# lisa_l.net
KiCad netlist of a schematic drawn in EAGLE
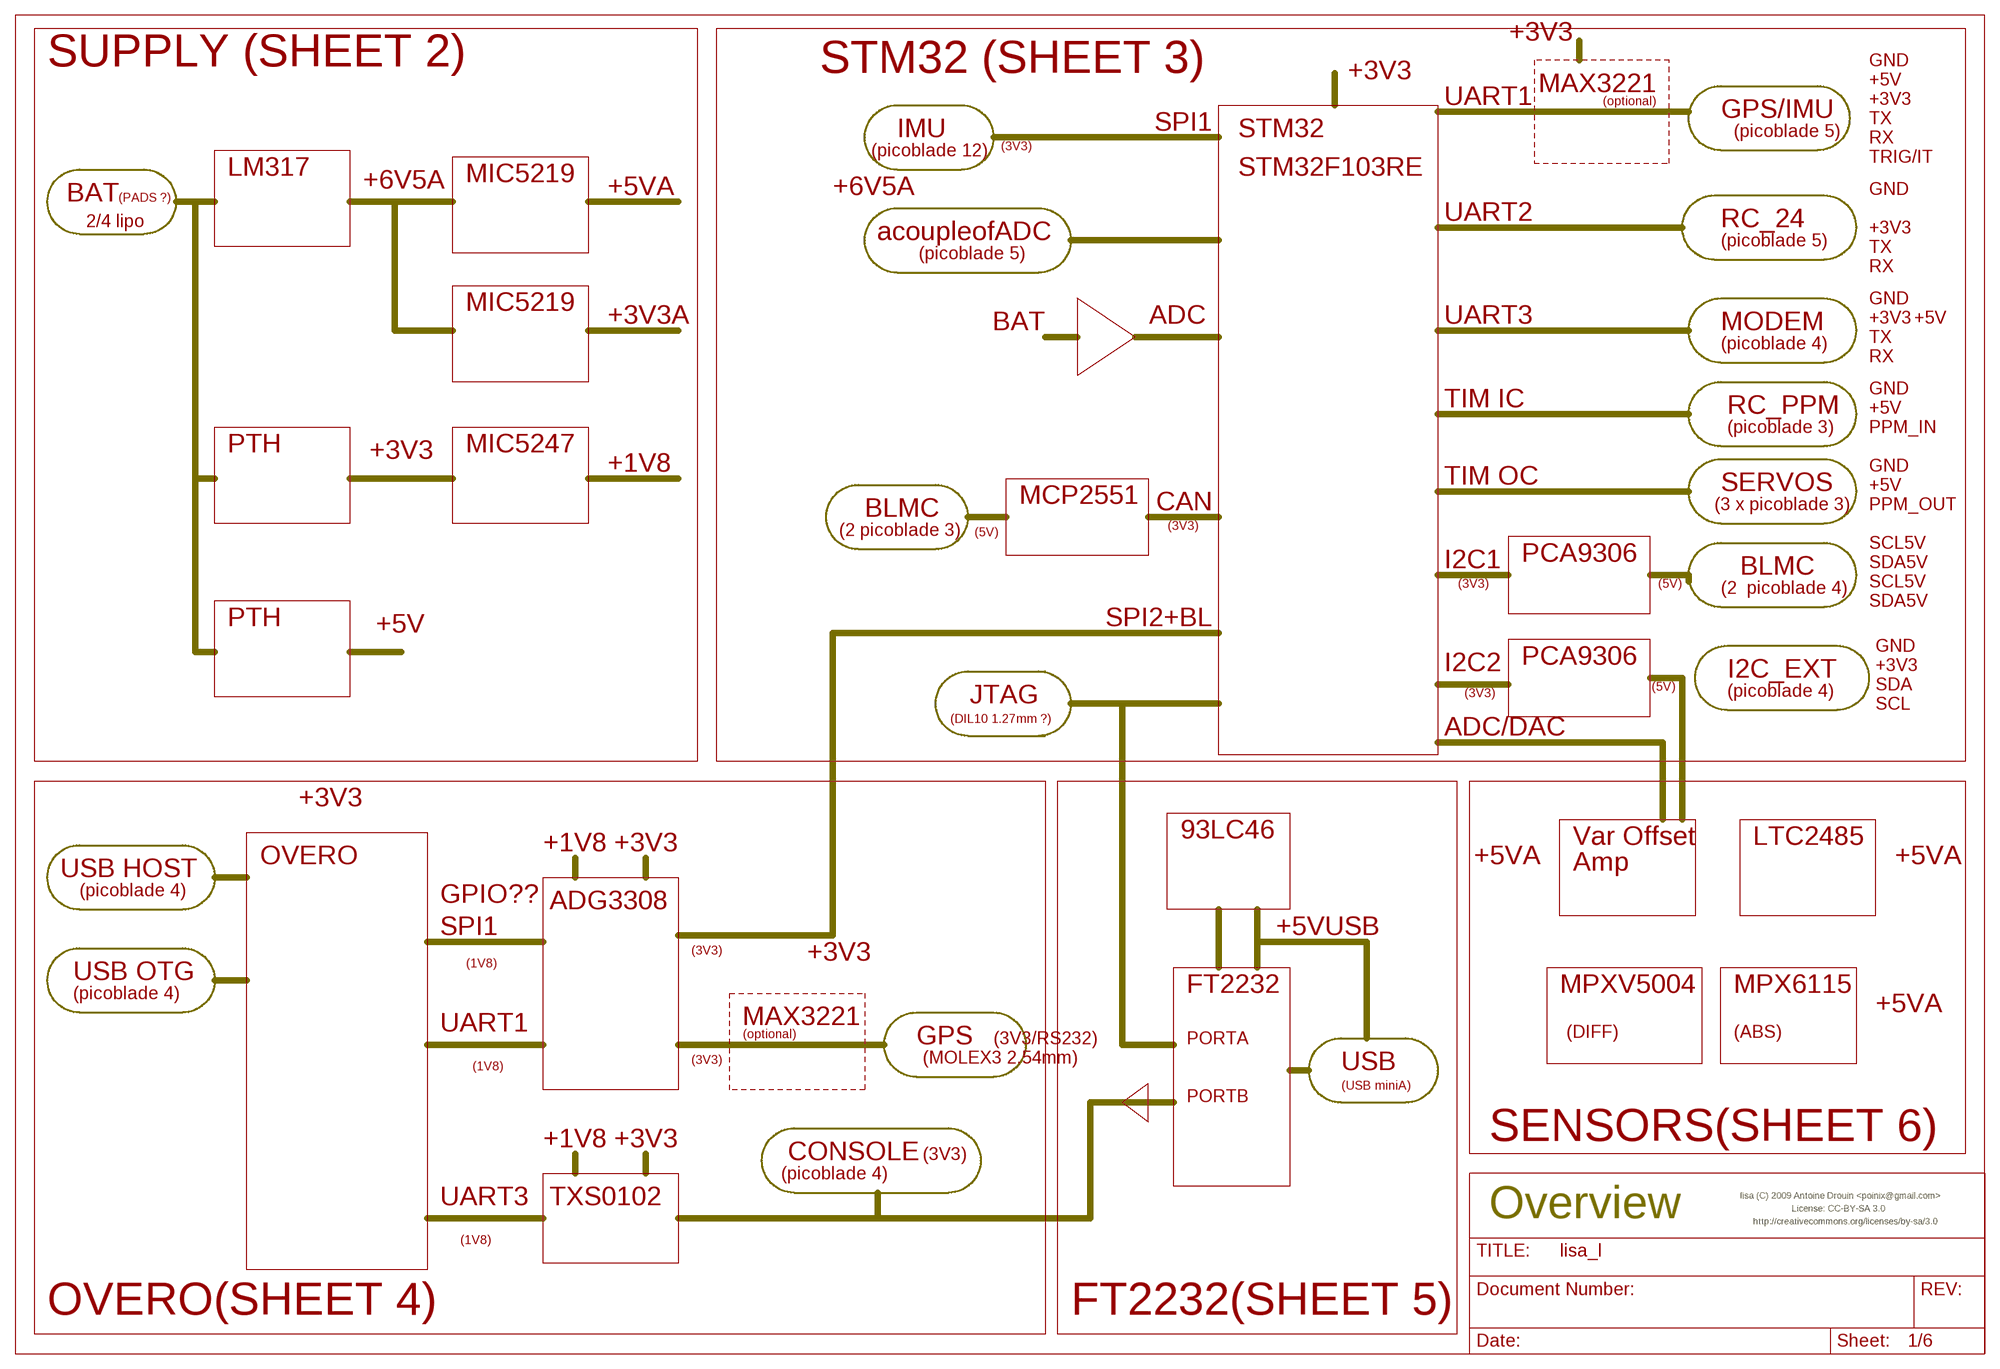
[diagram p0: schematic, sheet 1]
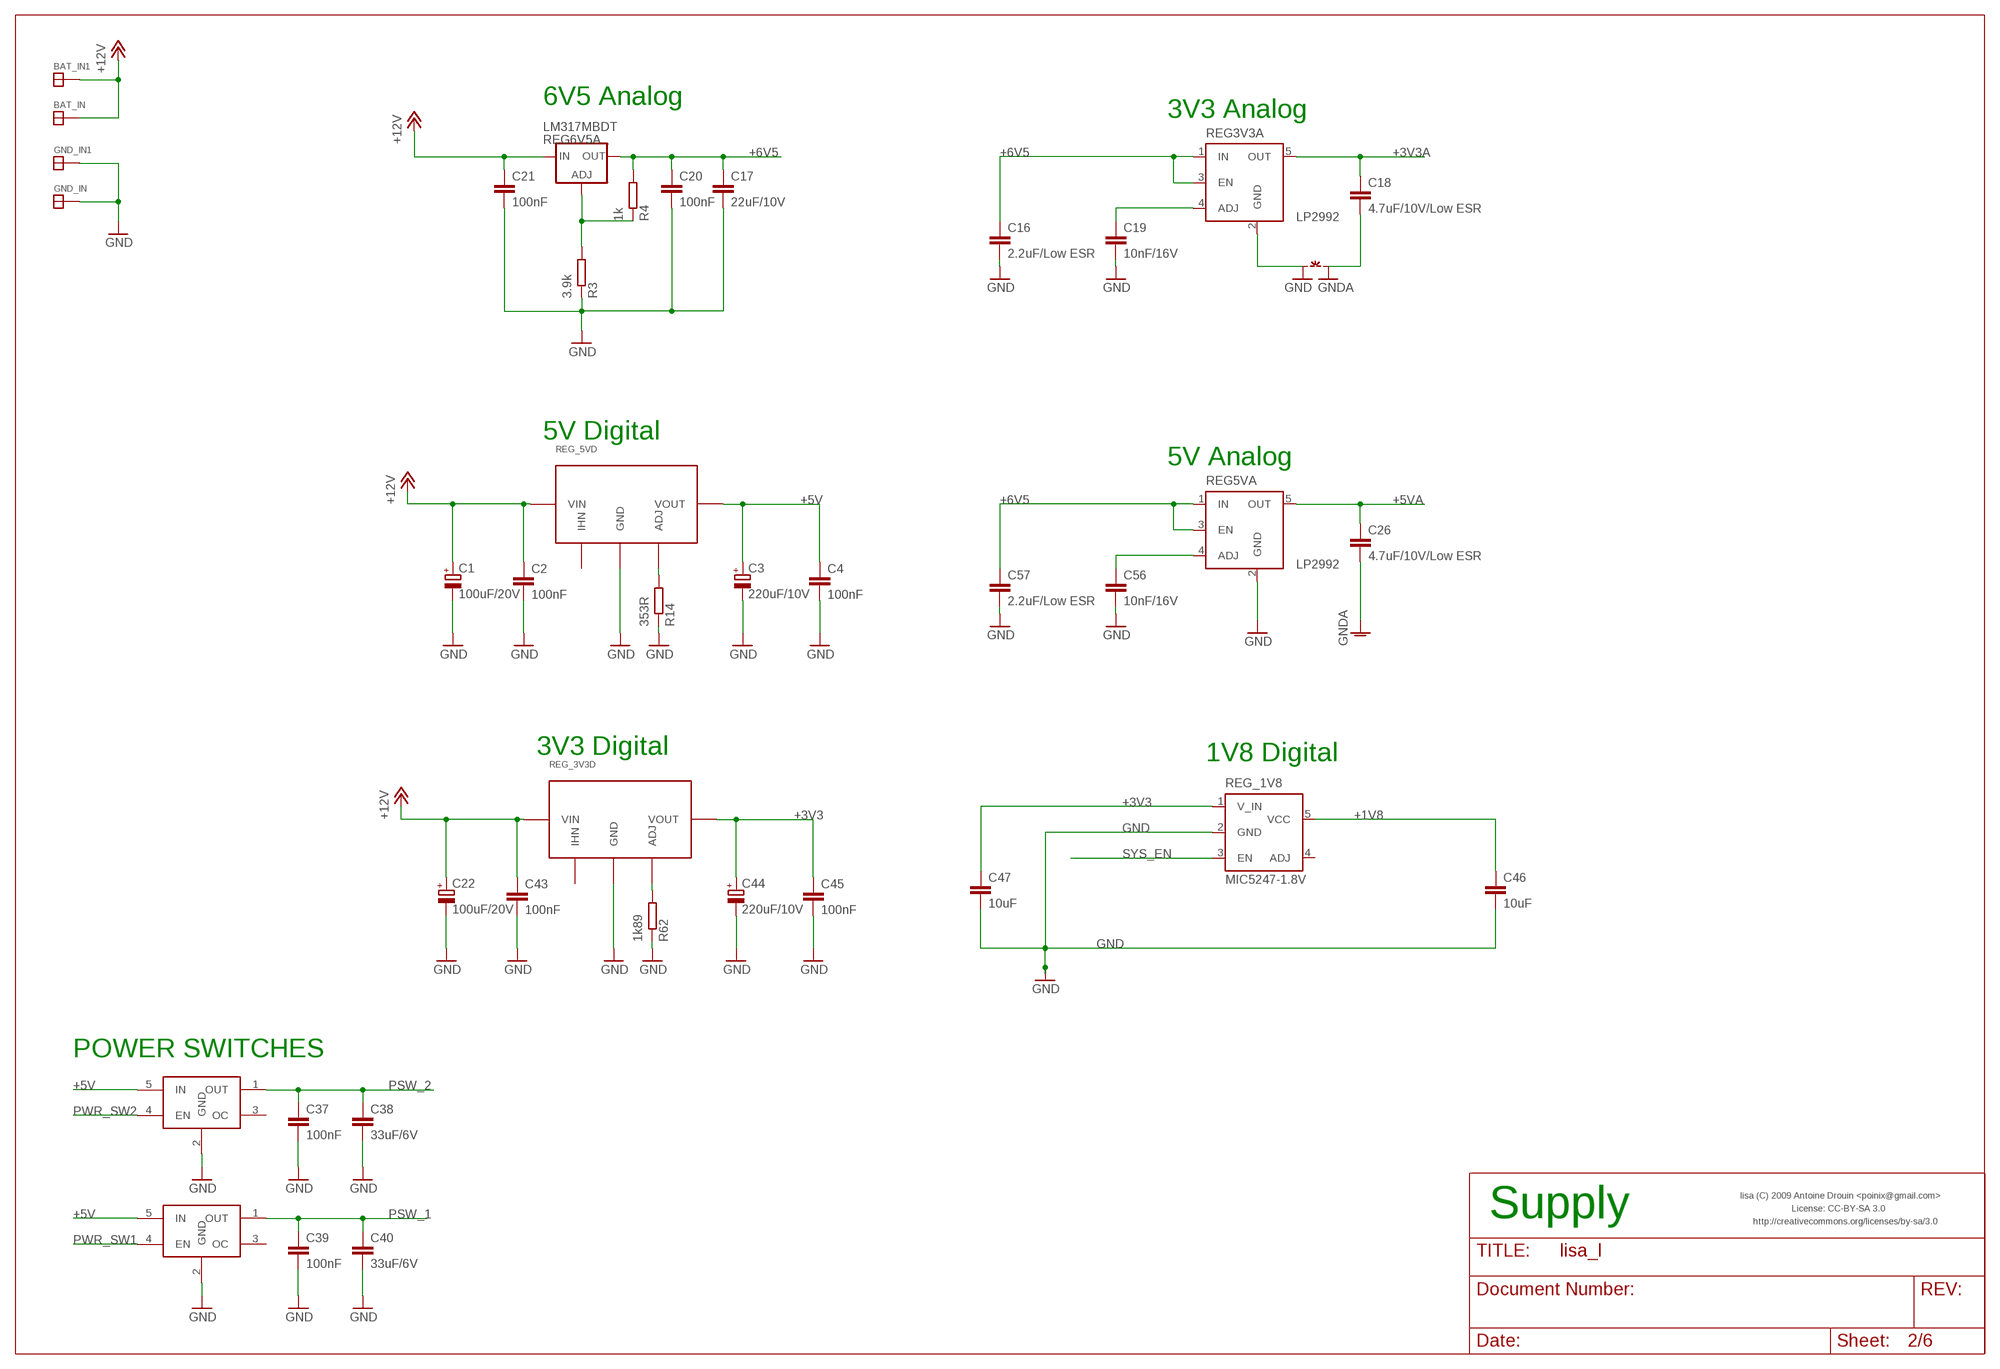
[diagram p1: schematic, sheet 2]
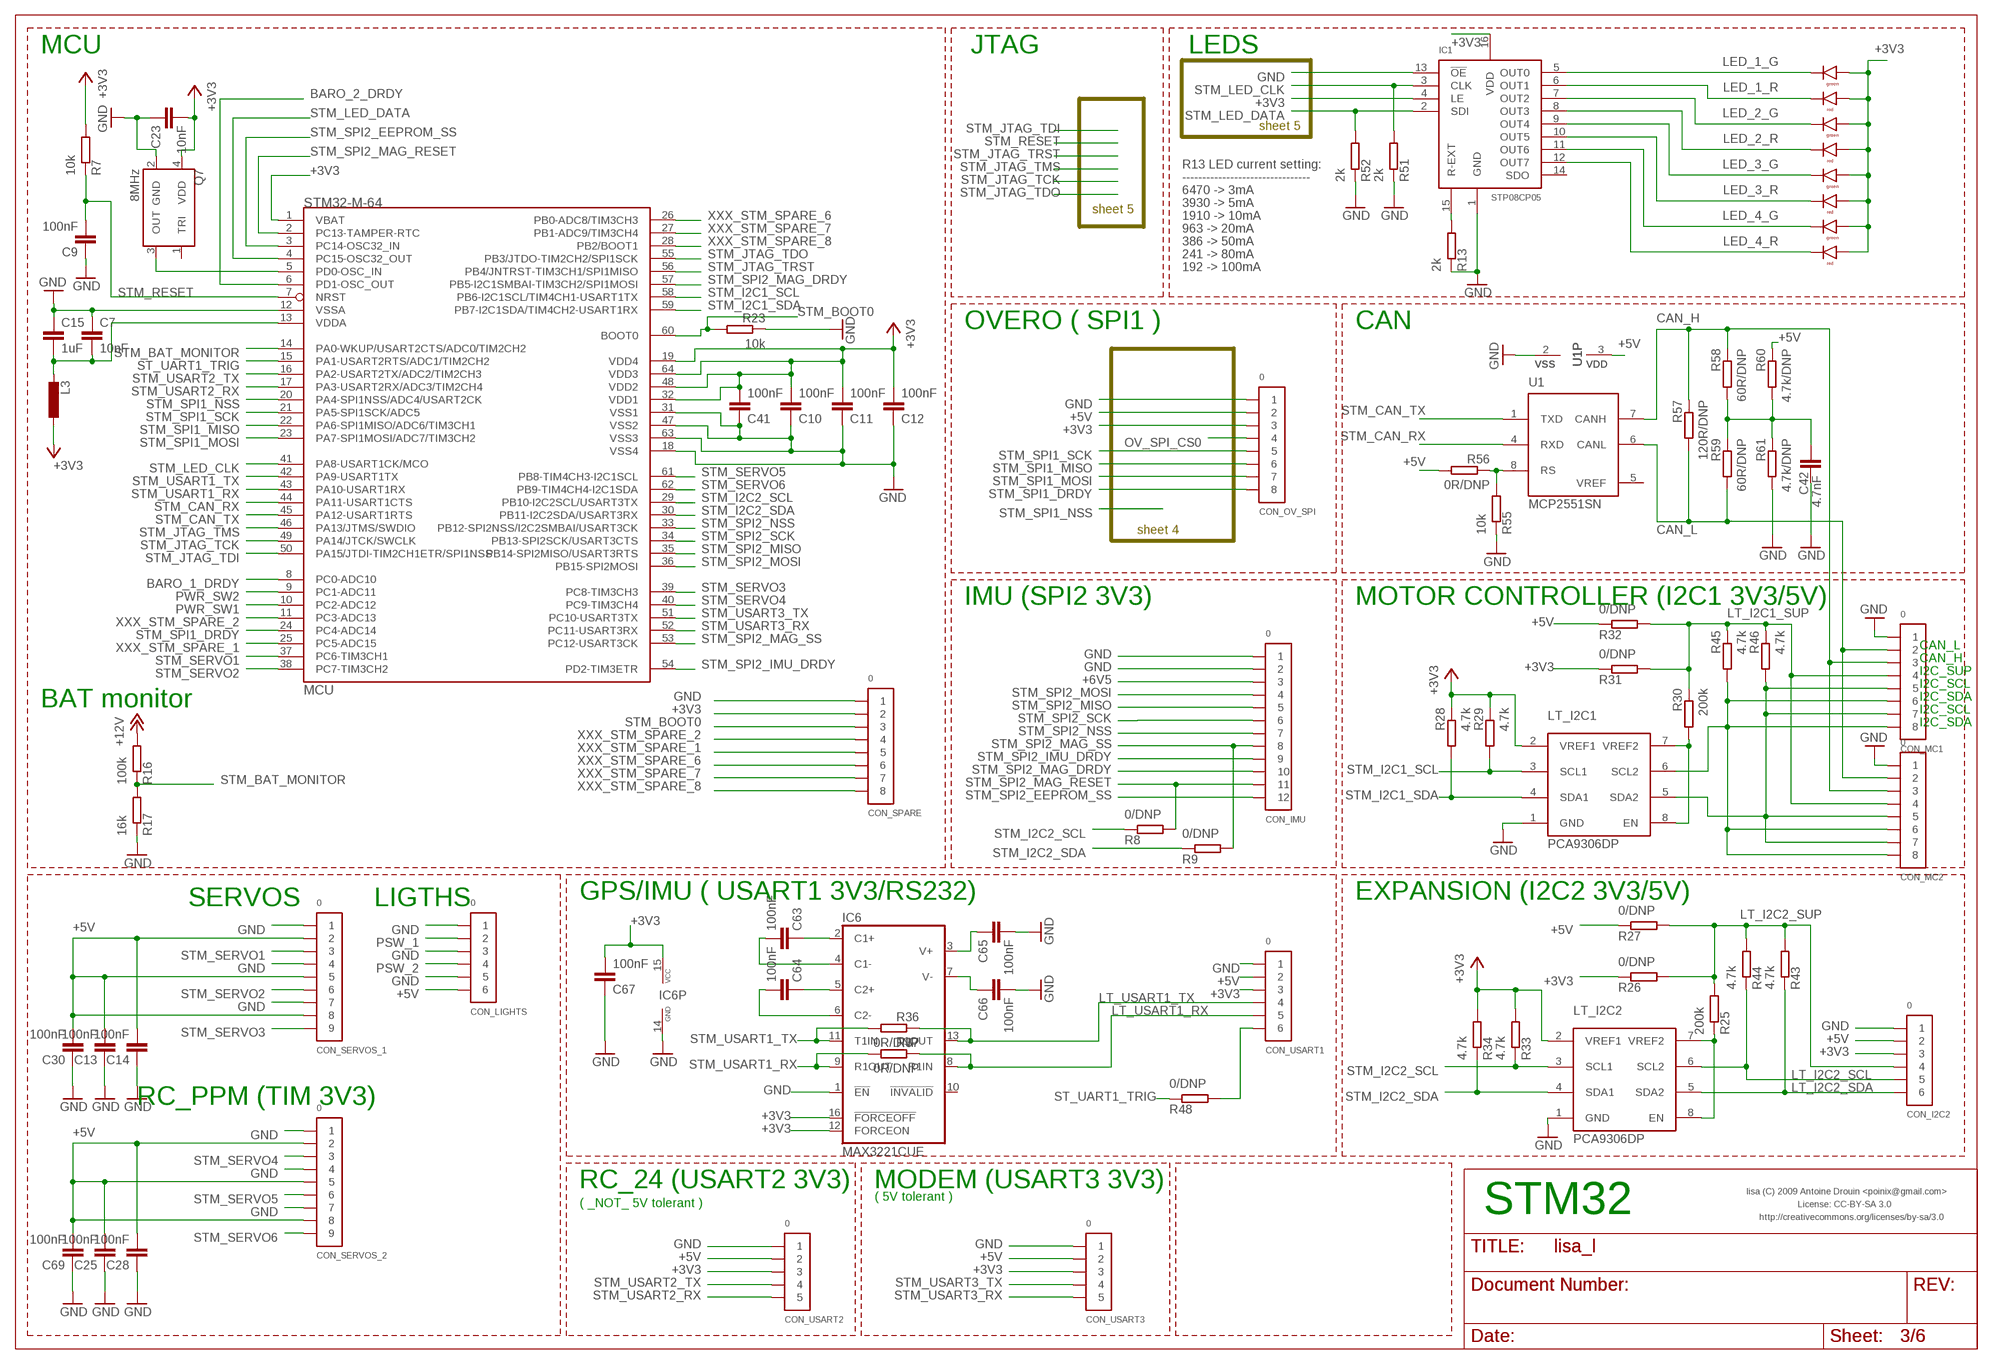
[diagram p2: schematic, sheet 3]
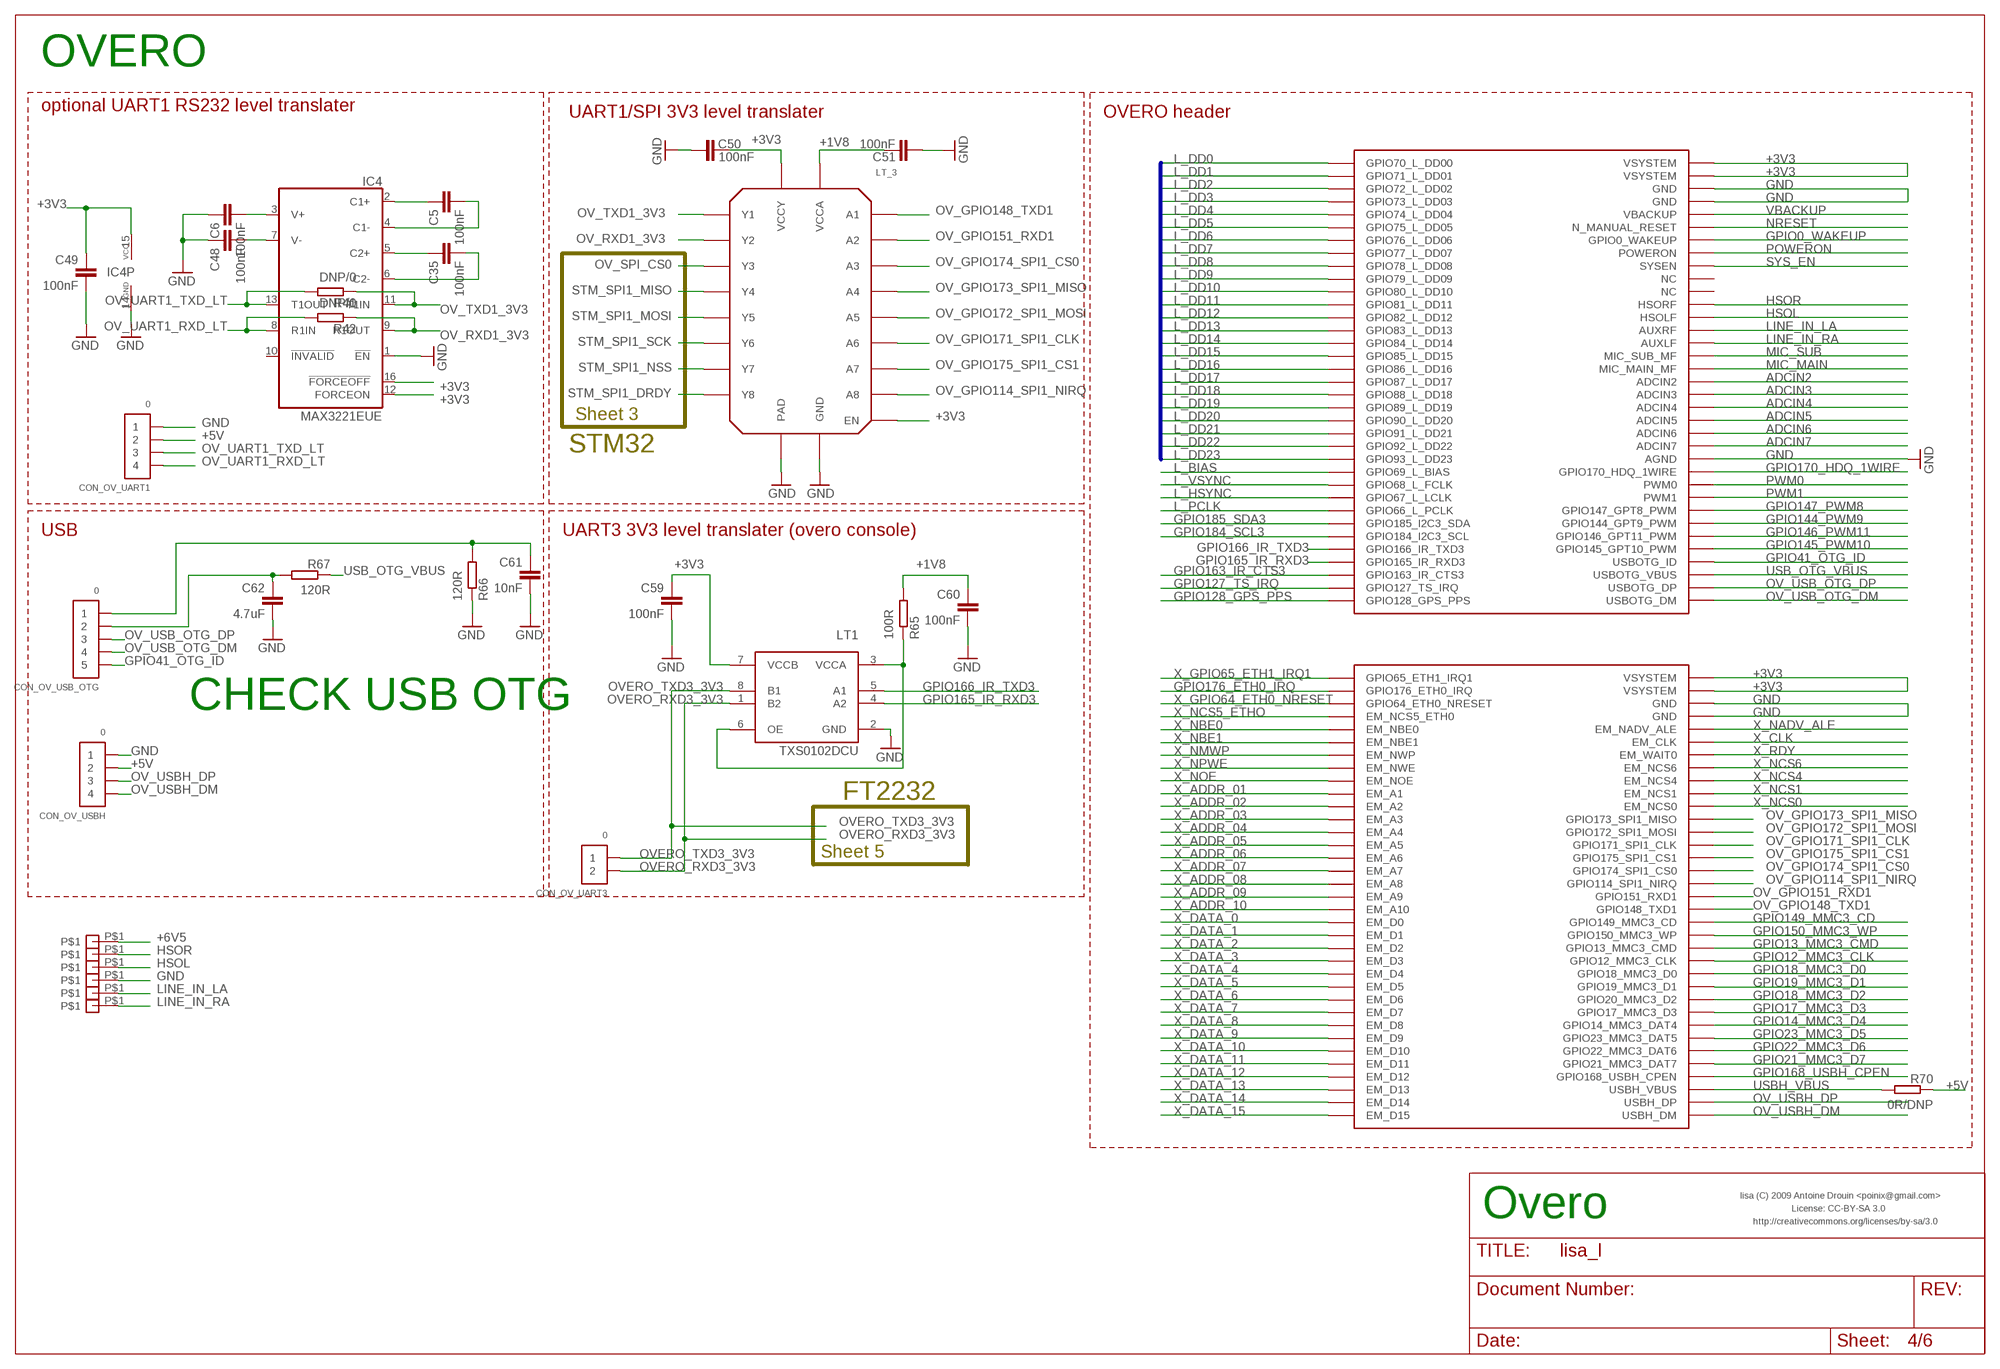
[diagram p3: schematic, sheet 4]
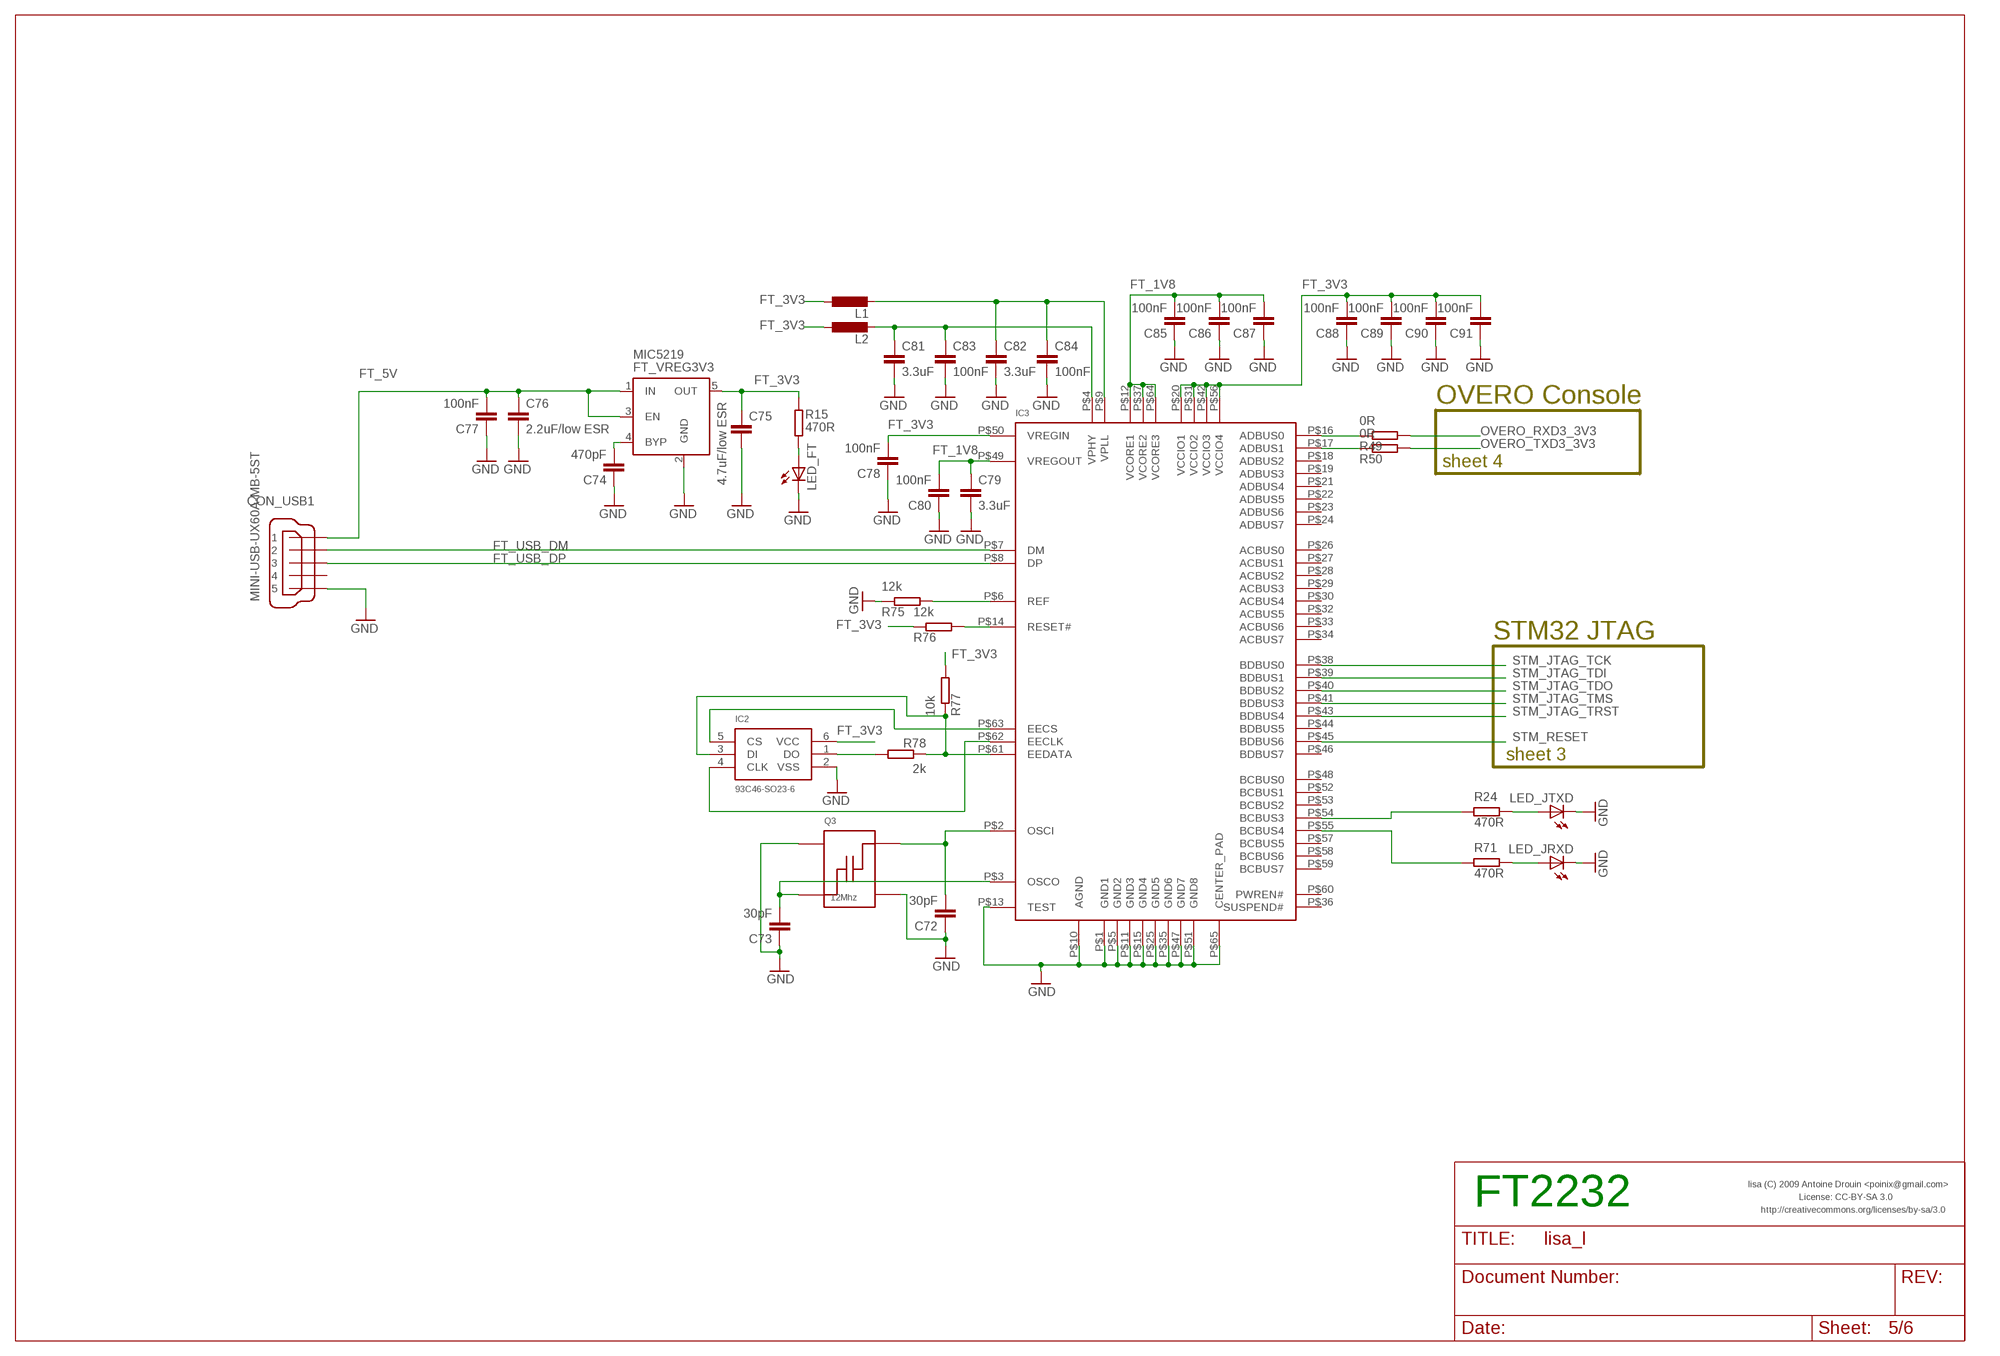
[diagram p4: schematic, sheet 5]
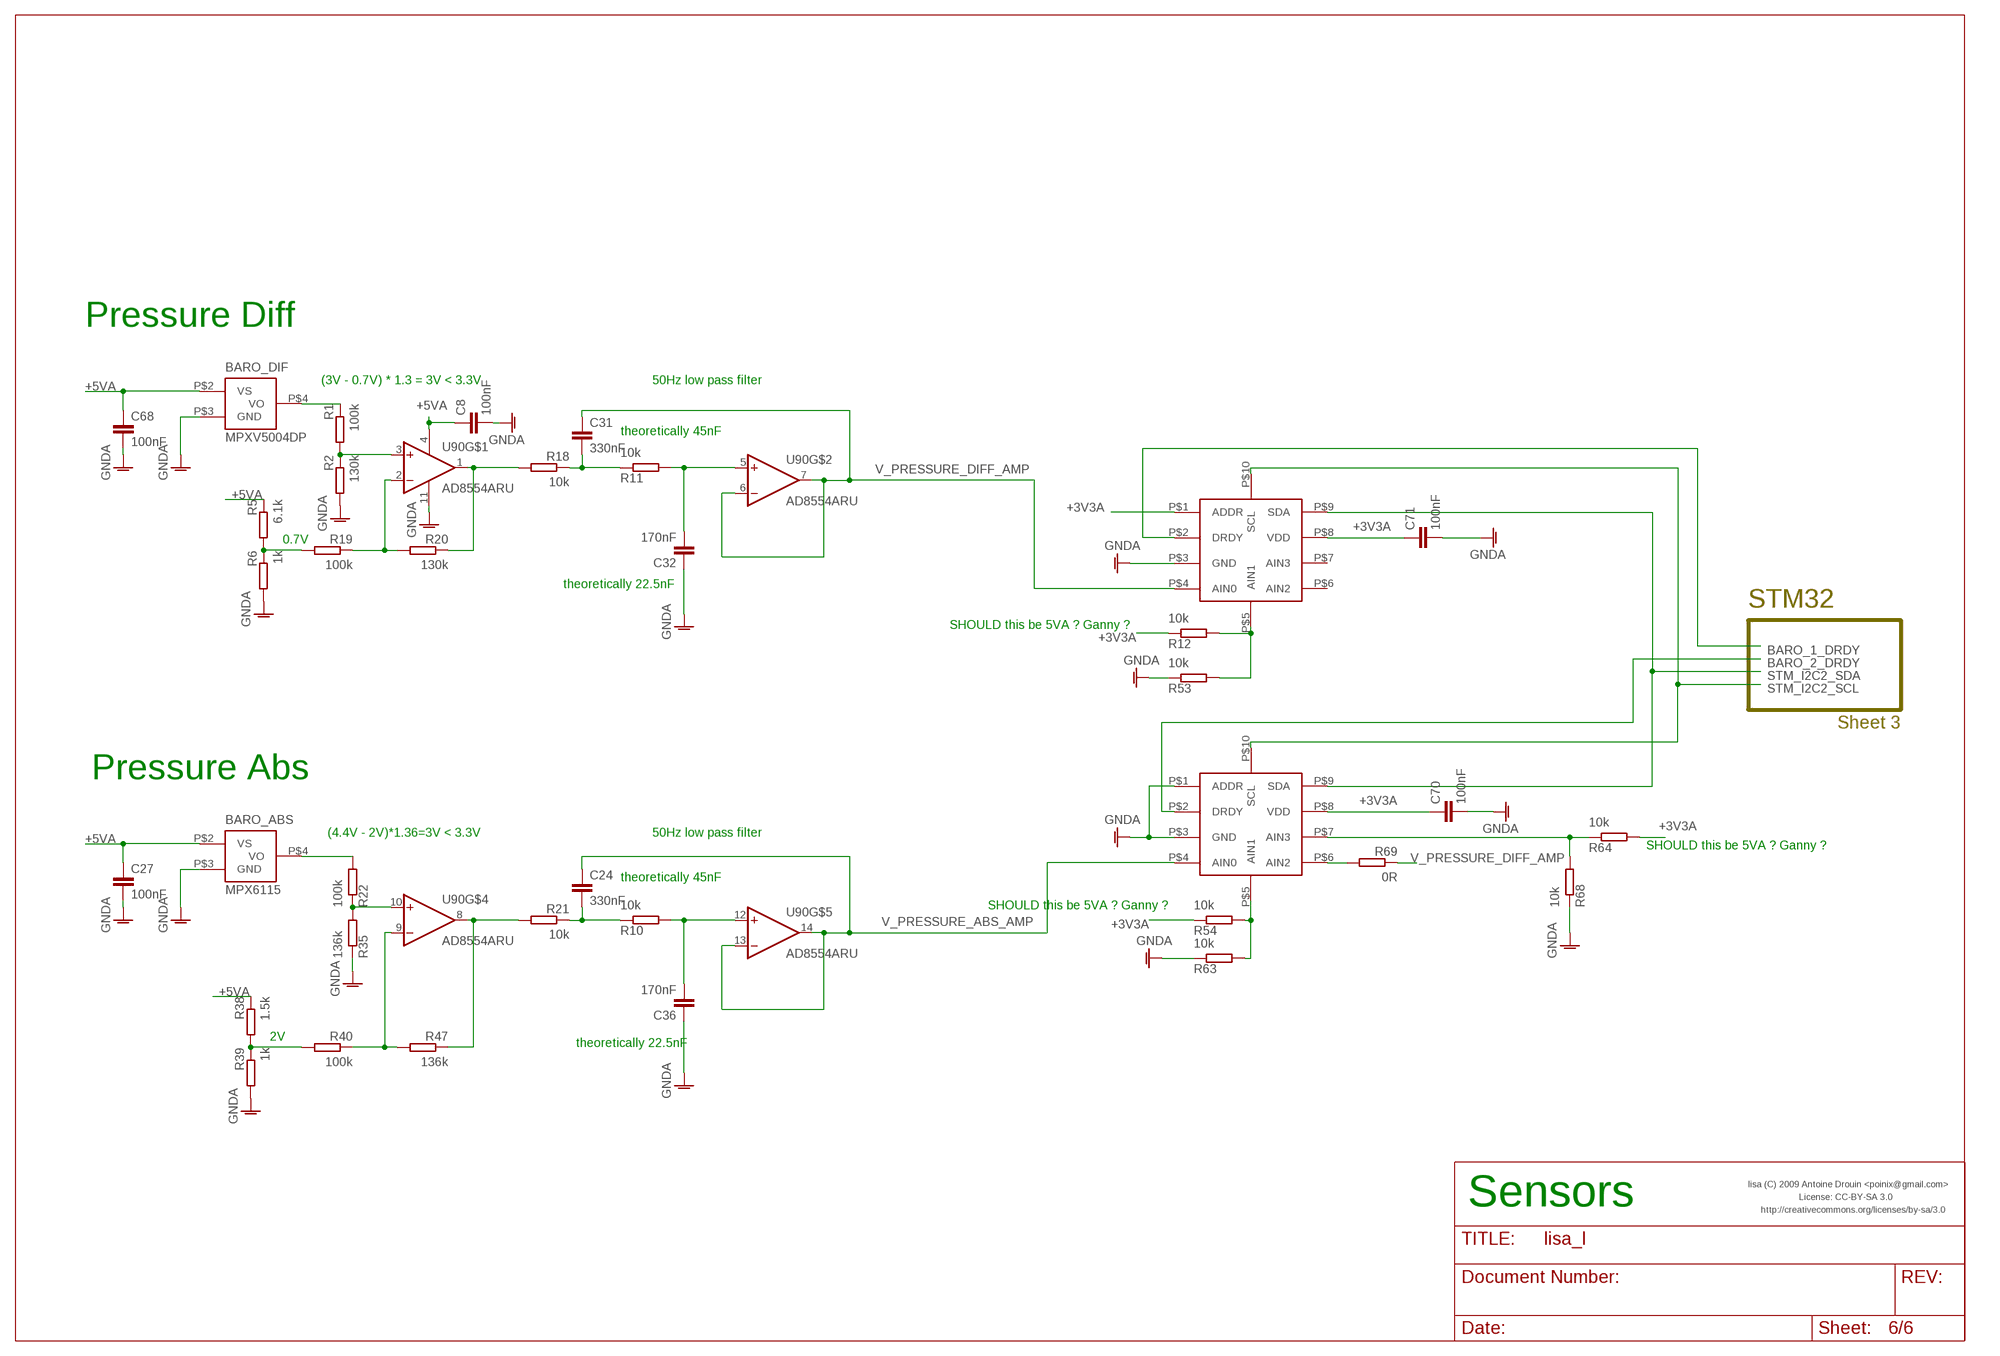
[diagram p5: schematic, sheet 6]

(export (version "E")
  (design (tool "Eeschema 10.0.6"))
  (components
    (comp (ref "C72")
      (value "30pF")
      (footprint "eagle-import:0603-CAP")
      (libsource (lib "eagle-import") (part "res_cap_CAPACITOR-0603"))
    )
    (comp (ref "C73")
      (value "30pF")
      (footprint "eagle-import:0603-CAP")
      (libsource (lib "eagle-import") (part "res_cap_CAPACITOR-0603"))
    )
    (comp (ref "C74")
      (value "470pF")
      (footprint "eagle-import:0603-CAP")
      (libsource (lib "eagle-import") (part "res_cap_CAPACITOR-0603"))
    )
    (comp (ref "C75")
      (value "4.7uF/low ESR")
      (footprint "eagle-import:0603-CAP")
      (libsource (lib "eagle-import") (part "res_cap_CAPACITOR-0603"))
    )
    (comp (ref "C76")
      (value "2.2uF/low ESR")
      (footprint "eagle-import:0603-CAP")
      (libsource (lib "eagle-import") (part "res_cap_CAPACITOR-0603"))
    )
    (comp (ref "C77")
      (value "100nF")
      (footprint "eagle-import:0603-CAP")
      (libsource (lib "eagle-import") (part "res_cap_CAPACITOR-0603"))
    )
    (comp (ref "C78")
      (value "100nF")
      (footprint "eagle-import:0603-CAP")
      (libsource (lib "eagle-import") (part "res_cap_CAPACITOR-0603"))
    )
    (comp (ref "C79")
      (value "3.3uF")
      (footprint "eagle-import:0603-CAP")
      (libsource (lib "eagle-import") (part "res_cap_CAPACITOR-0603"))
    )
    (comp (ref "C80")
      (value "100nF")
      (footprint "eagle-import:0603-CAP")
      (libsource (lib "eagle-import") (part "res_cap_CAPACITOR-0603"))
    )
    (comp (ref "C81")
      (value "3.3uF")
      (footprint "eagle-import:0603-CAP")
      (libsource (lib "eagle-import") (part "res_cap_CAPACITOR-0603"))
    )
    (comp (ref "C82")
      (value "3.3uF")
      (footprint "eagle-import:0603-CAP")
      (libsource (lib "eagle-import") (part "res_cap_CAPACITOR-0603"))
    )
    (comp (ref "C83")
      (value "100nF")
      (footprint "eagle-import:0603-CAP")
      (libsource (lib "eagle-import") (part "res_cap_CAPACITOR-0603"))
    )
    (comp (ref "C84")
      (value "100nF")
      (footprint "eagle-import:0603-CAP")
      (libsource (lib "eagle-import") (part "res_cap_CAPACITOR-0603"))
    )
    (comp (ref "C85")
      (value "100nF")
      (footprint "eagle-import:0603-CAP")
      (libsource (lib "eagle-import") (part "res_cap_CAPACITOR-0603"))
    )
    (comp (ref "C86")
      (value "100nF")
      (footprint "eagle-import:0603-CAP")
      (libsource (lib "eagle-import") (part "res_cap_CAPACITOR-0603"))
    )
    (comp (ref "C87")
      (value "100nF")
      (footprint "eagle-import:0603-CAP")
      (libsource (lib "eagle-import") (part "res_cap_CAPACITOR-0603"))
    )
    (comp (ref "C88")
      (value "100nF")
      (footprint "eagle-import:0603-CAP")
      (libsource (lib "eagle-import") (part "res_cap_CAPACITOR-0603"))
    )
    (comp (ref "C89")
      (value "100nF")
      (footprint "eagle-import:0603-CAP")
      (libsource (lib "eagle-import") (part "res_cap_CAPACITOR-0603"))
    )
    (comp (ref "C90")
      (value "100nF")
      (footprint "eagle-import:0603-CAP")
      (libsource (lib "eagle-import") (part "res_cap_CAPACITOR-0603"))
    )
    (comp (ref "C91")
      (value "100nF")
      (footprint "eagle-import:0603-CAP")
      (libsource (lib "eagle-import") (part "res_cap_CAPACITOR-0603"))
    )
    (comp (ref "CON_USB1")
      (value "MINI-USB-UX60A-MB-5ST")
      (footprint "eagle-import:UX60A-MB-5ST")
      (libsource (lib "eagle-import") (part "MINI-USB-UX60A-MB-5ST"))
    )
    (comp (ref "FT_VREG3V3")
      (value "MIC5219")
      (footprint "eagle-import:SOT23-5")
      (libsource (lib "eagle-import") (part "MIC5219XX"))
    )
    (comp (ref "IC2")
      (value "93C46-SO23-6")
      (footprint "eagle-import:SO23-6")
      (libsource (lib "eagle-import") (part "93C46-SO23-6"))
    )
    (comp (ref "IC3")
      (value "FT2232HQ")
      (footprint "eagle-import:QFN64")
      (libsource (lib "eagle-import") (part "FT2232HQ"))
    )
    (comp (ref "L1")
      (value "INDUCTOR-0603")
      (footprint "eagle-import:0603-IND")
      (libsource (lib "eagle-import") (part "INDUCTOR-0603"))
    )
    (comp (ref "L2")
      (value "INDUCTOR-0603")
      (footprint "eagle-import:0603-IND")
      (libsource (lib "eagle-import") (part "INDUCTOR-0603"))
    )
    (comp (ref "LED_FT")
      (value "LED-0603")
      (footprint "eagle-import:0603-LED")
      (libsource (lib "eagle-import") (part "LED-0603"))
    )
    (comp (ref "LED_JRXD")
      (value "LED-0603")
      (footprint "eagle-import:0603-LED")
      (libsource (lib "eagle-import") (part "LED-0603"))
    )
    (comp (ref "LED_JTXD")
      (value "LED-0603")
      (footprint "eagle-import:0603-LED")
      (libsource (lib "eagle-import") (part "LED-0603"))
    )
    (comp (ref "Q3")
      (value "12Mhz")
      (footprint "eagle-import:ABM8")
      (libsource (lib "eagle-import") (part "ABM8"))
    )
    (comp (ref "R15")
      (value "470R")
      (footprint "eagle-import:0603-RES")
      (libsource (lib "eagle-import") (part "res_cap_RESISTOR-0603"))
    )
    (comp (ref "R24")
      (value "470R")
      (footprint "eagle-import:0603-RES")
      (libsource (lib "eagle-import") (part "res_cap_RESISTOR-0603"))
    )
    (comp (ref "R49")
      (value "0R")
      (footprint "eagle-import:0603-RES")
      (libsource (lib "eagle-import") (part "RESISTOR-0603"))
    )
    (comp (ref "R50")
      (value "0R")
      (footprint "eagle-import:0603-RES")
      (libsource (lib "eagle-import") (part "RESISTOR-0603"))
    )
    (comp (ref "R71")
      (value "470R")
      (footprint "eagle-import:0603-RES")
      (libsource (lib "eagle-import") (part "res_cap_RESISTOR-0603"))
    )
    (comp (ref "R75")
      (value "12k")
      (footprint "eagle-import:0603-RES")
      (libsource (lib "eagle-import") (part "res_cap_RESISTOR-0603"))
    )
    (comp (ref "R76")
      (value "12k")
      (footprint "eagle-import:0603-RES")
      (libsource (lib "eagle-import") (part "res_cap_RESISTOR-0603"))
    )
    (comp (ref "R77")
      (value "10k")
      (footprint "eagle-import:0603-RES")
      (libsource (lib "eagle-import") (part "res_cap_RESISTOR-0603"))
    )
    (comp (ref "R78")
      (value "2k")
      (footprint "eagle-import:0603-RES")
      (libsource (lib "eagle-import") (part "res_cap_RESISTOR-0603"))
    )
    (comp (ref "C5")
      (value "100nF")
      (footprint "eagle-import:0603-CAP")
      (libsource (lib "eagle-import") (part "CAPACITOR-0603"))
    )
    (comp (ref "C6")
      (value "100nF")
      (footprint "eagle-import:0603-CAP")
      (libsource (lib "eagle-import") (part "CAPACITOR-0603"))
    )
    (comp (ref "C35")
      (value "100nF")
      (footprint "eagle-import:0603-CAP")
      (libsource (lib "eagle-import") (part "CAPACITOR-0603"))
    )
    (comp (ref "C48")
      (value "100nF")
      (footprint "eagle-import:0603-CAP")
      (libsource (lib "eagle-import") (part "CAPACITOR-0603"))
    )
    (comp (ref "C49")
      (value "100nF")
      (footprint "eagle-import:0603-CAP")
      (libsource (lib "eagle-import") (part "CAPACITOR-0603"))
    )
    (comp (ref "C50")
      (value "100nF")
      (footprint "eagle-import:0603-CAP")
      (libsource (lib "eagle-import") (part "CAPACITOR-0603"))
    )
    (comp (ref "C51")
      (value "100nF")
      (footprint "eagle-import:0603-CAP")
      (libsource (lib "eagle-import") (part "CAPACITOR-0603"))
    )
    (comp (ref "C59")
      (value "100nF")
      (footprint "eagle-import:0603-CAP")
      (libsource (lib "eagle-import") (part "CAPACITOR-0603"))
    )
    (comp (ref "C60")
      (value "100nF")
      (footprint "eagle-import:0603-CAP")
      (libsource (lib "eagle-import") (part "CAPACITOR-0603"))
    )
    (comp (ref "C61")
      (value "10nF")
      (footprint "eagle-import:0603-CAP")
      (libsource (lib "eagle-import") (part "CAPACITOR-0603"))
    )
    (comp (ref "C62")
      (value "4.7uF")
      (footprint "eagle-import:0603-CAP")
      (libsource (lib "eagle-import") (part "res_cap_CAPACITOR-0603"))
    )
    (comp (ref "CON_OV_UART1")
      (value "0")
      (footprint "eagle-import:PB-53261-04")
      (libsource (lib "eagle-import") (part "CONN_4-1-53261"))
    )
    (comp (ref "CON_OV_UART3")
      (value "0")
      (footprint "eagle-import:PB-53261-02")
      (libsource (lib "eagle-import") (part "CONN_2-1-53261"))
    )
    (comp (ref "CON_OV_USBH")
      (value "0")
      (footprint "eagle-import:PB-53261-04")
      (libsource (lib "eagle-import") (part "CONN_4-1-53261"))
    )
    (comp (ref "CON_OV_USB_OTG")
      (value "0")
      (footprint "eagle-import:PB-53261-05")
      (libsource (lib "eagle-import") (part "CONN_5-1-53261"))
    )
    (comp (ref "IC4")
      (value "MAX3221EUE")
      (footprint "eagle-import:TSSOP16")
      (libsource (lib "eagle-import") (part "MAX3221UEE"))
    )
    (comp (ref "J3&4")
      (value "OVERO")
      (footprint "eagle-import:OVERO")
      (libsource (lib "eagle-import") (part "OVERO"))
    )
    (comp (ref "LT1")
      (value "TXS0102DCU")
      (footprint "eagle-import:US8")
      (libsource (lib "eagle-import") (part "TXS0102DCU"))
    )
    (comp (ref "LT_3")
      (value "AD3308BCPZ")
      (footprint "eagle-import:LFCSP-20")
      (libsource (lib "eagle-import") (part "AD3308BCPZ"))
    )
    (comp (ref "R41")
      (value "DNP/0")
      (footprint "eagle-import:0603-RES")
      (libsource (lib "eagle-import") (part "RESISTOR-0603"))
    )
    (comp (ref "R42")
      (value "DNP/0")
      (footprint "eagle-import:0603-RES")
      (libsource (lib "eagle-import") (part "RESISTOR-0603"))
    )
    (comp (ref "R65")
      (value "100R")
      (footprint "eagle-import:0603-RES")
      (libsource (lib "eagle-import") (part "RESISTOR-0603"))
    )
    (comp (ref "R66")
      (value "120R")
      (footprint "eagle-import:0603-RES")
      (libsource (lib "eagle-import") (part "RESISTOR-0603"))
    )
    (comp (ref "R67")
      (value "120R")
      (footprint "eagle-import:0603-RES")
      (libsource (lib "eagle-import") (part "RESISTOR-0603"))
    )
    (comp (ref "R70")
      (value "0R/DNP")
      (footprint "eagle-import:0603-RES")
      (libsource (lib "eagle-import") (part "RESISTOR-0603"))
    )
    (comp (ref "U$1")
      (value "SOLDER_PAD")
      (footprint "eagle-import:SOLDER_PAD_SMALL")
      (libsource (lib "eagle-import") (part "poinix_SOLDER_PAD"))
    )
    (comp (ref "U$2")
      (value "SOLDER_PAD")
      (footprint "eagle-import:SOLDER_PAD_SMALL")
      (libsource (lib "eagle-import") (part "poinix_SOLDER_PAD"))
    )
    (comp (ref "U$3")
      (value "SOLDER_PAD")
      (footprint "eagle-import:SOLDER_PAD_SMALL")
      (libsource (lib "eagle-import") (part "poinix_SOLDER_PAD"))
    )
    (comp (ref "U$4")
      (value "SOLDER_PAD")
      (footprint "eagle-import:SOLDER_PAD_SMALL")
      (libsource (lib "eagle-import") (part "poinix_SOLDER_PAD"))
    )
    (comp (ref "U$5")
      (value "SOLDER_PAD")
      (footprint "eagle-import:SOLDER_PAD_SMALL")
      (libsource (lib "eagle-import") (part "poinix_SOLDER_PAD"))
    )
    (comp (ref "U$6")
      (value "SOLDER_PAD")
      (footprint "eagle-import:SOLDER_PAD_SMALL")
      (libsource (lib "eagle-import") (part "poinix_SOLDER_PAD"))
    )
    (comp (ref "ADC1")
      (value "ADS1114")
      (footprint "eagle-import:R-PQFP-N10")
      (libsource (lib "eagle-import") (part "ADS1114"))
    )
    (comp (ref "ADC2")
      (value "ADS1114")
      (footprint "eagle-import:R-PQFP-N10")
      (libsource (lib "eagle-import") (part "ADS1114"))
    )
    (comp (ref "BARO_ABS")
      (value "MPX6115")
      (footprint "eagle-import:CASE_1317")
      (libsource (lib "eagle-import") (part "MPX6115"))
    )
    (comp (ref "BARO_DIF")
      (value "MPXV5004DP")
      (footprint "eagle-import:CASE1351")
      (libsource (lib "eagle-import") (part "MPXV5004DP"))
    )
    (comp (ref "C8")
      (value "100nF")
      (footprint "eagle-import:0603-CAP")
      (libsource (lib "eagle-import") (part "CAPACITOR-0603"))
    )
    (comp (ref "C24")
      (value "330nF")
      (footprint "eagle-import:0603-CAP")
      (libsource (lib "eagle-import") (part "CAPACITOR-0603"))
    )
    (comp (ref "C27")
      (value "100nF")
      (footprint "eagle-import:0603-CAP")
      (libsource (lib "eagle-import") (part "CAPACITOR-0603"))
    )
    (comp (ref "C31")
      (value "330nF")
      (footprint "eagle-import:0603-CAP")
      (libsource (lib "eagle-import") (part "CAPACITOR-0603"))
    )
    (comp (ref "C32")
      (value "170nF")
      (footprint "eagle-import:0603-CAP")
      (libsource (lib "eagle-import") (part "CAPACITOR-0603"))
    )
    (comp (ref "C36")
      (value "170nF")
      (footprint "eagle-import:0603-CAP")
      (libsource (lib "eagle-import") (part "CAPACITOR-0603"))
    )
    (comp (ref "C68")
      (value "100nF")
      (footprint "eagle-import:0603-CAP")
      (libsource (lib "eagle-import") (part "CAPACITOR-0603"))
    )
    (comp (ref "C70")
      (value "100nF")
      (footprint "eagle-import:0603-CAP")
      (libsource (lib "eagle-import") (part "CAPACITOR-0603"))
    )
    (comp (ref "C71")
      (value "100nF")
      (footprint "eagle-import:0603-CAP")
      (libsource (lib "eagle-import") (part "CAPACITOR-0603"))
    )
    (comp (ref "R1")
      (value "100k")
      (footprint "eagle-import:0603-RES")
      (libsource (lib "eagle-import") (part "RESISTOR-0603"))
    )
    (comp (ref "R2")
      (value "130k")
      (footprint "eagle-import:0603-RES")
      (libsource (lib "eagle-import") (part "RESISTOR-0603"))
    )
    (comp (ref "R5")
      (value "6.1k")
      (footprint "eagle-import:0603-RES")
      (libsource (lib "eagle-import") (part "RESISTOR-0603"))
    )
    (comp (ref "R6")
      (value "1k")
      (footprint "eagle-import:0603-RES")
      (libsource (lib "eagle-import") (part "RESISTOR-0603"))
    )
    (comp (ref "R10")
      (value "10k")
      (footprint "eagle-import:0603-RES")
      (libsource (lib "eagle-import") (part "RESISTOR-0603"))
    )
    (comp (ref "R11")
      (value "10k")
      (footprint "eagle-import:0603-RES")
      (libsource (lib "eagle-import") (part "RESISTOR-0603"))
    )
    (comp (ref "R12")
      (value "10k")
      (footprint "eagle-import:0603-RES")
      (libsource (lib "eagle-import") (part "RESISTOR-0603"))
    )
    (comp (ref "R18")
      (value "10k")
      (footprint "eagle-import:0603-RES")
      (libsource (lib "eagle-import") (part "RESISTOR-0603"))
    )
    (comp (ref "R19")
      (value "100k")
      (footprint "eagle-import:0603-RES")
      (libsource (lib "eagle-import") (part "RESISTOR-0603"))
    )
    (comp (ref "R20")
      (value "130k")
      (footprint "eagle-import:0603-RES")
      (libsource (lib "eagle-import") (part "RESISTOR-0603"))
    )
    (comp (ref "R21")
      (value "10k")
      (footprint "eagle-import:0603-RES")
      (libsource (lib "eagle-import") (part "RESISTOR-0603"))
    )
    (comp (ref "R22")
      (value "100k")
      (footprint "eagle-import:0603-RES")
      (libsource (lib "eagle-import") (part "res_cap_RESISTOR-0603"))
    )
    (comp (ref "R35")
      (value "136k")
      (footprint "eagle-import:0603-RES")
      (libsource (lib "eagle-import") (part "res_cap_RESISTOR-0603"))
    )
    (comp (ref "R38")
      (value "1.5k")
      (footprint "eagle-import:0603-RES")
      (libsource (lib "eagle-import") (part "RESISTOR-0603"))
    )
    (comp (ref "R39")
      (value "1k")
      (footprint "eagle-import:0603-RES")
      (libsource (lib "eagle-import") (part "RESISTOR-0603"))
    )
    (comp (ref "R40")
      (value "100k")
      (footprint "eagle-import:0603-RES")
      (libsource (lib "eagle-import") (part "RESISTOR-0603"))
    )
    (comp (ref "R47")
      (value "136k")
      (footprint "eagle-import:0603-RES")
      (libsource (lib "eagle-import") (part "RESISTOR-0603"))
    )
    (comp (ref "R53")
      (value "10k")
      (footprint "eagle-import:0603-RES")
      (libsource (lib "eagle-import") (part "RESISTOR-0603"))
    )
    (comp (ref "R54")
      (value "10k")
      (footprint "eagle-import:0603-RES")
      (libsource (lib "eagle-import") (part "RESISTOR-0603"))
    )
    (comp (ref "R63")
      (value "10k")
      (footprint "eagle-import:0603-RES")
      (libsource (lib "eagle-import") (part "RESISTOR-0603"))
    )
    (comp (ref "R64")
      (value "10k")
      (footprint "eagle-import:0603-RES")
      (libsource (lib "eagle-import") (part "RESISTOR-0603"))
    )
    (comp (ref "R68")
      (value "10k")
      (footprint "eagle-import:0603-RES")
      (libsource (lib "eagle-import") (part "RESISTOR-0603"))
    )
    (comp (ref "R69")
      (value "0R")
      (footprint "eagle-import:0603-RES")
      (libsource (lib "eagle-import") (part "RESISTOR-0603"))
    )
    (comp (ref "U90")
      (value "AD8554ARU")
      (footprint "eagle-import:TSSOP14")
      (libsource (lib "eagle-import") (part "AD8554ARU"))
    )
    (comp (ref "BAT_IN")
      (value "SOLDER_PAD150_75")
      (footprint "eagle-import:SOLD_PAD_150_75")
      (libsource (lib "eagle-import") (part "SOLDER_PAD150_75"))
    )
    (comp (ref "BAT_IN1")
      (value "SOLDER_PAD150_75")
      (footprint "eagle-import:SOLD_PAD_150_75")
      (libsource (lib "eagle-import") (part "SOLDER_PAD150_75"))
    )
    (comp (ref "C1")
      (value "100uF/20V")
      (footprint "eagle-import:7343_D")
      (libsource (lib "eagle-import") (part "CAPACITOR-POLD"))
    )
    (comp (ref "C2")
      (value "100nF")
      (footprint "eagle-import:0603-CAP")
      (libsource (lib "eagle-import") (part "CAPACITOR-0603"))
    )
    (comp (ref "C3")
      (value "220uF/10V")
      (footprint "eagle-import:7343_D")
      (libsource (lib "eagle-import") (part "CAPACITOR-POLD"))
    )
    (comp (ref "C4")
      (value "100nF")
      (footprint "eagle-import:0603-CAP")
      (libsource (lib "eagle-import") (part "CAPACITOR-0603"))
    )
    (comp (ref "C16")
      (value "2.2uF/Low ESR")
      (footprint "eagle-import:0603-CAP")
      (libsource (lib "eagle-import") (part "res_cap_CAPACITOR-0603"))
    )
    (comp (ref "C17")
      (value "22uF/10V")
      (footprint "eagle-import:1206-CAP")
      (libsource (lib "eagle-import") (part "res_cap_CAPACITOR-1206"))
    )
    (comp (ref "C18")
      (value "4.7uF/10V/Low ESR")
      (footprint "eagle-import:0603-CAP")
      (libsource (lib "eagle-import") (part "res_cap_CAPACITOR-0603"))
    )
    (comp (ref "C19")
      (value "10nF/16V")
      (footprint "eagle-import:0603-CAP")
      (libsource (lib "eagle-import") (part "CAPACITOR-0603"))
    )
    (comp (ref "C20")
      (value "100nF")
      (footprint "eagle-import:0603-CAP")
      (libsource (lib "eagle-import") (part "CAPACITOR-0603"))
    )
    (comp (ref "C21")
      (value "100nF")
      (footprint "eagle-import:0603-CAP")
      (libsource (lib "eagle-import") (part "CAPACITOR-0603"))
    )
    (comp (ref "C22")
      (value "100uF/20V")
      (footprint "eagle-import:7343_D")
      (libsource (lib "eagle-import") (part "CAPACITOR-POLD"))
    )
    (comp (ref "C26")
      (value "4.7uF/10V/Low ESR")
      (footprint "eagle-import:0603-CAP")
      (libsource (lib "eagle-import") (part "res_cap_CAPACITOR-0603"))
    )
    (comp (ref "C37")
      (value "100nF")
      (footprint "eagle-import:0603-CAP")
      (libsource (lib "eagle-import") (part "res_cap_CAPACITOR-0603"))
    )
    (comp (ref "C38")
      (value "33uF/6V")
      (footprint "eagle-import:1206-CAP")
      (libsource (lib "eagle-import") (part "res_cap_CAPACITOR-1206"))
    )
    (comp (ref "C39")
      (value "100nF")
      (footprint "eagle-import:0603-CAP")
      (libsource (lib "eagle-import") (part "res_cap_CAPACITOR-0603"))
    )
    (comp (ref "C40")
      (value "33uF/6V")
      (footprint "eagle-import:1206-CAP")
      (libsource (lib "eagle-import") (part "res_cap_CAPACITOR-1206"))
    )
    (comp (ref "C43")
      (value "100nF")
      (footprint "eagle-import:0603-CAP")
      (libsource (lib "eagle-import") (part "CAPACITOR-0603"))
    )
    (comp (ref "C44")
      (value "220uF/10V")
      (footprint "eagle-import:7343_D")
      (libsource (lib "eagle-import") (part "CAPACITOR-POLD"))
    )
    (comp (ref "C45")
      (value "100nF")
      (footprint "eagle-import:0603-CAP")
      (libsource (lib "eagle-import") (part "CAPACITOR-0603"))
    )
    (comp (ref "C46")
      (value "10uF")
      (footprint "eagle-import:0603-CAP")
      (libsource (lib "eagle-import") (part "res_cap_CAPACITOR-0603"))
    )
    (comp (ref "C47")
      (value "10uF")
      (footprint "eagle-import:0603-CAP")
      (libsource (lib "eagle-import") (part "res_cap_CAPACITOR-0603"))
    )
    (comp (ref "C56")
      (value "10nF/16V")
      (footprint "eagle-import:0603-CAP")
      (libsource (lib "eagle-import") (part "CAPACITOR-0603"))
    )
    (comp (ref "C57")
      (value "2.2uF/Low ESR")
      (footprint "eagle-import:0603-CAP")
      (libsource (lib "eagle-import") (part "res_cap_CAPACITOR-0603"))
    )
    (comp (ref "GND_IN")
      (value "SOLDER_PAD150_75")
      (footprint "eagle-import:SOLD_PAD_150_75")
      (libsource (lib "eagle-import") (part "SOLDER_PAD150_75"))
    )
    (comp (ref "GND_IN1")
      (value "SOLDER_PAD150_75")
      (footprint "eagle-import:SOLD_PAD_150_75")
      (libsource (lib "eagle-import") (part "SOLDER_PAD150_75"))
    )
    (comp (ref "PWS1")
      (value "TPS2051B")
      (footprint "eagle-import:SOT23-5L")
      (libsource (lib "eagle-import") (part "TPS2051B"))
    )
    (comp (ref "PWS2")
      (value "TPS2051B")
      (footprint "eagle-import:SOT23-5L")
      (libsource (lib "eagle-import") (part "TPS2051B"))
    )
    (comp (ref "R3")
      (value "3.9k")
      (footprint "eagle-import:0603-RES")
      (libsource (lib "eagle-import") (part "res_cap_RESISTOR-0603"))
    )
    (comp (ref "R4")
      (value "1k")
      (footprint "eagle-import:0603-RES")
      (libsource (lib "eagle-import") (part "res_cap_RESISTOR-0603"))
    )
    (comp (ref "R14")
      (value "353R")
      (footprint "eagle-import:0603-RES")
      (libsource (lib "eagle-import") (part "res_cap_RESISTOR-0603"))
    )
    (comp (ref "R62")
      (value "1k89")
      (footprint "eagle-import:0603-RES")
      (libsource (lib "eagle-import") (part "RESISTOR-0603"))
    )
    (comp (ref "REG3V3A")
      (value "LP2992")
      (footprint "eagle-import:SOT23-5")
      (libsource (lib "eagle-import") (part "v-reg-micrel_MIC5219BM5"))
    )
    (comp (ref "REG5VA")
      (value "LP2992")
      (footprint "eagle-import:SOT23-5")
      (libsource (lib "eagle-import") (part "v-reg-micrel_MIC5219BM5"))
    )
    (comp (ref "REG6V5A")
      (value "LM317MBDT")
      (footprint "eagle-import:DPACK")
      (libsource (lib "eagle-import") (part "LM317?MBDT"))
    )
    (comp (ref "REG_1V8")
      (value "MIC5247-1.8V")
      (footprint "eagle-import:SOT-23-5")
      (libsource (lib "eagle-import") (part "MIC5219YM5"))
    )
    (comp (ref "REG_3V3D")
      (value "PTHTH")
      (footprint "eagle-import:PTH_TH")
      (libsource (lib "eagle-import") (part "PTHTH"))
    )
    (comp (ref "REG_5VD")
      (value "PTHTH")
      (footprint "eagle-import:PTH_TH")
      (libsource (lib "eagle-import") (part "PTHTH"))
    )
    (comp (ref "~NUDEV~1")
      (value "GND-GNDA")
      (footprint "eagle-import:GND-GNDA")
      (libsource (lib "eagle-import") (part "GND-GNDA"))
    )
    (comp (ref "C7")
      (value "10nF")
      (footprint "eagle-import:0603-CAP")
      (libsource (lib "eagle-import") (part "CAPACITOR-0603"))
    )
    (comp (ref "C9")
      (value "100nF")
      (footprint "eagle-import:0603-CAP")
      (libsource (lib "eagle-import") (part "res_cap_CAPACITOR-0603"))
    )
    (comp (ref "C10")
      (value "100nF")
      (footprint "eagle-import:0603-CAP")
      (libsource (lib "eagle-import") (part "CAPACITOR-0603"))
    )
    (comp (ref "C11")
      (value "100nF")
      (footprint "eagle-import:0603-CAP")
      (libsource (lib "eagle-import") (part "CAPACITOR-0603"))
    )
    (comp (ref "C12")
      (value "100nF")
      (footprint "eagle-import:0603-CAP")
      (libsource (lib "eagle-import") (part "CAPACITOR-0603"))
    )
    (comp (ref "C13")
      (value "100nF")
      (footprint "eagle-import:0603-CAP")
      (libsource (lib "eagle-import") (part "CAPACITOR-0603"))
    )
    (comp (ref "C14")
      (value "100nF")
      (footprint "eagle-import:0603-CAP")
      (libsource (lib "eagle-import") (part "CAPACITOR-0603"))
    )
    (comp (ref "C15")
      (value "1uF")
      (footprint "eagle-import:0603-CAP")
      (libsource (lib "eagle-import") (part "CAPACITOR-0603"))
    )
    (comp (ref "C23")
      (value "10nF")
      (footprint "eagle-import:0603-CAP")
      (libsource (lib "eagle-import") (part "CAPACITOR-0603"))
    )
    (comp (ref "C25")
      (value "100nF")
      (footprint "eagle-import:0603-CAP")
      (libsource (lib "eagle-import") (part "CAPACITOR-0603"))
    )
    (comp (ref "C28")
      (value "100nF")
      (footprint "eagle-import:0603-CAP")
      (libsource (lib "eagle-import") (part "CAPACITOR-0603"))
    )
    (comp (ref "C30")
      (value "100nF")
      (footprint "eagle-import:0603-CAP")
      (libsource (lib "eagle-import") (part "CAPACITOR-0603"))
    )
    (comp (ref "C41")
      (value "100nF")
      (footprint "eagle-import:0603-CAP")
      (libsource (lib "eagle-import") (part "CAPACITOR-0603"))
    )
    (comp (ref "C42")
      (value "4.7nF")
      (footprint "eagle-import:0603-CAP")
      (libsource (lib "eagle-import") (part "CAPACITOR-0603"))
    )
    (comp (ref "C63")
      (value "100nF")
      (footprint "eagle-import:0603-CAP")
      (libsource (lib "eagle-import") (part "CAPACITOR-0603"))
    )
    (comp (ref "C64")
      (value "100nF")
      (footprint "eagle-import:0603-CAP")
      (libsource (lib "eagle-import") (part "CAPACITOR-0603"))
    )
    (comp (ref "C65")
      (value "100nF")
      (footprint "eagle-import:0603-CAP")
      (libsource (lib "eagle-import") (part "CAPACITOR-0603"))
    )
    (comp (ref "C66")
      (value "100nF")
      (footprint "eagle-import:0603-CAP")
      (libsource (lib "eagle-import") (part "CAPACITOR-0603"))
    )
    (comp (ref "C67")
      (value "100nF")
      (footprint "eagle-import:0603-CAP")
      (libsource (lib "eagle-import") (part "CAPACITOR-0603"))
    )
    (comp (ref "C69")
      (value "100nF")
      (footprint "eagle-import:0603-CAP")
      (libsource (lib "eagle-import") (part "CAPACITOR-0603"))
    )
    (comp (ref "CON_I2C2")
      (value "0")
      (footprint "eagle-import:PB-53261-06")
      (libsource (lib "eagle-import") (part "CONN_6-1-53261"))
    )
    (comp (ref "CON_IMU")
      (value "0")
      (footprint "eagle-import:PB-53398-12")
      (libsource (lib "eagle-import") (part "CONN_12-1-53398"))
    )
    (comp (ref "CON_LIGHTS")
      (value "0")
      (footprint "eagle-import:PB-53261-06")
      (libsource (lib "eagle-import") (part "CONN_6-1-53261"))
    )
    (comp (ref "CON_MC1")
      (value "0")
      (footprint "eagle-import:PB-53261-08")
      (libsource (lib "eagle-import") (part "CONN_8-1-53261"))
    )
    (comp (ref "CON_MC2")
      (value "0")
      (footprint "eagle-import:PB-53261-08")
      (libsource (lib "eagle-import") (part "CONN_8-1-53261"))
    )
    (comp (ref "CON_OV_SPI")
      (value "0")
      (footprint "eagle-import:PB-53398-08")
      (libsource (lib "eagle-import") (part "CONN_8-1-53398"))
    )
    (comp (ref "CON_SERVOS_1")
      (value "0")
      (footprint "eagle-import:PB-53261-09")
      (libsource (lib "eagle-import") (part "CONN_9-1-53261"))
    )
    (comp (ref "CON_SERVOS_2")
      (value "0")
      (footprint "eagle-import:PB-53261-09")
      (libsource (lib "eagle-import") (part "CONN_9-1-53261"))
    )
    (comp (ref "CON_SPARE")
      (value "0")
      (footprint "eagle-import:PB-53261-08")
      (libsource (lib "eagle-import") (part "CONN_8-1-53261"))
    )
    (comp (ref "CON_USART1")
      (value "0")
      (footprint "eagle-import:PB-53398-06")
      (libsource (lib "eagle-import") (part "CONN_6-1-53398"))
    )
    (comp (ref "CON_USART2")
      (value "0")
      (footprint "eagle-import:PB-53261-05")
      (libsource (lib "eagle-import") (part "CONN_5-1-53261"))
    )
    (comp (ref "CON_USART3")
      (value "0")
      (footprint "eagle-import:PB-53261-05")
      (libsource (lib "eagle-import") (part "CONN_5-1-53261"))
    )
    (comp (ref "IC1")
      (value "STP08CP05")
      (footprint "eagle-import:TSSOP16")
      (libsource (lib "eagle-import") (part "STP08CP05"))
    )
    (comp (ref "IC6")
      (value "MAX3221CUE")
      (footprint "eagle-import:TSSOP16")
      (libsource (lib "eagle-import") (part "MAX3221UEC"))
    )
    (comp (ref "L3")
      (value "INDUCTOR-0603")
      (footprint "eagle-import:0603-IND")
      (libsource (lib "eagle-import") (part "INDUCTOR-0603"))
    )
    (comp (ref "LED_1")
      (value "LED_DUO")
      (footprint "eagle-import:DUO_LED")
      (libsource (lib "eagle-import") (part "LED_DUO"))
    )
    (comp (ref "LED_2")
      (value "LED_DUO")
      (footprint "eagle-import:DUO_LED")
      (libsource (lib "eagle-import") (part "LED_DUO"))
    )
    (comp (ref "LED_3")
      (value "LED_DUO")
      (footprint "eagle-import:DUO_LED")
      (libsource (lib "eagle-import") (part "LED_DUO"))
    )
    (comp (ref "LED_4")
      (value "LED_DUO")
      (footprint "eagle-import:DUO_LED")
      (libsource (lib "eagle-import") (part "LED_DUO"))
    )
    (comp (ref "LT_I2C1")
      (value "PCA9306DP")
      (footprint "eagle-import:TSSOP_B3")
      (libsource (lib "eagle-import") (part "PCA9306DP"))
    )
    (comp (ref "LT_I2C2")
      (value "PCA9306DP")
      (footprint "eagle-import:TSSOP_B3")
      (libsource (lib "eagle-import") (part "PCA9306DP"))
    )
    (comp (ref "MCU")
      (value "STM32-M-64")
      (footprint "eagle-import:LQFP64")
      (libsource (lib "eagle-import") (part "STM32-M-64"))
    )
    (comp (ref "Q7")
      (value "8MHz")
      (footprint "eagle-import:ASE_OSCILLATOR")
      (libsource (lib "eagle-import") (part "ASE_ASCILLATOR"))
    )
    (comp (ref "R7")
      (value "10k")
      (footprint "eagle-import:0603-RES")
      (libsource (lib "eagle-import") (part "RESISTOR-0603"))
    )
    (comp (ref "R8")
      (value "0/DNP")
      (footprint "eagle-import:0603-RES")
      (libsource (lib "eagle-import") (part "RESISTOR-0603"))
    )
    (comp (ref "R9")
      (value "0/DNP")
      (footprint "eagle-import:0603-RES")
      (libsource (lib "eagle-import") (part "RESISTOR-0603"))
    )
    (comp (ref "R13")
      (value "2k")
      (footprint "eagle-import:0603-RES")
      (libsource (lib "eagle-import") (part "RESISTOR-0603"))
    )
    (comp (ref "R16")
      (value "100k")
      (footprint "eagle-import:0603-RES")
      (libsource (lib "eagle-import") (part "RESISTOR-0603"))
    )
    (comp (ref "R17")
      (value "16k")
      (footprint "eagle-import:0603-RES")
      (libsource (lib "eagle-import") (part "RESISTOR-0603"))
    )
    (comp (ref "R23")
      (value "10k")
      (footprint "eagle-import:0603-RES")
      (libsource (lib "eagle-import") (part "RESISTOR-0603"))
    )
    (comp (ref "R25")
      (value "200k")
      (footprint "eagle-import:0603-RES")
      (libsource (lib "eagle-import") (part "RESISTOR-0603"))
    )
    (comp (ref "R26")
      (value "0/DNP")
      (footprint "eagle-import:0603-RES")
      (libsource (lib "eagle-import") (part "RESISTOR-0603"))
    )
    (comp (ref "R27")
      (value "0/DNP")
      (footprint "eagle-import:0603-RES")
      (libsource (lib "eagle-import") (part "RESISTOR-0603"))
    )
    (comp (ref "R28")
      (value "4.7k")
      (footprint "eagle-import:0603-RES")
      (libsource (lib "eagle-import") (part "RESISTOR-0603"))
    )
    (comp (ref "R29")
      (value "4.7k")
      (footprint "eagle-import:0603-RES")
      (libsource (lib "eagle-import") (part "RESISTOR-0603"))
    )
    (comp (ref "R30")
      (value "200k")
      (footprint "eagle-import:0603-RES")
      (libsource (lib "eagle-import") (part "RESISTOR-0603"))
    )
    (comp (ref "R31")
      (value "0/DNP")
      (footprint "eagle-import:0603-RES")
      (libsource (lib "eagle-import") (part "RESISTOR-0603"))
    )
    (comp (ref "R32")
      (value "0/DNP")
      (footprint "eagle-import:0603-RES")
      (libsource (lib "eagle-import") (part "RESISTOR-0603"))
    )
    (comp (ref "R33")
      (value "4.7k")
      (footprint "eagle-import:0603-RES")
      (libsource (lib "eagle-import") (part "RESISTOR-0603"))
    )
    (comp (ref "R34")
      (value "4.7k")
      (footprint "eagle-import:0603-RES")
      (libsource (lib "eagle-import") (part "RESISTOR-0603"))
    )
    (comp (ref "R36")
      (value "0R/DNP")
      (footprint "eagle-import:0603-RES")
      (libsource (lib "eagle-import") (part "RESISTOR-0603"))
    )
    (comp (ref "R37")
      (value "0R/DNP")
      (footprint "eagle-import:0603-RES")
      (libsource (lib "eagle-import") (part "RESISTOR-0603"))
    )
    (comp (ref "R43")
      (value "4.7k")
      (footprint "eagle-import:0603-RES")
      (libsource (lib "eagle-import") (part "RESISTOR-0603"))
    )
    (comp (ref "R44")
      (value "4.7k")
      (footprint "eagle-import:0603-RES")
      (libsource (lib "eagle-import") (part "RESISTOR-0603"))
    )
    (comp (ref "R45")
      (value "4.7k")
      (footprint "eagle-import:0603-RES")
      (libsource (lib "eagle-import") (part "RESISTOR-0603"))
    )
    (comp (ref "R46")
      (value "4.7k")
      (footprint "eagle-import:0603-RES")
      (libsource (lib "eagle-import") (part "RESISTOR-0603"))
    )
    (comp (ref "R48")
      (value "0/DNP")
      (footprint "eagle-import:0603-RES")
      (libsource (lib "eagle-import") (part "RESISTOR-0603"))
    )
    (comp (ref "R51")
      (value "2k")
      (footprint "eagle-import:0603-RES")
      (libsource (lib "eagle-import") (part "RESISTOR-0603"))
    )
    (comp (ref "R52")
      (value "2k")
      (footprint "eagle-import:0603-RES")
      (libsource (lib "eagle-import") (part "RESISTOR-0603"))
    )
    (comp (ref "R55")
      (value "10k")
      (footprint "eagle-import:0603-RES")
      (libsource (lib "eagle-import") (part "RESISTOR-0603"))
    )
    (comp (ref "R56")
      (value "0R/DNP")
      (footprint "eagle-import:0603-RES")
      (libsource (lib "eagle-import") (part "RESISTOR-0603"))
    )
    (comp (ref "R57")
      (value "120R/DNP")
      (footprint "eagle-import:0603-RES")
      (libsource (lib "eagle-import") (part "RESISTOR-0603"))
    )
    (comp (ref "R58")
      (value "60R/DNP")
      (footprint "eagle-import:0603-RES")
      (libsource (lib "eagle-import") (part "RESISTOR-0603"))
    )
    (comp (ref "R59")
      (value "60R/DNP")
      (footprint "eagle-import:0603-RES")
      (libsource (lib "eagle-import") (part "RESISTOR-0603"))
    )
    (comp (ref "R60")
      (value "4.7k/DNP")
      (footprint "eagle-import:0603-RES")
      (libsource (lib "eagle-import") (part "RESISTOR-0603"))
    )
    (comp (ref "R61")
      (value "4.7k/DNP")
      (footprint "eagle-import:0603-RES")
      (libsource (lib "eagle-import") (part "RESISTOR-0603"))
    )
    (comp (ref "U1")
      (value "MCP2551SN")
      (footprint "eagle-import:SO-08")
      (libsource (lib "eagle-import") (part "MCP2551SN"))
    )
  )
  (nets
    (net (code "1") (name "+1V8") (class "Default")
      (node (ref "C46") (pin "P$1") (pinfunction "1_P$1") (pintype "passive"))
      (node (ref "C51") (pin "P$1") (pinfunction "1_P$1") (pintype "passive"))
      (node (ref "C60") (pin "P$1") (pinfunction "1_P$1") (pintype "passive"))
      (node (ref "LT_3") (pin "P$19") (pinfunction "VCCA_P$19") (pintype "bidirectional"))
      (node (ref "R65") (pin "P$2") (pinfunction "2_P$2") (pintype "passive"))
      (node (ref "REG_1V8") (pin "5") (pinfunction "VCC_5") (pintype "power_in"))
    )
    (net (code "2") (name "+3V3") (class "Default")
      (node (ref "C10") (pin "P$2") (pinfunction "2_P$2") (pintype "passive"))
      (node (ref "C11") (pin "P$2") (pinfunction "2_P$2") (pintype "passive"))
      (node (ref "C12") (pin "P$2") (pinfunction "2_P$2") (pintype "passive"))
      (node (ref "C23") (pin "P$2") (pinfunction "2_P$2") (pintype "passive"))
      (node (ref "C41") (pin "P$2") (pinfunction "2_P$2") (pintype "passive"))
      (node (ref "C44") (pin "+") (pinfunction "+_+") (pintype "passive"))
      (node (ref "C45") (pin "P$1") (pinfunction "1_P$1") (pintype "passive"))
      (node (ref "C47") (pin "P$1") (pinfunction "1_P$1") (pintype "passive"))
      (node (ref "C49") (pin "P$1") (pinfunction "1_P$1") (pintype "passive"))
      (node (ref "C50") (pin "P$1") (pinfunction "1_P$1") (pintype "passive"))
      (node (ref "C59") (pin "P$1") (pinfunction "1_P$1") (pintype "passive"))
      (node (ref "C67") (pin "P$2") (pinfunction "2_P$2") (pintype "passive"))
      (node (ref "CON_I2C2") (pin "3") (pinfunction "3_3") (pintype "bidirectional"))
      (node (ref "CON_OV_SPI") (pin "3") (pinfunction "3_3") (pintype "bidirectional"))
      (node (ref "CON_SPARE") (pin "2") (pinfunction "2_2") (pintype "bidirectional"))
      (node (ref "CON_USART1") (pin "3") (pinfunction "3_3") (pintype "bidirectional"))
      (node (ref "CON_USART2") (pin "3") (pinfunction "3_3") (pintype "bidirectional"))
      (node (ref "CON_USART3") (pin "3") (pinfunction "3_3") (pintype "bidirectional"))
      (node (ref "IC1") (pin "16") (pinfunction "VDD_16") (pintype "bidirectional"))
      (node (ref "IC1") (pin "4") (pinfunction "LE_4") (pintype "bidirectional"))
      (node (ref "IC4") (pin "12") (pinfunction "FORCEON_12") (pintype "input"))
      (node (ref "IC4") (pin "15") (pinfunction "VCC_15") (pintype "power_in"))
      (node (ref "IC4") (pin "16") (pinfunction "~{FORCEOFF}_16") (pintype "input"))
      (node (ref "IC6") (pin "12") (pinfunction "FORCEON_12") (pintype "input"))
      (node (ref "IC6") (pin "15") (pinfunction "VCC_15") (pintype "power_in"))
      (node (ref "IC6") (pin "16") (pinfunction "~{FORCEOFF}_16") (pintype "input"))
      (node (ref "J3&4") (pin "VSYSTEM@1") (pinfunction "VSYSTEM_VSYSTEM@1") (pintype "bidirectional"))
      (node (ref "J3&4") (pin "VSYSTEM@2") (pinfunction "VSYSTEM_VSYSTEM@2") (pintype "bidirectional"))
      (node (ref "J3&4") (pin "VSYSTEM@66") (pinfunction "VSYSTEM_VSYSTEM@66") (pintype "bidirectional"))
      (node (ref "J3&4") (pin "VSYSTEM@67") (pinfunction "VSYSTEM_VSYSTEM@67") (pintype "bidirectional"))
      (node (ref "L3") (pin "P$1") (pinfunction "1_P$1") (pintype "passive"))
      (node (ref "LED_1") (pin "1") (pinfunction "P$1_1") (pintype "bidirectional"))
      (node (ref "LED_1") (pin "4") (pinfunction "P$4_4") (pintype "bidirectional"))
      (node (ref "LED_2") (pin "1") (pinfunction "P$1_1") (pintype "bidirectional"))
      (node (ref "LED_2") (pin "4") (pinfunction "P$4_4") (pintype "bidirectional"))
      (node (ref "LED_3") (pin "1") (pinfunction "P$1_1") (pintype "bidirectional"))
      (node (ref "LED_3") (pin "4") (pinfunction "P$4_4") (pintype "bidirectional"))
      (node (ref "LED_4") (pin "1") (pinfunction "P$1_1") (pintype "bidirectional"))
      (node (ref "LED_4") (pin "4") (pinfunction "P$4_4") (pintype "bidirectional"))
      (node (ref "LT1") (pin "7") (pinfunction "VCCB_7") (pintype "bidirectional"))
      (node (ref "LT_3") (pin "P$18") (pinfunction "VCCY_P$18") (pintype "bidirectional"))
      (node (ref "LT_3") (pin "P$8") (pinfunction "EN_P$8") (pintype "bidirectional"))
      (node (ref "LT_I2C1") (pin "2") (pinfunction "VREF1_2") (pintype "bidirectional"))
      (node (ref "LT_I2C2") (pin "2") (pinfunction "VREF1_2") (pintype "bidirectional"))
      (node (ref "MCU") (pin "1") (pinfunction "VBAT_1") (pintype "power_in"))
      (node (ref "MCU") (pin "19") (pinfunction "VDD4_19") (pintype "bidirectional"))
      (node (ref "MCU") (pin "32") (pinfunction "VDD1_32") (pintype "power_in"))
      (node (ref "MCU") (pin "48") (pinfunction "VDD2_48") (pintype "power_in"))
      (node (ref "MCU") (pin "64") (pinfunction "VDD3_64") (pintype "power_in"))
      (node (ref "Q7") (pin "4") (pinfunction "VDD_4") (pintype "power_in"))
      (node (ref "R26") (pin "P$1") (pinfunction "1_P$1") (pintype "passive"))
      (node (ref "R28") (pin "P$1") (pinfunction "1_P$1") (pintype "passive"))
      (node (ref "R29") (pin "P$1") (pinfunction "1_P$1") (pintype "passive"))
      (node (ref "R31") (pin "P$1") (pinfunction "1_P$1") (pintype "passive"))
      (node (ref "R33") (pin "P$2") (pinfunction "2_P$2") (pintype "passive"))
      (node (ref "R34") (pin "P$2") (pinfunction "2_P$2") (pintype "passive"))
      (node (ref "R7") (pin "P$2") (pinfunction "2_P$2") (pintype "passive"))
      (node (ref "REG_1V8") (pin "1") (pinfunction "V_IN_1") (pintype "input"))
      (node (ref "REG_3V3D") (pin "P$3") (pinfunction "VOUT_P$3") (pintype "bidirectional"))
    )
    (net (code "3") (name "+3V3A") (class "Default")
      (node (ref "ADC1") (pin "P$1") (pinfunction "ADDR_P$1") (pintype "bidirectional"))
      (node (ref "ADC1") (pin "P$8") (pinfunction "VDD_P$8") (pintype "bidirectional"))
      (node (ref "ADC2") (pin "P$8") (pinfunction "VDD_P$8") (pintype "bidirectional"))
      (node (ref "C18") (pin "P$1") (pinfunction "1_P$1") (pintype "passive"))
      (node (ref "C70") (pin "P$1") (pinfunction "1_P$1") (pintype "passive"))
      (node (ref "C71") (pin "P$1") (pinfunction "1_P$1") (pintype "passive"))
      (node (ref "R12") (pin "P$1") (pinfunction "1_P$1") (pintype "passive"))
      (node (ref "R54") (pin "P$1") (pinfunction "1_P$1") (pintype "passive"))
      (node (ref "R64") (pin "P$2") (pinfunction "2_P$2") (pintype "passive"))
      (node (ref "REG3V3A") (pin "5") (pinfunction "OUT_5") (pintype "output"))
    )
    (net (code "4") (name "+5V") (class "Default")
      (node (ref "C13") (pin "P$2") (pinfunction "2_P$2") (pintype "passive"))
      (node (ref "C14") (pin "P$2") (pinfunction "2_P$2") (pintype "passive"))
      (node (ref "C25") (pin "P$2") (pinfunction "2_P$2") (pintype "passive"))
      (node (ref "C28") (pin "P$2") (pinfunction "2_P$2") (pintype "passive"))
      (node (ref "C3") (pin "+") (pinfunction "+_+") (pintype "passive"))
      (node (ref "C30") (pin "P$2") (pinfunction "2_P$2") (pintype "passive"))
      (node (ref "C4") (pin "P$1") (pinfunction "1_P$1") (pintype "passive"))
      (node (ref "C69") (pin "P$2") (pinfunction "2_P$2") (pintype "passive"))
      (node (ref "CON_I2C2") (pin "2") (pinfunction "2_2") (pintype "bidirectional"))
      (node (ref "CON_LIGHTS") (pin "6") (pinfunction "6_6") (pintype "bidirectional"))
      (node (ref "CON_OV_SPI") (pin "2") (pinfunction "2_2") (pintype "bidirectional"))
      (node (ref "CON_OV_UART1") (pin "2") (pinfunction "2_2") (pintype "bidirectional"))
      (node (ref "CON_OV_USBH") (pin "2") (pinfunction "2_2") (pintype "bidirectional"))
      (node (ref "CON_SERVOS_1") (pin "2") (pinfunction "2_2") (pintype "bidirectional"))
      (node (ref "CON_SERVOS_1") (pin "5") (pinfunction "5_5") (pintype "bidirectional"))
      (node (ref "CON_SERVOS_1") (pin "8") (pinfunction "8_8") (pintype "bidirectional"))
      (node (ref "CON_SERVOS_2") (pin "2") (pinfunction "2_2") (pintype "bidirectional"))
      (node (ref "CON_SERVOS_2") (pin "5") (pinfunction "5_5") (pintype "bidirectional"))
      (node (ref "CON_SERVOS_2") (pin "8") (pinfunction "8_8") (pintype "bidirectional"))
      (node (ref "CON_USART1") (pin "2") (pinfunction "2_2") (pintype "bidirectional"))
      (node (ref "CON_USART2") (pin "2") (pinfunction "2_2") (pintype "bidirectional"))
      (node (ref "CON_USART3") (pin "2") (pinfunction "2_2") (pintype "bidirectional"))
      (node (ref "PWS1") (pin "5") (pinfunction "IN_5") (pintype "bidirectional"))
      (node (ref "PWS2") (pin "5") (pinfunction "IN_5") (pintype "bidirectional"))
      (node (ref "R27") (pin "P$1") (pinfunction "1_P$1") (pintype "passive"))
      (node (ref "R32") (pin "P$1") (pinfunction "1_P$1") (pintype "passive"))
      (node (ref "R56") (pin "P$2") (pinfunction "2_P$2") (pintype "passive"))
      (node (ref "R60") (pin "P$1") (pinfunction "1_P$1") (pintype "passive"))
      (node (ref "R70") (pin "P$1") (pinfunction "1_P$1") (pintype "passive"))
      (node (ref "REG_5VD") (pin "P$3") (pinfunction "VOUT_P$3") (pintype "bidirectional"))
      (node (ref "U1") (pin "3") (pinfunction "VDD_3") (pintype "power_in"))
    )
    (net (code "5") (name "+5VA") (class "Default")
      (node (ref "BARO_ABS") (pin "P$2") (pinfunction "VS_P$2") (pintype "bidirectional"))
      (node (ref "BARO_DIF") (pin "P$2") (pinfunction "VS_P$2") (pintype "bidirectional"))
      (node (ref "C26") (pin "P$1") (pinfunction "1_P$1") (pintype "passive"))
      (node (ref "C27") (pin "P$1") (pinfunction "1_P$1") (pintype "passive"))
      (node (ref "C68") (pin "P$1") (pinfunction "1_P$1") (pintype "passive"))
      (node (ref "C8") (pin "P$1") (pinfunction "1_P$1") (pintype "passive"))
      (node (ref "R38") (pin "P$1") (pinfunction "1_P$1") (pintype "passive"))
      (node (ref "R5") (pin "P$1") (pinfunction "1_P$1") (pintype "passive"))
      (node (ref "REG5VA") (pin "5") (pinfunction "OUT_5") (pintype "output"))
      (node (ref "U90") (pin "4") (pinfunction "V+_4") (pintype "power_in"))
    )
    (net (code "6") (name "+6V5") (class "Default")
      (node (ref "C16") (pin "P$1") (pinfunction "1_P$1") (pintype "passive"))
      (node (ref "C17") (pin "P$1") (pinfunction "1_P$1") (pintype "passive"))
      (node (ref "C20") (pin "P$1") (pinfunction "1_P$1") (pintype "passive"))
      (node (ref "C57") (pin "P$1") (pinfunction "1_P$1") (pintype "passive"))
      (node (ref "CON_IMU") (pin "3") (pinfunction "3_3") (pintype "bidirectional"))
      (node (ref "R4") (pin "P$2") (pinfunction "2_P$2") (pintype "passive"))
      (node (ref "REG3V3A") (pin "1") (pinfunction "IN_1") (pintype "input"))
      (node (ref "REG3V3A") (pin "3") (pinfunction "EN_3") (pintype "input"))
      (node (ref "REG5VA") (pin "1") (pinfunction "IN_1") (pintype "input"))
      (node (ref "REG5VA") (pin "3") (pinfunction "EN_3") (pintype "input"))
      (node (ref "REG6V5A") (pin "4") (pinfunction "OUT_4") (pintype "passive"))
      (node (ref "U$1") (pin "P$1") (pinfunction "P$1_P$1") (pintype "bidirectional"))
    )
    (net (code "7") (name "+12V") (class "Default")
      (node (ref "BAT_IN") (pin "P$1") (pinfunction "P$1_P$1") (pintype "bidirectional"))
      (node (ref "BAT_IN1") (pin "P$1") (pinfunction "P$1_P$1") (pintype "bidirectional"))
      (node (ref "C1") (pin "+") (pinfunction "+_+") (pintype "passive"))
      (node (ref "C2") (pin "P$1") (pinfunction "1_P$1") (pintype "passive"))
      (node (ref "C21") (pin "P$1") (pinfunction "1_P$1") (pintype "passive"))
      (node (ref "C22") (pin "+") (pinfunction "+_+") (pintype "passive"))
      (node (ref "C43") (pin "P$1") (pinfunction "1_P$1") (pintype "passive"))
      (node (ref "R16") (pin "P$2") (pinfunction "2_P$2") (pintype "passive"))
      (node (ref "REG6V5A") (pin "3") (pinfunction "IN_3") (pintype "input"))
      (node (ref "REG_3V3D") (pin "P$1") (pinfunction "VIN_P$1") (pintype "bidirectional"))
      (node (ref "REG_5VD") (pin "P$1") (pinfunction "VIN_P$1") (pintype "bidirectional"))
    )
    (net (code "8") (name "ADCIN2") (class "Default")
      (node (ref "J3&4") (pin "ADCIN2") (pinfunction "ADCIN2_ADCIN2") (pintype "bidirectional"))
    )
    (net (code "9") (name "ADCIN3") (class "Default")
      (node (ref "J3&4") (pin "ADCIN3") (pinfunction "ADCIN3_ADCIN3") (pintype "bidirectional"))
    )
    (net (code "10") (name "ADCIN4") (class "Default")
      (node (ref "J3&4") (pin "ADCIN4") (pinfunction "ADCIN4_ADCIN4") (pintype "bidirectional"))
    )
    (net (code "11") (name "ADCIN5") (class "Default")
      (node (ref "J3&4") (pin "ADCIN5") (pinfunction "ADCIN5_ADCIN5") (pintype "bidirectional"))
    )
    (net (code "12") (name "ADCIN6") (class "Default")
      (node (ref "J3&4") (pin "ADCIN6") (pinfunction "ADCIN6_ADCIN6") (pintype "bidirectional"))
    )
    (net (code "13") (name "ADCIN7") (class "Default")
      (node (ref "J3&4") (pin "ADCIN7") (pinfunction "ADCIN7_ADCIN7") (pintype "bidirectional"))
    )
    (net (code "14") (name "BARO_1_DRDY") (class "Default")
      (node (ref "ADC1") (pin "P$2") (pinfunction "DRDY_P$2") (pintype "bidirectional"))
      (node (ref "MCU") (pin "8") (pinfunction "PC0-ADC10_8") (pintype "bidirectional"))
    )
    (net (code "15") (name "BARO_2_DRDY") (class "Default")
      (node (ref "ADC2") (pin "P$2") (pinfunction "DRDY_P$2") (pintype "bidirectional"))
      (node (ref "MCU") (pin "6") (pinfunction "PD1-OSC_OUT_6") (pintype "output"))
    )
    (net (code "16") (name "CAN_H") (class "Default")
      (node (ref "CON_MC1") (pin "3") (pinfunction "3_3") (pintype "bidirectional"))
      (node (ref "CON_MC2") (pin "3") (pinfunction "3_3") (pintype "bidirectional"))
      (node (ref "R57") (pin "P$1") (pinfunction "1_P$1") (pintype "passive"))
      (node (ref "R58") (pin "P$1") (pinfunction "1_P$1") (pintype "passive"))
      (node (ref "U1") (pin "7") (pinfunction "CANH_7") (pintype "bidirectional"))
    )
    (net (code "17") (name "CAN_L") (class "Default")
      (node (ref "CON_MC1") (pin "2") (pinfunction "2_2") (pintype "bidirectional"))
      (node (ref "CON_MC2") (pin "2") (pinfunction "2_2") (pintype "bidirectional"))
      (node (ref "R57") (pin "P$2") (pinfunction "2_P$2") (pintype "passive"))
      (node (ref "R59") (pin "P$2") (pinfunction "2_P$2") (pintype "passive"))
      (node (ref "U1") (pin "6") (pinfunction "CANL_6") (pintype "bidirectional"))
    )
    (net (code "18") (name "FT_1V8") (class "Default")
      (node (ref "C79") (pin "P$1") (pinfunction "1_P$1") (pintype "passive"))
      (node (ref "C80") (pin "P$2") (pinfunction "2_P$2") (pintype "passive"))
      (node (ref "C85") (pin "P$2") (pinfunction "2_P$2") (pintype "passive"))
      (node (ref "C86") (pin "P$2") (pinfunction "2_P$2") (pintype "passive"))
      (node (ref "C87") (pin "P$2") (pinfunction "2_P$2") (pintype "passive"))
      (node (ref "IC3") (pin "P$12") (pinfunction "VCORE1_P$12") (pintype "bidirectional"))
      (node (ref "IC3") (pin "P$37") (pinfunction "VCORE2_P$37") (pintype "bidirectional"))
      (node (ref "IC3") (pin "P$49") (pinfunction "VREGOUT_P$49") (pintype "bidirectional"))
      (node (ref "IC3") (pin "P$64") (pinfunction "VCORE3_P$64") (pintype "bidirectional"))
    )
    (net (code "19") (name "FT_3V3") (class "Default")
      (node (ref "C75") (pin "P$1") (pinfunction "1_P$1") (pintype "passive"))
      (node (ref "C78") (pin "P$2") (pinfunction "2_P$2") (pintype "passive"))
      (node (ref "C88") (pin "P$2") (pinfunction "2_P$2") (pintype "passive"))
      (node (ref "C89") (pin "P$2") (pinfunction "2_P$2") (pintype "passive"))
      (node (ref "C90") (pin "P$2") (pinfunction "2_P$2") (pintype "passive"))
      (node (ref "C91") (pin "P$2") (pinfunction "2_P$2") (pintype "passive"))
      (node (ref "FT_VREG3V3") (pin "5") (pinfunction "OUT_5") (pintype "output"))
      (node (ref "IC2") (pin "6") (pinfunction "VCC_6") (pintype "bidirectional"))
      (node (ref "IC3") (pin "P$20") (pinfunction "VCCIO1_P$20") (pintype "bidirectional"))
      (node (ref "IC3") (pin "P$31") (pinfunction "VCCIO2_P$31") (pintype "bidirectional"))
      (node (ref "IC3") (pin "P$42") (pinfunction "VCCIO3_P$42") (pintype "bidirectional"))
      (node (ref "IC3") (pin "P$50") (pinfunction "VREGIN_P$50") (pintype "bidirectional"))
      (node (ref "IC3") (pin "P$56") (pinfunction "VCCIO4_P$56") (pintype "bidirectional"))
      (node (ref "L1") (pin "P$1") (pinfunction "1_P$1") (pintype "passive"))
      (node (ref "L2") (pin "P$1") (pinfunction "1_P$1") (pintype "passive"))
      (node (ref "R15") (pin "P$2") (pinfunction "2_P$2") (pintype "passive"))
      (node (ref "R76") (pin "P$1") (pinfunction "1_P$1") (pintype "passive"))
      (node (ref "R77") (pin "P$2") (pinfunction "2_P$2") (pintype "passive"))
    )
    (net (code "20") (name "FT_5V") (class "Default")
      (node (ref "C76") (pin "P$1") (pinfunction "1_P$1") (pintype "passive"))
      (node (ref "C77") (pin "P$2") (pinfunction "2_P$2") (pintype "passive"))
      (node (ref "CON_USB1") (pin "1") (pinfunction "1_1") (pintype "input"))
      (node (ref "FT_VREG3V3") (pin "1") (pinfunction "IN_1") (pintype "input"))
      (node (ref "FT_VREG3V3") (pin "3") (pinfunction "EN_3") (pintype "input"))
    )
    (net (code "21") (name "FT_USB_DM") (class "Default")
      (node (ref "CON_USB1") (pin "2") (pinfunction "2_2") (pintype "input"))
      (node (ref "IC3") (pin "P$7") (pinfunction "DM_P$7") (pintype "bidirectional"))
    )
    (net (code "22") (name "FT_USB_DP") (class "Default")
      (node (ref "CON_USB1") (pin "3") (pinfunction "3_3") (pintype "input"))
      (node (ref "IC3") (pin "P$8") (pinfunction "DP_P$8") (pintype "bidirectional"))
    )
    (net (code "23") (name "GND") (class "Default")
      (node (ref "C1") (pin "-") (pinfunction "-_-") (pintype "passive"))
      (node (ref "C10") (pin "P$1") (pinfunction "1_P$1") (pintype "passive"))
      (node (ref "C11") (pin "P$1") (pinfunction "1_P$1") (pintype "passive"))
      (node (ref "C12") (pin "P$1") (pinfunction "1_P$1") (pintype "passive"))
      (node (ref "C13") (pin "P$1") (pinfunction "1_P$1") (pintype "passive"))
      (node (ref "C14") (pin "P$1") (pinfunction "1_P$1") (pintype "passive"))
      (node (ref "C15") (pin "P$1") (pinfunction "1_P$1") (pintype "passive"))
      (node (ref "C16") (pin "P$2") (pinfunction "2_P$2") (pintype "passive"))
      (node (ref "C17") (pin "P$2") (pinfunction "2_P$2") (pintype "passive"))
      (node (ref "C19") (pin "P$2") (pinfunction "2_P$2") (pintype "passive"))
      (node (ref "C2") (pin "P$2") (pinfunction "2_P$2") (pintype "passive"))
      (node (ref "C20") (pin "P$2") (pinfunction "2_P$2") (pintype "passive"))
      (node (ref "C21") (pin "P$2") (pinfunction "2_P$2") (pintype "passive"))
      (node (ref "C22") (pin "-") (pinfunction "-_-") (pintype "passive"))
      (node (ref "C23") (pin "P$1") (pinfunction "1_P$1") (pintype "passive"))
      (node (ref "C25") (pin "P$1") (pinfunction "1_P$1") (pintype "passive"))
      (node (ref "C28") (pin "P$1") (pinfunction "1_P$1") (pintype "passive"))
      (node (ref "C3") (pin "-") (pinfunction "-_-") (pintype "passive"))
      (node (ref "C30") (pin "P$1") (pinfunction "1_P$1") (pintype "passive"))
      (node (ref "C37") (pin "P$2") (pinfunction "2_P$2") (pintype "passive"))
      (node (ref "C38") (pin "P$2") (pinfunction "2_P$2") (pintype "passive"))
      (node (ref "C39") (pin "P$2") (pinfunction "2_P$2") (pintype "passive"))
      (node (ref "C4") (pin "P$2") (pinfunction "2_P$2") (pintype "passive"))
      (node (ref "C40") (pin "P$2") (pinfunction "2_P$2") (pintype "passive"))
      (node (ref "C41") (pin "P$1") (pinfunction "1_P$1") (pintype "passive"))
      (node (ref "C42") (pin "P$1") (pinfunction "1_P$1") (pintype "passive"))
      (node (ref "C43") (pin "P$2") (pinfunction "2_P$2") (pintype "passive"))
      (node (ref "C44") (pin "-") (pinfunction "-_-") (pintype "passive"))
      (node (ref "C45") (pin "P$2") (pinfunction "2_P$2") (pintype "passive"))
      (node (ref "C46") (pin "P$2") (pinfunction "2_P$2") (pintype "passive"))
      (node (ref "C47") (pin "P$2") (pinfunction "2_P$2") (pintype "passive"))
      (node (ref "C48") (pin "P$1") (pinfunction "1_P$1") (pintype "passive"))
      (node (ref "C49") (pin "P$2") (pinfunction "2_P$2") (pintype "passive"))
      (node (ref "C50") (pin "P$2") (pinfunction "2_P$2") (pintype "passive"))
      (node (ref "C51") (pin "P$2") (pinfunction "2_P$2") (pintype "passive"))
      (node (ref "C56") (pin "P$2") (pinfunction "2_P$2") (pintype "passive"))
      (node (ref "C57") (pin "P$2") (pinfunction "2_P$2") (pintype "passive"))
      (node (ref "C59") (pin "P$2") (pinfunction "2_P$2") (pintype "passive"))
      (node (ref "C6") (pin "P$1") (pinfunction "1_P$1") (pintype "passive"))
      (node (ref "C60") (pin "P$2") (pinfunction "2_P$2") (pintype "passive"))
      (node (ref "C61") (pin "P$2") (pinfunction "2_P$2") (pintype "passive"))
      (node (ref "C62") (pin "P$2") (pinfunction "2_P$2") (pintype "passive"))
      (node (ref "C65") (pin "P$2") (pinfunction "2_P$2") (pintype "passive"))
      (node (ref "C66") (pin "P$2") (pinfunction "2_P$2") (pintype "passive"))
      (node (ref "C67") (pin "P$1") (pinfunction "1_P$1") (pintype "passive"))
      (node (ref "C69") (pin "P$1") (pinfunction "1_P$1") (pintype "passive"))
      (node (ref "C7") (pin "P$1") (pinfunction "1_P$1") (pintype "passive"))
      (node (ref "C72") (pin "P$1") (pinfunction "1_P$1") (pintype "passive"))
      (node (ref "C73") (pin "P$1") (pinfunction "1_P$1") (pintype "passive"))
      (node (ref "C74") (pin "P$1") (pinfunction "1_P$1") (pintype "passive"))
      (node (ref "C75") (pin "P$2") (pinfunction "2_P$2") (pintype "passive"))
      (node (ref "C76") (pin "P$2") (pinfunction "2_P$2") (pintype "passive"))
      (node (ref "C77") (pin "P$1") (pinfunction "1_P$1") (pintype "passive"))
      (node (ref "C78") (pin "P$1") (pinfunction "1_P$1") (pintype "passive"))
      (node (ref "C79") (pin "P$2") (pinfunction "2_P$2") (pintype "passive"))
      (node (ref "C80") (pin "P$1") (pinfunction "1_P$1") (pintype "passive"))
      (node (ref "C81") (pin "P$2") (pinfunction "2_P$2") (pintype "passive"))
      (node (ref "C82") (pin "P$2") (pinfunction "2_P$2") (pintype "passive"))
      (node (ref "C83") (pin "P$2") (pinfunction "2_P$2") (pintype "passive"))
      (node (ref "C84") (pin "P$2") (pinfunction "2_P$2") (pintype "passive"))
      (node (ref "C85") (pin "P$1") (pinfunction "1_P$1") (pintype "passive"))
      (node (ref "C86") (pin "P$1") (pinfunction "1_P$1") (pintype "passive"))
      (node (ref "C87") (pin "P$1") (pinfunction "1_P$1") (pintype "passive"))
      (node (ref "C88") (pin "P$1") (pinfunction "1_P$1") (pintype "passive"))
      (node (ref "C89") (pin "P$1") (pinfunction "1_P$1") (pintype "passive"))
      (node (ref "C9") (pin "P$1") (pinfunction "1_P$1") (pintype "passive"))
      (node (ref "C90") (pin "P$1") (pinfunction "1_P$1") (pintype "passive"))
      (node (ref "C91") (pin "P$1") (pinfunction "1_P$1") (pintype "passive"))
      (node (ref "CON_I2C2") (pin "1") (pinfunction "1_1") (pintype "bidirectional"))
      (node (ref "CON_IMU") (pin "1") (pinfunction "1_1") (pintype "bidirectional"))
      (node (ref "CON_IMU") (pin "2") (pinfunction "2_2") (pintype "bidirectional"))
      (node (ref "CON_LIGHTS") (pin "1") (pinfunction "1_1") (pintype "bidirectional"))
      (node (ref "CON_LIGHTS") (pin "3") (pinfunction "3_3") (pintype "bidirectional"))
      (node (ref "CON_LIGHTS") (pin "5") (pinfunction "5_5") (pintype "bidirectional"))
      (node (ref "CON_MC1") (pin "1") (pinfunction "1_1") (pintype "bidirectional"))
      (node (ref "CON_MC2") (pin "1") (pinfunction "1_1") (pintype "bidirectional"))
      (node (ref "CON_OV_SPI") (pin "1") (pinfunction "1_1") (pintype "bidirectional"))
      (node (ref "CON_OV_UART1") (pin "1") (pinfunction "1_1") (pintype "bidirectional"))
      (node (ref "CON_OV_USBH") (pin "1") (pinfunction "1_1") (pintype "bidirectional"))
      (node (ref "CON_SERVOS_1") (pin "1") (pinfunction "1_1") (pintype "bidirectional"))
      (node (ref "CON_SERVOS_1") (pin "4") (pinfunction "4_4") (pintype "bidirectional"))
      (node (ref "CON_SERVOS_1") (pin "7") (pinfunction "7_7") (pintype "bidirectional"))
      (node (ref "CON_SERVOS_2") (pin "1") (pinfunction "1_1") (pintype "bidirectional"))
      (node (ref "CON_SERVOS_2") (pin "4") (pinfunction "4_4") (pintype "bidirectional"))
      (node (ref "CON_SERVOS_2") (pin "7") (pinfunction "7_7") (pintype "bidirectional"))
      (node (ref "CON_SPARE") (pin "1") (pinfunction "1_1") (pintype "bidirectional"))
      (node (ref "CON_USART1") (pin "1") (pinfunction "1_1") (pintype "bidirectional"))
      (node (ref "CON_USART2") (pin "1") (pinfunction "1_1") (pintype "bidirectional"))
      (node (ref "CON_USART3") (pin "1") (pinfunction "1_1") (pintype "bidirectional"))
      (node (ref "CON_USB1") (pin "5") (pinfunction "5_5") (pintype "input"))
      (node (ref "FT_VREG3V3") (pin "2") (pinfunction "GND_2") (pintype "power_in"))
      (node (ref "GND_IN") (pin "P$1") (pinfunction "P$1_P$1") (pintype "bidirectional"))
      (node (ref "GND_IN1") (pin "P$1") (pinfunction "P$1_P$1") (pintype "bidirectional"))
      (node (ref "IC1") (pin "1") (pinfunction "GND_1") (pintype "bidirectional"))
      (node (ref "IC1") (pin "13") (pinfunction "~{OE}_13") (pintype "bidirectional"))
      (node (ref "IC2") (pin "2") (pinfunction "VSS_2") (pintype "bidirectional"))
      (node (ref "IC3") (pin "P$1") (pinfunction "GND1_P$1") (pintype "bidirectional"))
      (node (ref "IC3") (pin "P$10") (pinfunction "AGND_P$10") (pintype "bidirectional"))
      (node (ref "IC3") (pin "P$11") (pinfunction "GND3_P$11") (pintype "bidirectional"))
      (node (ref "IC3") (pin "P$13") (pinfunction "TEST_P$13") (pintype "bidirectional"))
      (node (ref "IC3") (pin "P$15") (pinfunction "GND4_P$15") (pintype "bidirectional"))
      (node (ref "IC3") (pin "P$25") (pinfunction "GND5_P$25") (pintype "bidirectional"))
      (node (ref "IC3") (pin "P$35") (pinfunction "GND6_P$35") (pintype "bidirectional"))
      (node (ref "IC3") (pin "P$47") (pinfunction "GND7_P$47") (pintype "bidirectional"))
      (node (ref "IC3") (pin "P$5") (pinfunction "GND2_P$5") (pintype "bidirectional"))
      (node (ref "IC3") (pin "P$51") (pinfunction "GND8_P$51") (pintype "bidirectional"))
      (node (ref "IC3") (pin "P$65") (pinfunction "CENTER_PAD_P$65") (pintype "bidirectional"))
      (node (ref "IC4") (pin "1") (pinfunction "~{EN}_1") (pintype "input"))
      (node (ref "IC4") (pin "14") (pinfunction "GND_14") (pintype "power_in"))
      (node (ref "IC6") (pin "1") (pinfunction "~{EN}_1") (pintype "input"))
      (node (ref "IC6") (pin "14") (pinfunction "GND_14") (pintype "power_in"))
      (node (ref "J3&4") (pin "AGND") (pinfunction "AGND_AGND") (pintype "bidirectional"))
      (node (ref "J3&4") (pin "GND") (pinfunction "GND_GND") (pintype "bidirectional"))
      (node (ref "J3&4") (pin "GND@33") (pinfunction "GND_GND@33") (pintype "bidirectional"))
      (node (ref "J3&4") (pin "GND@56") (pinfunction "GND_GND@56") (pintype "bidirectional"))
      (node (ref "J3&4") (pin "GND@70") (pinfunction "GND_GND@70") (pintype "bidirectional"))
      (node (ref "LED_FT") (pin "C") (pinfunction "C_C") (pintype "passive"))
      (node (ref "LED_JRXD") (pin "C") (pinfunction "C_C") (pintype "passive"))
      (node (ref "LED_JTXD") (pin "C") (pinfunction "C_C") (pintype "passive"))
      (node (ref "LT1") (pin "2") (pinfunction "GND_2") (pintype "bidirectional"))
      (node (ref "LT_3") (pin "P$21") (pinfunction "PAD_P$21") (pintype "bidirectional"))
      (node (ref "LT_3") (pin "P$9") (pinfunction "GND_P$9") (pintype "bidirectional"))
      (node (ref "LT_I2C1") (pin "1") (pinfunction "GND_1") (pintype "bidirectional"))
      (node (ref "LT_I2C2") (pin "1") (pinfunction "GND_1") (pintype "bidirectional"))
      (node (ref "MCU") (pin "12") (pinfunction "VSSA_12") (pintype "power_in"))
      (node (ref "MCU") (pin "18") (pinfunction "VSS4_18") (pintype "bidirectional"))
      (node (ref "MCU") (pin "31") (pinfunction "VSS1_31") (pintype "power_in"))
      (node (ref "MCU") (pin "47") (pinfunction "VSS2_47") (pintype "power_in"))
      (node (ref "MCU") (pin "63") (pinfunction "VSS3_63") (pintype "power_in"))
      (node (ref "PWS1") (pin "2") (pinfunction "GND_2") (pintype "bidirectional"))
      (node (ref "PWS2") (pin "2") (pinfunction "GND_2") (pintype "bidirectional"))
      (node (ref "Q3") (pin "P$2") (pinfunction "P$2_P$2") (pintype "bidirectional"))
      (node (ref "Q3") (pin "P$4") (pinfunction "P$4_P$4") (pintype "bidirectional"))
      (node (ref "Q7") (pin "2") (pinfunction "GND_2") (pintype "power_in"))
      (node (ref "R13") (pin "P$1") (pinfunction "1_P$1") (pintype "passive"))
      (node (ref "R14") (pin "P$1") (pinfunction "1_P$1") (pintype "passive"))
      (node (ref "R17") (pin "P$1") (pinfunction "1_P$1") (pintype "passive"))
      (node (ref "R23") (pin "P$1") (pinfunction "1_P$1") (pintype "passive"))
      (node (ref "R3") (pin "P$1") (pinfunction "1_P$1") (pintype "passive"))
      (node (ref "R51") (pin "P$1") (pinfunction "1_P$1") (pintype "passive"))
      (node (ref "R52") (pin "P$1") (pinfunction "1_P$1") (pintype "passive"))
      (node (ref "R55") (pin "P$1") (pinfunction "1_P$1") (pintype "passive"))
      (node (ref "R61") (pin "P$2") (pinfunction "2_P$2") (pintype "passive"))
      (node (ref "R62") (pin "P$1") (pinfunction "1_P$1") (pintype "passive"))
      (node (ref "R66") (pin "P$1") (pinfunction "1_P$1") (pintype "passive"))
      (node (ref "R75") (pin "P$1") (pinfunction "1_P$1") (pintype "passive"))
      (node (ref "REG3V3A") (pin "2") (pinfunction "GND_2") (pintype "power_in"))
      (node (ref "REG5VA") (pin "2") (pinfunction "GND_2") (pintype "power_in"))
      (node (ref "REG_1V8") (pin "2") (pinfunction "GND_2") (pintype "power_in"))
      (node (ref "REG_3V3D") (pin "P$2") (pinfunction "GND_P$2") (pintype "bidirectional"))
      (node (ref "REG_5VD") (pin "P$2") (pinfunction "GND_P$2") (pintype "bidirectional"))
      (node (ref "U$4") (pin "P$1") (pinfunction "P$1_P$1") (pintype "bidirectional"))
      (node (ref "U1") (pin "2") (pinfunction "VSS_2") (pintype "power_in"))
      (node (ref "~NUDEV~1") (pin "GND") (pinfunction "GND_GND") (pintype "power_in"))
    )
    (net (code "24") (name "GNDA") (class "Default")
      (node (ref "ADC1") (pin "P$3") (pinfunction "GND_P$3") (pintype "bidirectional"))
      (node (ref "ADC2") (pin "P$1") (pinfunction "ADDR_P$1") (pintype "bidirectional"))
      (node (ref "ADC2") (pin "P$3") (pinfunction "GND_P$3") (pintype "bidirectional"))
      (node (ref "BARO_ABS") (pin "P$3") (pinfunction "GND_P$3") (pintype "bidirectional"))
      (node (ref "BARO_DIF") (pin "P$3") (pinfunction "GND_P$3") (pintype "bidirectional"))
      (node (ref "C18") (pin "P$2") (pinfunction "2_P$2") (pintype "passive"))
      (node (ref "C26") (pin "P$2") (pinfunction "2_P$2") (pintype "passive"))
      (node (ref "C27") (pin "P$2") (pinfunction "2_P$2") (pintype "passive"))
      (node (ref "C32") (pin "P$1") (pinfunction "1_P$1") (pintype "passive"))
      (node (ref "C36") (pin "P$1") (pinfunction "1_P$1") (pintype "passive"))
      (node (ref "C68") (pin "P$2") (pinfunction "2_P$2") (pintype "passive"))
      (node (ref "C70") (pin "P$2") (pinfunction "2_P$2") (pintype "passive"))
      (node (ref "C71") (pin "P$2") (pinfunction "2_P$2") (pintype "passive"))
      (node (ref "C8") (pin "P$2") (pinfunction "2_P$2") (pintype "passive"))
      (node (ref "R2") (pin "P$2") (pinfunction "2_P$2") (pintype "passive"))
      (node (ref "R35") (pin "P$1") (pinfunction "1_P$1") (pintype "passive"))
      (node (ref "R39") (pin "P$2") (pinfunction "2_P$2") (pintype "passive"))
      (node (ref "R53") (pin "P$1") (pinfunction "1_P$1") (pintype "passive"))
      (node (ref "R6") (pin "P$2") (pinfunction "2_P$2") (pintype "passive"))
      (node (ref "R63") (pin "P$1") (pinfunction "1_P$1") (pintype "passive"))
      (node (ref "R68") (pin "P$1") (pinfunction "1_P$1") (pintype "passive"))
      (node (ref "U90") (pin "11") (pinfunction "V-_11") (pintype "power_in"))
      (node (ref "~NUDEV~1") (pin "GNDA") (pinfunction "GNDA_GNDA") (pintype "power_in"))
    )
    (net (code "25") (name "GPIO0_WAKEUP") (class "Default")
      (node (ref "J3&4") (pin "GPIO0_WAKEUP") (pinfunction "GPIO0_WAKEUP_GPIO0_WAKEUP") (pintype "bidirectional"))
    )
    (net (code "26") (name "GPIO12_MMC3_CLK") (class "Default")
      (node (ref "J3&4") (pin "GPIO12_MMC3_CLK") (pinfunction "GPIO12_MMC3_CLK_GPIO12_MMC3_CLK") (pintype "bidirectional"))
    )
    (net (code "27") (name "GPIO13_MMC3_CMD") (class "Default")
      (node (ref "J3&4") (pin "GPIO13_MMC3_CMD") (pinfunction "GPIO13_MMC3_CMD_GPIO13_MMC3_CMD") (pintype "bidirectional"))
    )
    (net (code "28") (name "GPIO14_MMC3_D4") (class "Default")
      (node (ref "J3&4") (pin "GPIO14_MMC3_DAT4") (pinfunction "GPIO14_MMC3_DAT4_GPIO14_MMC3_DAT4") (pintype "bidirectional"))
    )
    (net (code "29") (name "GPIO17_MMC3_D3") (class "Default")
      (node (ref "J3&4") (pin "GPIO17_MMC3_D3") (pinfunction "GPIO17_MMC3_D3_GPIO17_MMC3_D3") (pintype "bidirectional"))
    )
    (net (code "30") (name "GPIO18_MMC3_D0") (class "Default")
      (node (ref "J3&4") (pin "GPIO18_MMC3_D0") (pinfunction "GPIO18_MMC3_D0_GPIO18_MMC3_D0") (pintype "bidirectional"))
    )
    (net (code "31") (name "GPIO18_MMC3_D2") (class "Default")
      (node (ref "J3&4") (pin "GPIO20_MMC3_D2") (pinfunction "GPIO20_MMC3_D2_GPIO20_MMC3_D2") (pintype "bidirectional"))
    )
    (net (code "32") (name "GPIO19_MMC3_D1") (class "Default")
      (node (ref "J3&4") (pin "GPIO19_MMC3_D1") (pinfunction "GPIO19_MMC3_D1_GPIO19_MMC3_D1") (pintype "bidirectional"))
    )
    (net (code "33") (name "GPIO21_MMC3_D7") (class "Default")
      (node (ref "J3&4") (pin "GPIO21_MMC3_DAT7") (pinfunction "GPIO21_MMC3_DAT7_GPIO21_MMC3_DAT7") (pintype "bidirectional"))
    )
    (net (code "34") (name "GPIO22_MMC3_D6") (class "Default")
      (node (ref "J3&4") (pin "GPIO22_MMC3_DAT6") (pinfunction "GPIO22_MMC3_DAT6_GPIO22_MMC3_DAT6") (pintype "bidirectional"))
    )
    (net (code "35") (name "GPIO23_MMC3_D5") (class "Default")
      (node (ref "J3&4") (pin "GPIO23_MMC3_DAT5") (pinfunction "GPIO23_MMC3_DAT5_GPIO23_MMC3_DAT5") (pintype "bidirectional"))
    )
    (net (code "36") (name "GPIO41_OTG_ID") (class "Default")
      (node (ref "CON_OV_USB_OTG") (pin "5") (pinfunction "5_5") (pintype "bidirectional"))
      (node (ref "J3&4") (pin "USBOTG_ID") (pinfunction "USBOTG_ID_USBOTG_ID") (pintype "bidirectional"))
    )
    (net (code "37") (name "GPIO127_TS_IRQ") (class "Default")
      (node (ref "J3&4") (pin "GPIO127_TS_IRQ") (pinfunction "GPIO127_TS_IRQ_GPIO127_TS_IRQ") (pintype "bidirectional"))
    )
    (net (code "38") (name "GPIO128_GPS_PPS") (class "Default")
      (node (ref "J3&4") (pin "GPIO128_GPS_PPS") (pinfunction "GPIO128_GPS_PPS_GPIO128_GPS_PPS") (pintype "bidirectional"))
    )
    (net (code "39") (name "GPIO144_PWM9") (class "Default")
      (node (ref "J3&4") (pin "GPIO144_GPT9_PWM") (pinfunction "GPIO144_GPT9_PWM_GPIO144_GPT9_PWM") (pintype "bidirectional"))
    )
    (net (code "40") (name "GPIO145_PWM10") (class "Default")
      (node (ref "J3&4") (pin "GPIO145_GPT10_PWM") (pinfunction "GPIO145_GPT10_PWM_GPIO145_GPT10_PWM") (pintype "bidirectional"))
    )
    (net (code "41") (name "GPIO146_PWM11") (class "Default")
      (node (ref "J3&4") (pin "GPIO146_GPT11_PWM") (pinfunction "GPIO146_GPT11_PWM_GPIO146_GPT11_PWM") (pintype "bidirectional"))
    )
    (net (code "42") (name "GPIO147_PWM8") (class "Default")
      (node (ref "J3&4") (pin "GPIO147_GPT8_PWM") (pinfunction "GPIO147_GPT8_PWM_GPIO147_GPT8_PWM") (pintype "bidirectional"))
    )
    (net (code "43") (name "GPIO149_MMC3_CD") (class "Default")
      (node (ref "J3&4") (pin "GPIO149_MMC3_CD") (pinfunction "GPIO149_MMC3_CD_GPIO149_MMC3_CD") (pintype "bidirectional"))
    )
    (net (code "44") (name "GPIO150_MMC3_WP") (class "Default")
      (node (ref "J3&4") (pin "GPIO150_MMC3_WP") (pinfunction "GPIO150_MMC3_WP_GPIO150_MMC3_WP") (pintype "bidirectional"))
    )
    (net (code "45") (name "GPIO163_IR_CTS3") (class "Default")
      (node (ref "J3&4") (pin "GPIO163_IR_CTS3") (pinfunction "GPIO163_IR_CTS3_GPIO163_IR_CTS3") (pintype "bidirectional"))
    )
    (net (code "46") (name "GPIO165_IR_RXD3") (class "Default")
      (node (ref "J3&4") (pin "GPIO165_IR_RXD3") (pinfunction "GPIO165_IR_RXD3_GPIO165_IR_RXD3") (pintype "bidirectional"))
      (node (ref "LT1") (pin "4") (pinfunction "A2_4") (pintype "bidirectional"))
    )
    (net (code "47") (name "GPIO166_IR_TXD3") (class "Default")
      (node (ref "J3&4") (pin "GPIO166_IR_TXD3") (pinfunction "GPIO166_IR_TXD3_GPIO166_IR_TXD3") (pintype "bidirectional"))
      (node (ref "LT1") (pin "5") (pinfunction "A1_5") (pintype "bidirectional"))
    )
    (net (code "48") (name "GPIO168_USBH_CPEN") (class "Default")
      (node (ref "J3&4") (pin "GPIO168_USBH_CPEN") (pinfunction "GPIO168_USBH_CPEN_GPIO168_USBH_CPEN") (pintype "bidirectional"))
    )
    (net (code "49") (name "GPIO170_HDQ_1WIRE") (class "Default")
      (node (ref "J3&4") (pin "GPIO170_HDQ_1WIRE") (pinfunction "GPIO170_HDQ_1WIRE_GPIO170_HDQ_1WIRE") (pintype "bidirectional"))
    )
    (net (code "50") (name "GPIO176_ETH0_IRQ") (class "Default")
      (node (ref "J3&4") (pin "GPIO176_ETH0_IRQ") (pinfunction "GPIO176_ETH0_IRQ_GPIO176_ETH0_IRQ") (pintype "bidirectional"))
    )
    (net (code "51") (name "GPIO184_SCL3") (class "Default")
      (node (ref "J3&4") (pin "GPIO184_I2C3_SCL") (pinfunction "GPIO184_I2C3_SCL_GPIO184_I2C3_SCL") (pintype "bidirectional"))
    )
    (net (code "52") (name "GPIO185_SDA3") (class "Default")
      (node (ref "J3&4") (pin "GPIO185_I2C3_SDA") (pinfunction "GPIO185_I2C3_SDA_GPIO185_I2C3_SDA") (pintype "bidirectional"))
    )
    (net (code "53") (name "HSOL") (class "Default")
      (node (ref "J3&4") (pin "HSOLF") (pinfunction "HSOLF_HSOLF") (pintype "bidirectional"))
      (node (ref "U$3") (pin "P$1") (pinfunction "P$1_P$1") (pintype "bidirectional"))
    )
    (net (code "54") (name "HSOR") (class "Default")
      (node (ref "J3&4") (pin "HSORF") (pinfunction "HSORF_HSORF") (pintype "bidirectional"))
      (node (ref "U$2") (pin "P$1") (pinfunction "P$1_P$1") (pintype "bidirectional"))
    )
    (net (code "55") (name "LED_1_G") (class "Default")
      (node (ref "IC1") (pin "5") (pinfunction "OUT0_5") (pintype "bidirectional"))
      (node (ref "LED_1") (pin "3") (pinfunction "P$3_3") (pintype "bidirectional"))
    )
    (net (code "56") (name "LED_1_R") (class "Default")
      (node (ref "IC1") (pin "6") (pinfunction "OUT1_6") (pintype "bidirectional"))
      (node (ref "LED_1") (pin "2") (pinfunction "P$2_2") (pintype "bidirectional"))
    )
    (net (code "57") (name "LED_2_G") (class "Default")
      (node (ref "IC1") (pin "7") (pinfunction "OUT2_7") (pintype "bidirectional"))
      (node (ref "LED_2") (pin "3") (pinfunction "P$3_3") (pintype "bidirectional"))
    )
    (net (code "58") (name "LED_2_R") (class "Default")
      (node (ref "IC1") (pin "8") (pinfunction "OUT3_8") (pintype "bidirectional"))
      (node (ref "LED_2") (pin "2") (pinfunction "P$2_2") (pintype "bidirectional"))
    )
    (net (code "59") (name "LED_3_G") (class "Default")
      (node (ref "IC1") (pin "9") (pinfunction "OUT4_9") (pintype "bidirectional"))
      (node (ref "LED_3") (pin "3") (pinfunction "P$3_3") (pintype "bidirectional"))
    )
    (net (code "60") (name "LED_3_R") (class "Default")
      (node (ref "IC1") (pin "10") (pinfunction "OUT5_10") (pintype "bidirectional"))
      (node (ref "LED_3") (pin "2") (pinfunction "P$2_2") (pintype "bidirectional"))
    )
    (net (code "61") (name "LED_4_G") (class "Default")
      (node (ref "IC1") (pin "11") (pinfunction "OUT6_11") (pintype "bidirectional"))
      (node (ref "LED_4") (pin "3") (pinfunction "P$3_3") (pintype "bidirectional"))
    )
    (net (code "62") (name "LED_4_R") (class "Default")
      (node (ref "IC1") (pin "12") (pinfunction "OUT7_12") (pintype "bidirectional"))
      (node (ref "LED_4") (pin "2") (pinfunction "P$2_2") (pintype "bidirectional"))
    )
    (net (code "63") (name "LINE_IN_LA") (class "Default")
      (node (ref "J3&4") (pin "AUXRF") (pinfunction "AUXRF_AUXRF") (pintype "bidirectional"))
      (node (ref "U$5") (pin "P$1") (pinfunction "P$1_P$1") (pintype "bidirectional"))
    )
    (net (code "64") (name "LINE_IN_RA") (class "Default")
      (node (ref "J3&4") (pin "AUXLF") (pinfunction "AUXLF_AUXLF") (pintype "bidirectional"))
      (node (ref "U$6") (pin "P$1") (pinfunction "P$1_P$1") (pintype "bidirectional"))
    )
    (net (code "65") (name "LT_I2C1_SUP") (class "Default")
      (node (ref "CON_MC1") (pin "4") (pinfunction "4_4") (pintype "bidirectional"))
      (node (ref "CON_MC2") (pin "4") (pinfunction "4_4") (pintype "bidirectional"))
      (node (ref "R30") (pin "P$1") (pinfunction "1_P$1") (pintype "passive"))
      (node (ref "R31") (pin "P$2") (pinfunction "2_P$2") (pintype "passive"))
      (node (ref "R32") (pin "P$2") (pinfunction "2_P$2") (pintype "passive"))
      (node (ref "R45") (pin "P$1") (pinfunction "1_P$1") (pintype "passive"))
      (node (ref "R46") (pin "P$1") (pinfunction "1_P$1") (pintype "passive"))
    )
    (net (code "66") (name "LT_I2C2_SCL") (class "Default")
      (node (ref "CON_I2C2") (pin "5") (pinfunction "5_5") (pintype "bidirectional"))
      (node (ref "LT_I2C2") (pin "6") (pinfunction "SCL2_6") (pintype "bidirectional"))
      (node (ref "R44") (pin "P$1") (pinfunction "1_P$1") (pintype "passive"))
    )
    (net (code "67") (name "LT_I2C2_SDA") (class "Default")
      (node (ref "CON_I2C2") (pin "6") (pinfunction "6_6") (pintype "bidirectional"))
      (node (ref "LT_I2C2") (pin "5") (pinfunction "SDA2_5") (pintype "bidirectional"))
      (node (ref "R43") (pin "P$1") (pinfunction "1_P$1") (pintype "passive"))
    )
    (net (code "68") (name "LT_I2C2_SUP") (class "Default")
      (node (ref "CON_I2C2") (pin "4") (pinfunction "4_4") (pintype "bidirectional"))
      (node (ref "R25") (pin "P$2") (pinfunction "2_P$2") (pintype "passive"))
      (node (ref "R26") (pin "P$2") (pinfunction "2_P$2") (pintype "passive"))
      (node (ref "R27") (pin "P$2") (pinfunction "2_P$2") (pintype "passive"))
      (node (ref "R43") (pin "P$2") (pinfunction "2_P$2") (pintype "passive"))
      (node (ref "R44") (pin "P$2") (pinfunction "2_P$2") (pintype "passive"))
    )
    (net (code "69") (name "LT_USART1_RX") (class "Default")
      (node (ref "CON_USART1") (pin "5") (pinfunction "5_5") (pintype "bidirectional"))
      (node (ref "IC6") (pin "8") (pinfunction "R1IN_8") (pintype "input"))
      (node (ref "R37") (pin "P$1") (pinfunction "1_P$1") (pintype "passive"))
    )
    (net (code "70") (name "LT_USART1_TX") (class "Default")
      (node (ref "CON_USART1") (pin "4") (pinfunction "4_4") (pintype "bidirectional"))
      (node (ref "IC6") (pin "13") (pinfunction "T1OUT_13") (pintype "output"))
      (node (ref "R36") (pin "P$1") (pinfunction "1_P$1") (pintype "passive"))
    )
    (net (code "71") (name "L_BIAS") (class "Default")
      (node (ref "J3&4") (pin "GPIO69_L_BIAS") (pinfunction "GPIO69_L_BIAS_GPIO69_L_BIAS") (pintype "bidirectional"))
    )
    (net (code "72") (name "L_DD0") (class "Default")
      (node (ref "J3&4") (pin "GPIO70_L_DD00") (pinfunction "GPIO70_L_DD00_GPIO70_L_DD00") (pintype "bidirectional"))
    )
    (net (code "73") (name "L_DD1") (class "Default")
      (node (ref "J3&4") (pin "GPIO71_L_DD01") (pinfunction "GPIO71_L_DD01_GPIO71_L_DD01") (pintype "bidirectional"))
    )
    (net (code "74") (name "L_DD2") (class "Default")
      (node (ref "J3&4") (pin "GPIO72_L_DD02") (pinfunction "GPIO72_L_DD02_GPIO72_L_DD02") (pintype "bidirectional"))
    )
    (net (code "75") (name "L_DD3") (class "Default")
      (node (ref "J3&4") (pin "GPIO73_L_DD03") (pinfunction "GPIO73_L_DD03_GPIO73_L_DD03") (pintype "bidirectional"))
    )
    (net (code "76") (name "L_DD4") (class "Default")
      (node (ref "J3&4") (pin "GPIO74_L_DD04") (pinfunction "GPIO74_L_DD04_GPIO74_L_DD04") (pintype "bidirectional"))
    )
    (net (code "77") (name "L_DD5") (class "Default")
      (node (ref "J3&4") (pin "GPIO75_L_DD05") (pinfunction "GPIO75_L_DD05_GPIO75_L_DD05") (pintype "bidirectional"))
    )
    (net (code "78") (name "L_DD6") (class "Default")
      (node (ref "J3&4") (pin "GPIO76_L_DD06") (pinfunction "GPIO76_L_DD06_GPIO76_L_DD06") (pintype "bidirectional"))
    )
    (net (code "79") (name "L_DD7") (class "Default")
      (node (ref "J3&4") (pin "GPIO77_L_DD07") (pinfunction "GPIO77_L_DD07_GPIO77_L_DD07") (pintype "bidirectional"))
    )
    (net (code "80") (name "L_DD8") (class "Default")
      (node (ref "J3&4") (pin "GPIO78_L_DD08") (pinfunction "GPIO78_L_DD08_GPIO78_L_DD08") (pintype "bidirectional"))
    )
    (net (code "81") (name "L_DD9") (class "Default")
      (node (ref "J3&4") (pin "GPIO79_L_DD09") (pinfunction "GPIO79_L_DD09_GPIO79_L_DD09") (pintype "bidirectional"))
    )
    (net (code "82") (name "L_DD10") (class "Default")
      (node (ref "J3&4") (pin "GPIO80_L_DD10") (pinfunction "GPIO80_L_DD10_GPIO80_L_DD10") (pintype "bidirectional"))
    )
    (net (code "83") (name "L_DD11") (class "Default")
      (node (ref "J3&4") (pin "GPIO81_L_DD11") (pinfunction "GPIO81_L_DD11_GPIO81_L_DD11") (pintype "bidirectional"))
    )
    (net (code "84") (name "L_DD12") (class "Default")
      (node (ref "J3&4") (pin "GPIO82_L_DD12") (pinfunction "GPIO82_L_DD12_GPIO82_L_DD12") (pintype "bidirectional"))
    )
    (net (code "85") (name "L_DD13") (class "Default")
      (node (ref "J3&4") (pin "GPIO83_L_DD13") (pinfunction "GPIO83_L_DD13_GPIO83_L_DD13") (pintype "bidirectional"))
    )
    (net (code "86") (name "L_DD14") (class "Default")
      (node (ref "J3&4") (pin "GPIO84_L_DD14") (pinfunction "GPIO84_L_DD14_GPIO84_L_DD14") (pintype "bidirectional"))
    )
    (net (code "87") (name "L_DD15") (class "Default")
      (node (ref "J3&4") (pin "GPIO85_L_DD15") (pinfunction "GPIO85_L_DD15_GPIO85_L_DD15") (pintype "bidirectional"))
    )
    (net (code "88") (name "L_DD16") (class "Default")
      (node (ref "J3&4") (pin "GPIO86_L_DD16") (pinfunction "GPIO86_L_DD16_GPIO86_L_DD16") (pintype "bidirectional"))
    )
    (net (code "89") (name "L_DD17") (class "Default")
      (node (ref "J3&4") (pin "GPIO87_L_DD17") (pinfunction "GPIO87_L_DD17_GPIO87_L_DD17") (pintype "bidirectional"))
    )
    (net (code "90") (name "L_DD18") (class "Default")
      (node (ref "J3&4") (pin "GPIO88_L_DD18") (pinfunction "GPIO88_L_DD18_GPIO88_L_DD18") (pintype "bidirectional"))
    )
    (net (code "91") (name "L_DD19") (class "Default")
      (node (ref "J3&4") (pin "GPIO89_L_DD19") (pinfunction "GPIO89_L_DD19_GPIO89_L_DD19") (pintype "bidirectional"))
    )
    (net (code "92") (name "L_DD20") (class "Default")
      (node (ref "J3&4") (pin "GPIO90_L_DD20") (pinfunction "GPIO90_L_DD20_GPIO90_L_DD20") (pintype "bidirectional"))
    )
    (net (code "93") (name "L_DD21") (class "Default")
      (node (ref "J3&4") (pin "GPIO91_L_DD21") (pinfunction "GPIO91_L_DD21_GPIO91_L_DD21") (pintype "bidirectional"))
    )
    (net (code "94") (name "L_DD22") (class "Default")
      (node (ref "J3&4") (pin "GPIO92_L_DD22") (pinfunction "GPIO92_L_DD22_GPIO92_L_DD22") (pintype "bidirectional"))
    )
    (net (code "95") (name "L_DD23") (class "Default")
      (node (ref "J3&4") (pin "GPIO93_L_DD23") (pinfunction "GPIO93_L_DD23_GPIO93_L_DD23") (pintype "bidirectional"))
    )
    (net (code "96") (name "L_HSYNC") (class "Default")
      (node (ref "J3&4") (pin "GPIO67_L_LCLK") (pinfunction "GPIO67_L_LCLK_GPIO67_L_LCLK") (pintype "bidirectional"))
    )
    (net (code "97") (name "L_PCLK") (class "Default")
      (node (ref "J3&4") (pin "GPIO66_L_PCLK") (pinfunction "GPIO66_L_PCLK_GPIO66_L_PCLK") (pintype "bidirectional"))
    )
    (net (code "98") (name "L_VSYNC") (class "Default")
      (node (ref "J3&4") (pin "GPIO68_L_FCLK") (pinfunction "GPIO68_L_FCLK_GPIO68_L_FCLK") (pintype "bidirectional"))
    )
    (net (code "99") (name "MIC_MAIN") (class "Default")
      (node (ref "J3&4") (pin "MIC_MAIN_MF") (pinfunction "MIC_MAIN_MF_MIC_MAIN_MF") (pintype "bidirectional"))
    )
    (net (code "100") (name "MIC_SUB") (class "Default")
      (node (ref "J3&4") (pin "MIC_SUB_MF") (pinfunction "MIC_SUB_MF_MIC_SUB_MF") (pintype "bidirectional"))
    )
    (net (code "101") (name "NRESET") (class "Default")
      (node (ref "J3&4") (pin "N_MANUAL_RESET") (pinfunction "N_MANUAL_RESET_N_MANUAL_RESET") (pintype "bidirectional"))
    )
    (net (code "102") (name "Net-(ADC1-AIN1)") (class "Default")
      (node (ref "ADC1") (pin "P$5") (pinfunction "AIN1_P$5") (pintype "bidirectional"))
      (node (ref "R12") (pin "P$2") (pinfunction "2_P$2") (pintype "passive"))
      (node (ref "R53") (pin "P$2") (pinfunction "2_P$2") (pintype "passive"))
    )
    (net (code "103") (name "Net-(ADC2-AIN1)") (class "Default")
      (node (ref "ADC2") (pin "P$5") (pinfunction "AIN1_P$5") (pintype "bidirectional"))
      (node (ref "R54") (pin "P$2") (pinfunction "2_P$2") (pintype "passive"))
      (node (ref "R63") (pin "P$2") (pinfunction "2_P$2") (pintype "passive"))
    )
    (net (code "104") (name "Net-(ADC2-AIN2)") (class "Default")
      (node (ref "ADC2") (pin "P$6") (pinfunction "AIN2_P$6") (pintype "bidirectional"))
      (node (ref "R69") (pin "P$2") (pinfunction "2_P$2") (pintype "passive"))
    )
    (net (code "105") (name "Net-(ADC2-AIN3)") (class "Default")
      (node (ref "ADC2") (pin "P$7") (pinfunction "AIN3_P$7") (pintype "bidirectional"))
      (node (ref "R64") (pin "P$1") (pinfunction "1_P$1") (pintype "passive"))
      (node (ref "R68") (pin "P$2") (pinfunction "2_P$2") (pintype "passive"))
    )
    (net (code "106") (name "Net-(BARO_ABS-VO)") (class "Default")
      (node (ref "BARO_ABS") (pin "P$4") (pinfunction "VO_P$4") (pintype "bidirectional"))
      (node (ref "R22") (pin "P$2") (pinfunction "2_P$2") (pintype "passive"))
    )
    (net (code "107") (name "Net-(BARO_DIF-VO)") (class "Default")
      (node (ref "BARO_DIF") (pin "P$4") (pinfunction "VO_P$4") (pintype "bidirectional"))
      (node (ref "R1") (pin "P$1") (pinfunction "1_P$1") (pintype "passive"))
    )
    (net (code "108") (name "Net-(C5-1)") (class "Default")
      (node (ref "C5") (pin "P$1") (pinfunction "1_P$1") (pintype "passive"))
      (node (ref "IC4") (pin "2") (pinfunction "C1+_2") (pintype "passive"))
    )
    (net (code "109") (name "Net-(C5-2)") (class "Default")
      (node (ref "C5") (pin "P$2") (pinfunction "2_P$2") (pintype "passive"))
      (node (ref "IC4") (pin "4") (pinfunction "C1-_4") (pintype "passive"))
    )
    (net (code "110") (name "Net-(C6-2)") (class "Default")
      (node (ref "C6") (pin "P$2") (pinfunction "2_P$2") (pintype "passive"))
      (node (ref "IC4") (pin "3") (pinfunction "V+_3") (pintype "passive"))
    )
    (net (code "111") (name "Net-(C15-2)") (class "Default")
      (node (ref "C15") (pin "P$2") (pinfunction "2_P$2") (pintype "passive"))
      (node (ref "C7") (pin "P$2") (pinfunction "2_P$2") (pintype "passive"))
      (node (ref "L3") (pin "P$2") (pinfunction "2_P$2") (pintype "passive"))
      (node (ref "MCU") (pin "13") (pinfunction "VDDA_13") (pintype "power_in"))
    )
    (net (code "112") (name "Net-(C19-1)") (class "Default")
      (node (ref "C19") (pin "P$1") (pinfunction "1_P$1") (pintype "passive"))
      (node (ref "REG3V3A") (pin "4") (pinfunction "ADJ_4") (pintype "passive"))
    )
    (net (code "113") (name "Net-(C24-2)") (class "Default")
      (node (ref "C24") (pin "P$2") (pinfunction "2_P$2") (pintype "passive"))
      (node (ref "R10") (pin "P$1") (pinfunction "1_P$1") (pintype "passive"))
      (node (ref "R21") (pin "P$1") (pinfunction "1_P$1") (pintype "passive"))
    )
    (net (code "114") (name "Net-(C31-2)") (class "Default")
      (node (ref "C31") (pin "P$2") (pinfunction "2_P$2") (pintype "passive"))
      (node (ref "R11") (pin "P$1") (pinfunction "1_P$1") (pintype "passive"))
      (node (ref "R18") (pin "P$1") (pinfunction "1_P$1") (pintype "passive"))
    )
    (net (code "115") (name "Net-(C32-2)") (class "Default")
      (node (ref "C32") (pin "P$2") (pinfunction "2_P$2") (pintype "passive"))
      (node (ref "R11") (pin "P$2") (pinfunction "2_P$2") (pintype "passive"))
      (node (ref "U90") (pin "5") (pinfunction "+IN_5") (pintype "input"))
    )
    (net (code "116") (name "Net-(C35-1)") (class "Default")
      (node (ref "C35") (pin "P$1") (pinfunction "1_P$1") (pintype "passive"))
      (node (ref "IC4") (pin "5") (pinfunction "C2+_5") (pintype "passive"))
    )
    (net (code "117") (name "Net-(C35-2)") (class "Default")
      (node (ref "C35") (pin "P$2") (pinfunction "2_P$2") (pintype "passive"))
      (node (ref "IC4") (pin "6") (pinfunction "C2-_6") (pintype "passive"))
    )
    (net (code "118") (name "Net-(C36-2)") (class "Default")
      (node (ref "C36") (pin "P$2") (pinfunction "2_P$2") (pintype "passive"))
      (node (ref "R10") (pin "P$2") (pinfunction "2_P$2") (pintype "passive"))
      (node (ref "U90") (pin "12") (pinfunction "+IN_12") (pintype "input"))
    )
    (net (code "119") (name "Net-(C42-2)") (class "Default")
      (node (ref "C42") (pin "P$2") (pinfunction "2_P$2") (pintype "passive"))
      (node (ref "R58") (pin "P$2") (pinfunction "2_P$2") (pintype "passive"))
      (node (ref "R59") (pin "P$1") (pinfunction "1_P$1") (pintype "passive"))
      (node (ref "R60") (pin "P$2") (pinfunction "2_P$2") (pintype "passive"))
      (node (ref "R61") (pin "P$1") (pinfunction "1_P$1") (pintype "passive"))
    )
    (net (code "120") (name "Net-(C48-2)") (class "Default")
      (node (ref "C48") (pin "P$2") (pinfunction "2_P$2") (pintype "passive"))
      (node (ref "IC4") (pin "7") (pinfunction "V-_7") (pintype "passive"))
    )
    (net (code "121") (name "Net-(C56-1)") (class "Default")
      (node (ref "C56") (pin "P$1") (pinfunction "1_P$1") (pintype "passive"))
      (node (ref "REG5VA") (pin "4") (pinfunction "ADJ_4") (pintype "passive"))
    )
    (net (code "122") (name "Net-(C61-1)") (class "Default")
      (node (ref "C61") (pin "P$1") (pinfunction "1_P$1") (pintype "passive"))
      (node (ref "CON_OV_USB_OTG") (pin "1") (pinfunction "1_1") (pintype "bidirectional"))
      (node (ref "R66") (pin "P$2") (pinfunction "2_P$2") (pintype "passive"))
    )
    (net (code "123") (name "Net-(C62-1)") (class "Default")
      (node (ref "C62") (pin "P$1") (pinfunction "1_P$1") (pintype "passive"))
      (node (ref "CON_OV_USB_OTG") (pin "2") (pinfunction "2_2") (pintype "bidirectional"))
      (node (ref "R67") (pin "P$2") (pinfunction "2_P$2") (pintype "passive"))
    )
    (net (code "124") (name "Net-(C63-1)") (class "Default")
      (node (ref "C63") (pin "P$1") (pinfunction "1_P$1") (pintype "passive"))
      (node (ref "IC6") (pin "2") (pinfunction "C1+_2") (pintype "passive"))
    )
    (net (code "125") (name "Net-(C63-2)") (class "Default")
      (node (ref "C63") (pin "P$2") (pinfunction "2_P$2") (pintype "passive"))
      (node (ref "IC6") (pin "4") (pinfunction "C1-_4") (pintype "passive"))
    )
    (net (code "126") (name "Net-(C64-1)") (class "Default")
      (node (ref "C64") (pin "P$1") (pinfunction "1_P$1") (pintype "passive"))
      (node (ref "IC6") (pin "5") (pinfunction "C2+_5") (pintype "passive"))
    )
    (net (code "127") (name "Net-(C64-2)") (class "Default")
      (node (ref "C64") (pin "P$2") (pinfunction "2_P$2") (pintype "passive"))
      (node (ref "IC6") (pin "6") (pinfunction "C2-_6") (pintype "passive"))
    )
    (net (code "128") (name "Net-(C65-1)") (class "Default")
      (node (ref "C65") (pin "P$1") (pinfunction "1_P$1") (pintype "passive"))
      (node (ref "IC6") (pin "3") (pinfunction "V+_3") (pintype "passive"))
    )
    (net (code "129") (name "Net-(C66-1)") (class "Default")
      (node (ref "C66") (pin "P$1") (pinfunction "1_P$1") (pintype "passive"))
      (node (ref "IC6") (pin "7") (pinfunction "V-_7") (pintype "passive"))
    )
    (net (code "130") (name "Net-(C72-2)") (class "Default")
      (node (ref "C72") (pin "P$2") (pinfunction "2_P$2") (pintype "passive"))
      (node (ref "IC3") (pin "P$2") (pinfunction "OSCI_P$2") (pintype "bidirectional"))
      (node (ref "Q3") (pin "P$3") (pinfunction "P$3_P$3") (pintype "bidirectional"))
    )
    (net (code "131") (name "Net-(C73-2)") (class "Default")
      (node (ref "C73") (pin "P$2") (pinfunction "2_P$2") (pintype "passive"))
      (node (ref "IC3") (pin "P$3") (pinfunction "OSCO_P$3") (pintype "bidirectional"))
      (node (ref "Q3") (pin "P$1") (pinfunction "P$1_P$1") (pintype "bidirectional"))
    )
    (net (code "132") (name "Net-(C74-2)") (class "Default")
      (node (ref "C74") (pin "P$2") (pinfunction "2_P$2") (pintype "passive"))
      (node (ref "FT_VREG3V3") (pin "4") (pinfunction "BYP_4") (pintype "passive"))
    )
    (net (code "133") (name "Net-(C81-1)") (class "Default")
      (node (ref "C81") (pin "P$1") (pinfunction "1_P$1") (pintype "passive"))
      (node (ref "C83") (pin "P$1") (pinfunction "1_P$1") (pintype "passive"))
      (node (ref "IC3") (pin "P$4") (pinfunction "VPHY_P$4") (pintype "bidirectional"))
      (node (ref "L2") (pin "P$2") (pinfunction "2_P$2") (pintype "passive"))
    )
    (net (code "134") (name "Net-(C82-1)") (class "Default")
      (node (ref "C82") (pin "P$1") (pinfunction "1_P$1") (pintype "passive"))
      (node (ref "C84") (pin "P$1") (pinfunction "1_P$1") (pintype "passive"))
      (node (ref "IC3") (pin "P$9") (pinfunction "VPLL_P$9") (pintype "bidirectional"))
      (node (ref "L1") (pin "P$2") (pinfunction "2_P$2") (pintype "passive"))
    )
    (net (code "135") (name "Net-(IC1-R-EXT)") (class "Default")
      (node (ref "IC1") (pin "15") (pinfunction "R-EXT_15") (pintype "bidirectional"))
      (node (ref "R13") (pin "P$2") (pinfunction "2_P$2") (pintype "passive"))
    )
    (net (code "136") (name "Net-(IC2-CLK)") (class "Default")
      (node (ref "IC2") (pin "4") (pinfunction "CLK_4") (pintype "bidirectional"))
      (node (ref "IC3") (pin "P$62") (pinfunction "EECLK_P$62") (pintype "bidirectional"))
    )
    (net (code "137") (name "Net-(IC2-CS)") (class "Default")
      (node (ref "IC2") (pin "5") (pinfunction "CS_5") (pintype "bidirectional"))
      (node (ref "IC3") (pin "P$63") (pinfunction "EECS_P$63") (pintype "bidirectional"))
    )
    (net (code "138") (name "Net-(IC2-DI)") (class "Default")
      (node (ref "IC2") (pin "3") (pinfunction "DI_3") (pintype "bidirectional"))
      (node (ref "IC3") (pin "P$61") (pinfunction "EEDATA_P$61") (pintype "bidirectional"))
      (node (ref "R77") (pin "P$1") (pinfunction "1_P$1") (pintype "passive"))
      (node (ref "R78") (pin "P$1") (pinfunction "1_P$1") (pintype "passive"))
    )
    (net (code "139") (name "Net-(IC2-DO)") (class "Default")
      (node (ref "IC2") (pin "1") (pinfunction "DO_1") (pintype "bidirectional"))
      (node (ref "R78") (pin "P$2") (pinfunction "2_P$2") (pintype "passive"))
    )
    (net (code "140") (name "Net-(IC3-ADBUS0)") (class "Default")
      (node (ref "IC3") (pin "P$16") (pinfunction "ADBUS0_P$16") (pintype "bidirectional"))
      (node (ref "R49") (pin "P$1") (pinfunction "1_P$1") (pintype "passive"))
    )
    (net (code "141") (name "Net-(IC3-ADBUS1)") (class "Default")
      (node (ref "IC3") (pin "P$17") (pinfunction "ADBUS1_P$17") (pintype "bidirectional"))
      (node (ref "R50") (pin "P$1") (pinfunction "1_P$1") (pintype "passive"))
    )
    (net (code "142") (name "Net-(IC3-BCBUS3)") (class "Default")
      (node (ref "IC3") (pin "P$54") (pinfunction "BCBUS3_P$54") (pintype "bidirectional"))
      (node (ref "R24") (pin "P$2") (pinfunction "2_P$2") (pintype "passive"))
    )
    (net (code "143") (name "Net-(IC3-BCBUS4)") (class "Default")
      (node (ref "IC3") (pin "P$55") (pinfunction "BCBUS4_P$55") (pintype "bidirectional"))
      (node (ref "R71") (pin "P$2") (pinfunction "2_P$2") (pintype "passive"))
    )
    (net (code "144") (name "Net-(IC3-REF)") (class "Default")
      (node (ref "IC3") (pin "P$6") (pinfunction "REF_P$6") (pintype "bidirectional"))
      (node (ref "R75") (pin "P$2") (pinfunction "2_P$2") (pintype "passive"))
    )
    (net (code "145") (name "Net-(IC3-RESET#)") (class "Default")
      (node (ref "IC3") (pin "P$14") (pinfunction "RESET#_P$14") (pintype "bidirectional"))
      (node (ref "R76") (pin "P$2") (pinfunction "2_P$2") (pintype "passive"))
    )
    (net (code "146") (name "Net-(LT1-OE)") (class "Default")
      (node (ref "LT1") (pin "3") (pinfunction "VCCA_3") (pintype "bidirectional"))
      (node (ref "LT1") (pin "6") (pinfunction "OE_6") (pintype "bidirectional"))
      (node (ref "R65") (pin "P$1") (pinfunction "1_P$1") (pintype "passive"))
    )
    (net (code "147") (name "Net-(LT_I2C1-EN)") (class "Default")
      (node (ref "LT_I2C1") (pin "7") (pinfunction "VREF2_7") (pintype "bidirectional"))
      (node (ref "LT_I2C1") (pin "8") (pinfunction "EN_8") (pintype "bidirectional"))
      (node (ref "R30") (pin "P$2") (pinfunction "2_P$2") (pintype "passive"))
    )
    (net (code "148") (name "Net-(LT_I2C1-SCL2)") (class "Default")
      (node (ref "CON_MC1") (pin "6") (pinfunction "6_6") (pintype "bidirectional"))
      (node (ref "CON_MC1") (pin "8") (pinfunction "8_8") (pintype "bidirectional"))
      (node (ref "CON_MC2") (pin "6") (pinfunction "6_6") (pintype "bidirectional"))
      (node (ref "CON_MC2") (pin "8") (pinfunction "8_8") (pintype "bidirectional"))
      (node (ref "LT_I2C1") (pin "6") (pinfunction "SCL2_6") (pintype "bidirectional"))
      (node (ref "R45") (pin "P$2") (pinfunction "2_P$2") (pintype "passive"))
    )
    (net (code "149") (name "Net-(LT_I2C1-SDA2)") (class "Default")
      (node (ref "CON_MC1") (pin "5") (pinfunction "5_5") (pintype "bidirectional"))
      (node (ref "CON_MC1") (pin "7") (pinfunction "7_7") (pintype "bidirectional"))
      (node (ref "CON_MC2") (pin "5") (pinfunction "5_5") (pintype "bidirectional"))
      (node (ref "CON_MC2") (pin "7") (pinfunction "7_7") (pintype "bidirectional"))
      (node (ref "LT_I2C1") (pin "5") (pinfunction "SDA2_5") (pintype "bidirectional"))
      (node (ref "R46") (pin "P$2") (pinfunction "2_P$2") (pintype "passive"))
    )
    (net (code "150") (name "Net-(LT_I2C2-EN)") (class "Default")
      (node (ref "LT_I2C2") (pin "7") (pinfunction "VREF2_7") (pintype "bidirectional"))
      (node (ref "LT_I2C2") (pin "8") (pinfunction "EN_8") (pintype "bidirectional"))
      (node (ref "R25") (pin "P$1") (pinfunction "1_P$1") (pintype "passive"))
    )
    (net (code "151") (name "Net-(MCU-PD0-OSC_IN)") (class "Default")
      (node (ref "MCU") (pin "5") (pinfunction "PD0-OSC_IN_5") (pintype "input"))
      (node (ref "Q7") (pin "3") (pinfunction "OUT_3") (pintype "output"))
    )
    (net (code "152") (name "Net-(R1-2)") (class "Default")
      (node (ref "R1") (pin "P$2") (pinfunction "2_P$2") (pintype "passive"))
      (node (ref "R2") (pin "P$1") (pinfunction "1_P$1") (pintype "passive"))
      (node (ref "U90") (pin "3") (pinfunction "+IN_3") (pintype "input"))
    )
    (net (code "153") (name "Net-(R3-2)") (class "Default")
      (node (ref "R3") (pin "P$2") (pinfunction "2_P$2") (pintype "passive"))
      (node (ref "R4") (pin "P$1") (pinfunction "1_P$1") (pintype "passive"))
      (node (ref "REG6V5A") (pin "1") (pinfunction "ADJ_1") (pintype "input"))
    )
    (net (code "154") (name "Net-(R14-2)") (class "Default")
      (node (ref "R14") (pin "P$2") (pinfunction "2_P$2") (pintype "passive"))
      (node (ref "REG_5VD") (pin "P$4") (pinfunction "ADJ_P$4") (pintype "bidirectional"))
    )
    (net (code "155") (name "Net-(R15-1)") (class "Default")
      (node (ref "LED_FT") (pin "A") (pinfunction "A_A") (pintype "passive"))
      (node (ref "R15") (pin "P$1") (pinfunction "1_P$1") (pintype "passive"))
    )
    (net (code "156") (name "Net-(R18-2)") (class "Default")
      (node (ref "R18") (pin "P$2") (pinfunction "2_P$2") (pintype "passive"))
      (node (ref "R20") (pin "P$1") (pinfunction "1_P$1") (pintype "passive"))
      (node (ref "U90") (pin "1") (pinfunction "OUT_1") (pintype "output"))
    )
    (net (code "157") (name "Net-(R19-1)") (class "Default")
      (node (ref "R19") (pin "P$1") (pinfunction "1_P$1") (pintype "passive"))
      (node (ref "R20") (pin "P$2") (pinfunction "2_P$2") (pintype "passive"))
      (node (ref "U90") (pin "2") (pinfunction "-IN_2") (pintype "input"))
    )
    (net (code "158") (name "Net-(R19-2)") (class "Default")
      (node (ref "R19") (pin "P$2") (pinfunction "2_P$2") (pintype "passive"))
      (node (ref "R5") (pin "P$2") (pinfunction "2_P$2") (pintype "passive"))
      (node (ref "R6") (pin "P$1") (pinfunction "1_P$1") (pintype "passive"))
    )
    (net (code "159") (name "Net-(R21-2)") (class "Default")
      (node (ref "R21") (pin "P$2") (pinfunction "2_P$2") (pintype "passive"))
      (node (ref "R47") (pin "P$1") (pinfunction "1_P$1") (pintype "passive"))
      (node (ref "U90") (pin "8") (pinfunction "OUT_8") (pintype "output"))
    )
    (net (code "160") (name "Net-(R22-1)") (class "Default")
      (node (ref "R22") (pin "P$1") (pinfunction "1_P$1") (pintype "passive"))
      (node (ref "R35") (pin "P$2") (pinfunction "2_P$2") (pintype "passive"))
      (node (ref "U90") (pin "10") (pinfunction "+IN_10") (pintype "input"))
    )
    (net (code "161") (name "Net-(R24-1)") (class "Default")
      (node (ref "LED_JTXD") (pin "A") (pinfunction "A_A") (pintype "passive"))
      (node (ref "R24") (pin "P$1") (pinfunction "1_P$1") (pintype "passive"))
    )
    (net (code "162") (name "Net-(R38-2)") (class "Default")
      (node (ref "R38") (pin "P$2") (pinfunction "2_P$2") (pintype "passive"))
      (node (ref "R39") (pin "P$1") (pinfunction "1_P$1") (pintype "passive"))
      (node (ref "R40") (pin "P$2") (pinfunction "2_P$2") (pintype "passive"))
    )
    (net (code "163") (name "Net-(R40-1)") (class "Default")
      (node (ref "R40") (pin "P$1") (pinfunction "1_P$1") (pintype "passive"))
      (node (ref "R47") (pin "P$2") (pinfunction "2_P$2") (pintype "passive"))
      (node (ref "U90") (pin "9") (pinfunction "-IN_9") (pintype "input"))
    )
    (net (code "164") (name "Net-(R48-2)") (class "Default")
      (node (ref "CON_USART1") (pin "6") (pinfunction "6_6") (pintype "bidirectional"))
      (node (ref "R48") (pin "P$2") (pinfunction "2_P$2") (pintype "passive"))
    )
    (net (code "165") (name "Net-(R55-2)") (class "Default")
      (node (ref "R55") (pin "P$2") (pinfunction "2_P$2") (pintype "passive"))
      (node (ref "R56") (pin "P$1") (pinfunction "1_P$1") (pintype "passive"))
      (node (ref "U1") (pin "8") (pinfunction "RS_8") (pintype "input"))
    )
    (net (code "166") (name "Net-(R62-2)") (class "Default")
      (node (ref "R62") (pin "P$2") (pinfunction "2_P$2") (pintype "passive"))
      (node (ref "REG_3V3D") (pin "P$4") (pinfunction "ADJ_P$4") (pintype "bidirectional"))
    )
    (net (code "167") (name "Net-(R71-1)") (class "Default")
      (node (ref "LED_JRXD") (pin "A") (pinfunction "A_A") (pintype "passive"))
      (node (ref "R71") (pin "P$1") (pinfunction "1_P$1") (pintype "passive"))
    )
    (net (code "168") (name "OVERO_RXD3_3V3") (class "Default")
      (node (ref "CON_OV_UART3") (pin "2") (pinfunction "2_2") (pintype "bidirectional"))
      (node (ref "LT1") (pin "1") (pinfunction "B2_1") (pintype "bidirectional"))
      (node (ref "R49") (pin "P$2") (pinfunction "2_P$2") (pintype "passive"))
    )
    (net (code "169") (name "OVERO_TXD3_3V3") (class "Default")
      (node (ref "CON_OV_UART3") (pin "1") (pinfunction "1_1") (pintype "bidirectional"))
      (node (ref "LT1") (pin "8") (pinfunction "B1_8") (pintype "bidirectional"))
      (node (ref "R50") (pin "P$2") (pinfunction "2_P$2") (pintype "passive"))
    )
    (net (code "170") (name "OV_GPIO114_SPI1_NIRQ") (class "Default")
      (node (ref "J3&4") (pin "GPIO114_SPI1_NIRQ") (pinfunction "GPIO114_SPI1_NIRQ_GPIO114_SPI1_NIRQ") (pintype "bidirectional"))
      (node (ref "LT_3") (pin "P$7") (pinfunction "A8_P$7") (pintype "bidirectional"))
    )
    (net (code "171") (name "OV_GPIO148_TXD1") (class "Default")
      (node (ref "J3&4") (pin "GPIO148_TXD1") (pinfunction "GPIO148_TXD1_GPIO148_TXD1") (pintype "bidirectional"))
      (node (ref "LT_3") (pin "P$20") (pinfunction "A1_P$20") (pintype "bidirectional"))
    )
    (net (code "172") (name "OV_GPIO151_RXD1") (class "Default")
      (node (ref "J3&4") (pin "GPIO151_RXD1") (pinfunction "GPIO151_RXD1_GPIO151_RXD1") (pintype "bidirectional"))
      (node (ref "LT_3") (pin "P$1") (pinfunction "A2_P$1") (pintype "bidirectional"))
    )
    (net (code "173") (name "OV_GPIO171_SPI1_CLK") (class "Default")
      (node (ref "J3&4") (pin "GPIO171_SPI1_CLK") (pinfunction "GPIO171_SPI1_CLK_GPIO171_SPI1_CLK") (pintype "bidirectional"))
      (node (ref "LT_3") (pin "P$5") (pinfunction "A6_P$5") (pintype "bidirectional"))
    )
    (net (code "174") (name "OV_GPIO172_SPI1_MOSI") (class "Default")
      (node (ref "J3&4") (pin "GPIO172_SPI1_MOSI") (pinfunction "GPIO172_SPI1_MOSI_GPIO172_SPI1_MOSI") (pintype "bidirectional"))
      (node (ref "LT_3") (pin "P$4") (pinfunction "A5_P$4") (pintype "bidirectional"))
    )
    (net (code "175") (name "OV_GPIO173_SPI1_MISO") (class "Default")
      (node (ref "J3&4") (pin "GPIO173_SPI1_MISO") (pinfunction "GPIO173_SPI1_MISO_GPIO173_SPI1_MISO") (pintype "bidirectional"))
      (node (ref "LT_3") (pin "P$3") (pinfunction "A4_P$3") (pintype "bidirectional"))
    )
    (net (code "176") (name "OV_GPIO174_SPI1_CS0") (class "Default")
      (node (ref "J3&4") (pin "GPIO174_SPI1_CS0") (pinfunction "GPIO174_SPI1_CS0_GPIO174_SPI1_CS0") (pintype "bidirectional"))
      (node (ref "LT_3") (pin "P$2") (pinfunction "A3_P$2") (pintype "bidirectional"))
    )
    (net (code "177") (name "OV_GPIO175_SPI1_CS1") (class "Default")
      (node (ref "J3&4") (pin "GPIO175_SPI1_CS1") (pinfunction "GPIO175_SPI1_CS1_GPIO175_SPI1_CS1") (pintype "bidirectional"))
      (node (ref "LT_3") (pin "P$6") (pinfunction "A7_P$6") (pintype "bidirectional"))
    )
    (net (code "178") (name "OV_RXD1_3V3") (class "Default")
      (node (ref "IC4") (pin "9") (pinfunction "R1OUT_9") (pintype "output"))
      (node (ref "LT_3") (pin "P$16") (pinfunction "Y2_P$16") (pintype "bidirectional"))
      (node (ref "R42") (pin "P$1") (pinfunction "1_P$1") (pintype "passive"))
    )
    (net (code "179") (name "OV_SPI_CS0") (class "Default")
      (node (ref "CON_OV_SPI") (pin "4") (pinfunction "4_4") (pintype "bidirectional"))
      (node (ref "LT_3") (pin "P$15") (pinfunction "Y3_P$15") (pintype "bidirectional"))
    )
    (net (code "180") (name "OV_TXD1_3V3") (class "Default")
      (node (ref "IC4") (pin "11") (pinfunction "T1IN_11") (pintype "input"))
      (node (ref "LT_3") (pin "P$17") (pinfunction "Y1_P$17") (pintype "bidirectional"))
      (node (ref "R41") (pin "P$1") (pinfunction "1_P$1") (pintype "passive"))
    )
    (net (code "181") (name "OV_UART1_RXD_LT") (class "Default")
      (node (ref "CON_OV_UART1") (pin "4") (pinfunction "4_4") (pintype "bidirectional"))
      (node (ref "IC4") (pin "8") (pinfunction "R1IN_8") (pintype "input"))
      (node (ref "R42") (pin "P$2") (pinfunction "2_P$2") (pintype "passive"))
    )
    (net (code "182") (name "OV_UART1_TXD_LT") (class "Default")
      (node (ref "CON_OV_UART1") (pin "3") (pinfunction "3_3") (pintype "bidirectional"))
      (node (ref "IC4") (pin "13") (pinfunction "T1OUT_13") (pintype "output"))
      (node (ref "R41") (pin "P$2") (pinfunction "2_P$2") (pintype "passive"))
    )
    (net (code "183") (name "OV_USBH_DM") (class "Default")
      (node (ref "CON_OV_USBH") (pin "4") (pinfunction "4_4") (pintype "bidirectional"))
      (node (ref "J3&4") (pin "USBH_DM") (pinfunction "USBH_DM_USBH_DM") (pintype "bidirectional"))
    )
    (net (code "184") (name "OV_USBH_DP") (class "Default")
      (node (ref "CON_OV_USBH") (pin "3") (pinfunction "3_3") (pintype "bidirectional"))
      (node (ref "J3&4") (pin "USBH_DP") (pinfunction "USBH_DP_USBH_DP") (pintype "bidirectional"))
    )
    (net (code "185") (name "OV_USB_OTG_DM") (class "Default")
      (node (ref "CON_OV_USB_OTG") (pin "4") (pinfunction "4_4") (pintype "bidirectional"))
      (node (ref "J3&4") (pin "USBOTG_DM") (pinfunction "USBOTG_DM_USBOTG_DM") (pintype "bidirectional"))
    )
    (net (code "186") (name "OV_USB_OTG_DP") (class "Default")
      (node (ref "CON_OV_USB_OTG") (pin "3") (pinfunction "3_3") (pintype "bidirectional"))
      (node (ref "J3&4") (pin "USBOTG_DP") (pinfunction "USBOTG_DP_USBOTG_DP") (pintype "bidirectional"))
    )
    (net (code "187") (name "POWERON") (class "Default")
      (node (ref "J3&4") (pin "POWERON") (pinfunction "POWERON_POWERON") (pintype "bidirectional"))
    )
    (net (code "188") (name "PSW_1") (class "Default")
      (node (ref "C39") (pin "P$1") (pinfunction "1_P$1") (pintype "passive"))
      (node (ref "C40") (pin "P$1") (pinfunction "1_P$1") (pintype "passive"))
      (node (ref "CON_LIGHTS") (pin "2") (pinfunction "2_2") (pintype "bidirectional"))
      (node (ref "PWS1") (pin "1") (pinfunction "OUT_1") (pintype "bidirectional"))
    )
    (net (code "189") (name "PSW_2") (class "Default")
      (node (ref "C37") (pin "P$1") (pinfunction "1_P$1") (pintype "passive"))
      (node (ref "C38") (pin "P$1") (pinfunction "1_P$1") (pintype "passive"))
      (node (ref "CON_LIGHTS") (pin "4") (pinfunction "4_4") (pintype "bidirectional"))
      (node (ref "PWS2") (pin "1") (pinfunction "OUT_1") (pintype "bidirectional"))
    )
    (net (code "190") (name "PWM0") (class "Default")
      (node (ref "J3&4") (pin "PWM0") (pinfunction "PWM0_PWM0") (pintype "bidirectional"))
    )
    (net (code "191") (name "PWM1") (class "Default")
      (node (ref "J3&4") (pin "PWM1") (pinfunction "PWM1_PWM1") (pintype "bidirectional"))
    )
    (net (code "192") (name "PWR_SW1") (class "Default")
      (node (ref "MCU") (pin "10") (pinfunction "PC2-ADC12_10") (pintype "bidirectional"))
      (node (ref "PWS1") (pin "4") (pinfunction "EN_4") (pintype "bidirectional"))
    )
    (net (code "193") (name "PWR_SW2") (class "Default")
      (node (ref "MCU") (pin "9") (pinfunction "PC1-ADC11_9") (pintype "bidirectional"))
      (node (ref "PWS2") (pin "4") (pinfunction "EN_4") (pintype "bidirectional"))
    )
    (net (code "194") (name "STM_BAT_MONITOR") (class "Default")
      (node (ref "MCU") (pin "14") (pinfunction "PA0-WKUP/USART2CTS/ADC0/TIM2CH2_14") (pintype "bidirectional"))
      (node (ref "R16") (pin "P$1") (pinfunction "1_P$1") (pintype "passive"))
      (node (ref "R17") (pin "P$2") (pinfunction "2_P$2") (pintype "passive"))
    )
    (net (code "195") (name "STM_BOOT0") (class "Default")
      (node (ref "CON_SPARE") (pin "3") (pinfunction "3_3") (pintype "bidirectional"))
      (node (ref "MCU") (pin "60") (pinfunction "BOOT0_60") (pintype "input"))
      (node (ref "R23") (pin "P$2") (pinfunction "2_P$2") (pintype "passive"))
    )
    (net (code "196") (name "STM_CAN_RX") (class "Default")
      (node (ref "MCU") (pin "44") (pinfunction "PA11-USART1CTS_44") (pintype "bidirectional"))
      (node (ref "U1") (pin "4") (pinfunction "RXD_4") (pintype "output"))
    )
    (net (code "197") (name "STM_CAN_TX") (class "Default")
      (node (ref "MCU") (pin "45") (pinfunction "PA12-USART1RTS_45") (pintype "bidirectional"))
      (node (ref "U1") (pin "1") (pinfunction "TXD_1") (pintype "input"))
    )
    (net (code "198") (name "STM_I2C1_SCL") (class "Default")
      (node (ref "LT_I2C1") (pin "3") (pinfunction "SCL1_3") (pintype "bidirectional"))
      (node (ref "MCU") (pin "58") (pinfunction "PB6-I2C1SCL/TIM4CH1-USART1TX_58") (pintype "bidirectional"))
      (node (ref "R29") (pin "P$2") (pinfunction "2_P$2") (pintype "passive"))
    )
    (net (code "199") (name "STM_I2C1_SDA") (class "Default")
      (node (ref "LT_I2C1") (pin "4") (pinfunction "SDA1_4") (pintype "bidirectional"))
      (node (ref "MCU") (pin "59") (pinfunction "PB7-I2C1SDA/TIM4CH2-USART1RX_59") (pintype "bidirectional"))
      (node (ref "R28") (pin "P$2") (pinfunction "2_P$2") (pintype "passive"))
    )
    (net (code "200") (name "STM_I2C2_SCL") (class "Default")
      (node (ref "ADC1") (pin "P$10") (pinfunction "SCL_P$10") (pintype "bidirectional"))
      (node (ref "ADC2") (pin "P$10") (pinfunction "SCL_P$10") (pintype "bidirectional"))
      (node (ref "LT_I2C2") (pin "3") (pinfunction "SCL1_3") (pintype "bidirectional"))
      (node (ref "MCU") (pin "29") (pinfunction "PB10-I2C2SCL/USART3TX_29") (pintype "bidirectional"))
      (node (ref "R33") (pin "P$1") (pinfunction "1_P$1") (pintype "passive"))
      (node (ref "R8") (pin "P$1") (pinfunction "1_P$1") (pintype "passive"))
    )
    (net (code "201") (name "STM_I2C2_SDA") (class "Default")
      (node (ref "ADC1") (pin "P$9") (pinfunction "SDA_P$9") (pintype "bidirectional"))
      (node (ref "ADC2") (pin "P$9") (pinfunction "SDA_P$9") (pintype "bidirectional"))
      (node (ref "LT_I2C2") (pin "4") (pinfunction "SDA1_4") (pintype "bidirectional"))
      (node (ref "MCU") (pin "30") (pinfunction "PB11-I2C2SDA/USART3RX_30") (pintype "bidirectional"))
      (node (ref "R34") (pin "P$1") (pinfunction "1_P$1") (pintype "passive"))
      (node (ref "R9") (pin "P$1") (pinfunction "1_P$1") (pintype "passive"))
    )
    (net (code "202") (name "STM_JTAG_TCK") (class "Default")
      (node (ref "IC3") (pin "P$38") (pinfunction "BDBUS0_P$38") (pintype "bidirectional"))
      (node (ref "MCU") (pin "49") (pinfunction "PA14/JTCK/SWCLK_49") (pintype "bidirectional"))
    )
    (net (code "203") (name "STM_JTAG_TDI") (class "Default")
      (node (ref "IC3") (pin "P$39") (pinfunction "BDBUS1_P$39") (pintype "bidirectional"))
      (node (ref "MCU") (pin "50") (pinfunction "PA15/JTDI-TIM2CH1ETR/SPI1NSS_50") (pintype "bidirectional"))
    )
    (net (code "204") (name "STM_JTAG_TDO") (class "Default")
      (node (ref "IC3") (pin "P$40") (pinfunction "BDBUS2_P$40") (pintype "bidirectional"))
      (node (ref "MCU") (pin "55") (pinfunction "PB3/JTDO-TIM2CH2/SPI1SCK_55") (pintype "bidirectional"))
    )
    (net (code "205") (name "STM_JTAG_TMS") (class "Default")
      (node (ref "IC3") (pin "P$41") (pinfunction "BDBUS3_P$41") (pintype "bidirectional"))
      (node (ref "MCU") (pin "46") (pinfunction "PA13/JTMS/SWDIO_46") (pintype "bidirectional"))
    )
    (net (code "206") (name "STM_JTAG_TRST") (class "Default")
      (node (ref "IC3") (pin "P$43") (pinfunction "BDBUS4_P$43") (pintype "bidirectional"))
      (node (ref "MCU") (pin "56") (pinfunction "PB4/JNTRST-TIM3CH1/SPI1MISO_56") (pintype "bidirectional"))
    )
    (net (code "207") (name "STM_LED_CLK") (class "Default")
      (node (ref "IC1") (pin "3") (pinfunction "CLK_3") (pintype "bidirectional"))
      (node (ref "MCU") (pin "41") (pinfunction "PA8-USART1CK/MCO_41") (pintype "bidirectional"))
      (node (ref "R51") (pin "P$2") (pinfunction "2_P$2") (pintype "passive"))
    )
    (net (code "208") (name "STM_LED_DATA") (class "Default")
      (node (ref "IC1") (pin "2") (pinfunction "SDI_2") (pintype "bidirectional"))
      (node (ref "MCU") (pin "4") (pinfunction "PC15-OSC32_OUT_4") (pintype "bidirectional"))
      (node (ref "R52") (pin "P$2") (pinfunction "2_P$2") (pintype "passive"))
    )
    (net (code "209") (name "STM_RESET") (class "Default")
      (node (ref "C9") (pin "P$2") (pinfunction "2_P$2") (pintype "passive"))
      (node (ref "IC3") (pin "P$45") (pinfunction "BDBUS6_P$45") (pintype "bidirectional"))
      (node (ref "MCU") (pin "7") (pinfunction "NRST_7") (pintype "bidirectional"))
      (node (ref "R7") (pin "P$1") (pinfunction "1_P$1") (pintype "passive"))
    )
    (net (code "210") (name "STM_SERVO1") (class "Default")
      (node (ref "CON_SERVOS_1") (pin "3") (pinfunction "3_3") (pintype "bidirectional"))
      (node (ref "MCU") (pin "37") (pinfunction "PC6-TIM3CH1_37") (pintype "bidirectional"))
    )
    (net (code "211") (name "STM_SERVO2") (class "Default")
      (node (ref "CON_SERVOS_1") (pin "6") (pinfunction "6_6") (pintype "bidirectional"))
      (node (ref "MCU") (pin "38") (pinfunction "PC7-TIM3CH2_38") (pintype "bidirectional"))
    )
    (net (code "212") (name "STM_SERVO3") (class "Default")
      (node (ref "CON_SERVOS_1") (pin "9") (pinfunction "9_9") (pintype "bidirectional"))
      (node (ref "MCU") (pin "39") (pinfunction "PC8-TIM3CH3_39") (pintype "bidirectional"))
    )
    (net (code "213") (name "STM_SERVO4") (class "Default")
      (node (ref "CON_SERVOS_2") (pin "3") (pinfunction "3_3") (pintype "bidirectional"))
      (node (ref "MCU") (pin "40") (pinfunction "PC9-TIM3CH4_40") (pintype "bidirectional"))
    )
    (net (code "214") (name "STM_SERVO5") (class "Default")
      (node (ref "CON_SERVOS_2") (pin "6") (pinfunction "6_6") (pintype "bidirectional"))
      (node (ref "MCU") (pin "61") (pinfunction "PB8-TIM4CH3-I2C1SCL_61") (pintype "bidirectional"))
    )
    (net (code "215") (name "STM_SERVO6") (class "Default")
      (node (ref "CON_SERVOS_2") (pin "9") (pinfunction "9_9") (pintype "bidirectional"))
      (node (ref "MCU") (pin "62") (pinfunction "PB9-TIM4CH4-I2C1SDA_62") (pintype "bidirectional"))
    )
    (net (code "216") (name "STM_SPI1_DRDY") (class "Default")
      (node (ref "CON_OV_SPI") (pin "8") (pinfunction "8_8") (pintype "bidirectional"))
      (node (ref "LT_3") (pin "P$10") (pinfunction "Y8_P$10") (pintype "bidirectional"))
      (node (ref "MCU") (pin "24") (pinfunction "PC4-ADC14_24") (pintype "bidirectional"))
    )
    (net (code "217") (name "STM_SPI1_MISO") (class "Default")
      (node (ref "CON_OV_SPI") (pin "6") (pinfunction "6_6") (pintype "bidirectional"))
      (node (ref "LT_3") (pin "P$14") (pinfunction "Y4_P$14") (pintype "bidirectional"))
      (node (ref "MCU") (pin "22") (pinfunction "PA6-SPI1MISO/ADC6/TIM3CH1_22") (pintype "bidirectional"))
    )
    (net (code "218") (name "STM_SPI1_MOSI") (class "Default")
      (node (ref "CON_OV_SPI") (pin "7") (pinfunction "7_7") (pintype "bidirectional"))
      (node (ref "LT_3") (pin "P$13") (pinfunction "Y5_P$13") (pintype "bidirectional"))
      (node (ref "MCU") (pin "23") (pinfunction "PA7-SPI1MOSI/ADC7/TIM3CH2_23") (pintype "bidirectional"))
    )
    (net (code "219") (name "STM_SPI1_NSS") (class "Default")
      (node (ref "LT_3") (pin "P$11") (pinfunction "Y7_P$11") (pintype "bidirectional"))
      (node (ref "MCU") (pin "20") (pinfunction "PA4-SPI1NSS/ADC4/USART2CK_20") (pintype "bidirectional"))
    )
    (net (code "220") (name "STM_SPI1_SCK") (class "Default")
      (node (ref "CON_OV_SPI") (pin "5") (pinfunction "5_5") (pintype "bidirectional"))
      (node (ref "LT_3") (pin "P$12") (pinfunction "Y6_P$12") (pintype "bidirectional"))
      (node (ref "MCU") (pin "21") (pinfunction "PA5-SPI1SCK/ADC5_21") (pintype "bidirectional"))
    )
    (net (code "221") (name "STM_SPI2_EEPROM_SS") (class "Default")
      (node (ref "CON_IMU") (pin "12") (pinfunction "12_12") (pintype "bidirectional"))
      (node (ref "MCU") (pin "3") (pinfunction "PC14-OSC32_IN_3") (pintype "bidirectional"))
    )
    (net (code "222") (name "STM_SPI2_IMU_DRDY") (class "Default")
      (node (ref "CON_IMU") (pin "9") (pinfunction "9_9") (pintype "bidirectional"))
      (node (ref "MCU") (pin "54") (pinfunction "PD2-TIM3ETR_54") (pintype "bidirectional"))
    )
    (net (code "223") (name "STM_SPI2_MAG_DRDY") (class "Default")
      (node (ref "CON_IMU") (pin "10") (pinfunction "10_10") (pintype "bidirectional"))
      (node (ref "MCU") (pin "57") (pinfunction "PB5-I2C1SMBAI-TIM3CH2/SPI1MOSI_57") (pintype "bidirectional"))
    )
    (net (code "224") (name "STM_SPI2_MAG_RESET") (class "Default")
      (node (ref "CON_IMU") (pin "11") (pinfunction "11_11") (pintype "bidirectional"))
      (node (ref "MCU") (pin "2") (pinfunction "PC13-TAMPER-RTC_2") (pintype "bidirectional"))
      (node (ref "R8") (pin "P$2") (pinfunction "2_P$2") (pintype "passive"))
    )
    (net (code "225") (name "STM_SPI2_MAG_SS") (class "Default")
      (node (ref "CON_IMU") (pin "8") (pinfunction "8_8") (pintype "bidirectional"))
      (node (ref "MCU") (pin "53") (pinfunction "PC12-USART3CK_53") (pintype "bidirectional"))
      (node (ref "R9") (pin "P$2") (pinfunction "2_P$2") (pintype "passive"))
    )
    (net (code "226") (name "STM_SPI2_MISO") (class "Default")
      (node (ref "CON_IMU") (pin "5") (pinfunction "5_5") (pintype "bidirectional"))
      (node (ref "MCU") (pin "35") (pinfunction "PB14-SPI2MISO/USART3RTS_35") (pintype "bidirectional"))
    )
    (net (code "227") (name "STM_SPI2_MOSI") (class "Default")
      (node (ref "CON_IMU") (pin "4") (pinfunction "4_4") (pintype "bidirectional"))
      (node (ref "MCU") (pin "36") (pinfunction "PB15-SPI2MOSI_36") (pintype "bidirectional"))
    )
    (net (code "228") (name "STM_SPI2_NSS") (class "Default")
      (node (ref "CON_IMU") (pin "7") (pinfunction "7_7") (pintype "bidirectional"))
      (node (ref "MCU") (pin "33") (pinfunction "PB12-SPI2NSS/I2C2SMBAI/USART3CK_33") (pintype "bidirectional"))
    )
    (net (code "229") (name "STM_SPI2_SCK") (class "Default")
      (node (ref "CON_IMU") (pin "6") (pinfunction "6_6") (pintype "bidirectional"))
      (node (ref "MCU") (pin "34") (pinfunction "PB13-SPI2SCK/USART3CTS_34") (pintype "bidirectional"))
    )
    (net (code "230") (name "STM_USART1_RX") (class "Default")
      (node (ref "IC6") (pin "9") (pinfunction "R1OUT_9") (pintype "output"))
      (node (ref "MCU") (pin "43") (pinfunction "PA10-USART1RX_43") (pintype "bidirectional"))
      (node (ref "R37") (pin "P$2") (pinfunction "2_P$2") (pintype "passive"))
    )
    (net (code "231") (name "STM_USART1_TX") (class "Default")
      (node (ref "IC6") (pin "11") (pinfunction "T1IN_11") (pintype "input"))
      (node (ref "MCU") (pin "42") (pinfunction "PA9-USART1TX_42") (pintype "bidirectional"))
      (node (ref "R36") (pin "P$2") (pinfunction "2_P$2") (pintype "passive"))
    )
    (net (code "232") (name "STM_USART2_RX") (class "Default")
      (node (ref "CON_USART2") (pin "5") (pinfunction "5_5") (pintype "bidirectional"))
      (node (ref "MCU") (pin "17") (pinfunction "PA3-USART2RX/ADC3/TIM2CH4_17") (pintype "bidirectional"))
    )
    (net (code "233") (name "STM_USART2_TX") (class "Default")
      (node (ref "CON_USART2") (pin "4") (pinfunction "4_4") (pintype "bidirectional"))
      (node (ref "MCU") (pin "16") (pinfunction "PA2-USART2TX/ADC2/TIM2CH3_16") (pintype "bidirectional"))
    )
    (net (code "234") (name "STM_USART3_RX") (class "Default")
      (node (ref "CON_USART3") (pin "5") (pinfunction "5_5") (pintype "bidirectional"))
      (node (ref "MCU") (pin "52") (pinfunction "PC11-USART3RX_52") (pintype "bidirectional"))
    )
    (net (code "235") (name "STM_USART3_TX") (class "Default")
      (node (ref "CON_USART3") (pin "4") (pinfunction "4_4") (pintype "bidirectional"))
      (node (ref "MCU") (pin "51") (pinfunction "PC10-USART3TX_51") (pintype "bidirectional"))
    )
    (net (code "236") (name "ST_UART1_TRIG") (class "Default")
      (node (ref "MCU") (pin "15") (pinfunction "PA1-USART2RTS/ADC1/TIM2CH2_15") (pintype "bidirectional"))
      (node (ref "R48") (pin "P$1") (pinfunction "1_P$1") (pintype "passive"))
    )
    (net (code "237") (name "SYS_EN") (class "Default")
      (node (ref "J3&4") (pin "SYSEN") (pinfunction "SYSEN_SYSEN") (pintype "bidirectional"))
      (node (ref "REG_1V8") (pin "3") (pinfunction "EN_3") (pintype "input"))
    )
    (net (code "238") (name "USBH_VBUS") (class "Default")
      (node (ref "J3&4") (pin "USBH_VBUS") (pinfunction "USBH_VBUS_USBH_VBUS") (pintype "bidirectional"))
      (node (ref "R70") (pin "P$2") (pinfunction "2_P$2") (pintype "passive"))
    )
    (net (code "239") (name "USB_OTG_VBUS") (class "Default")
      (node (ref "J3&4") (pin "USBOTG_VBUS") (pinfunction "USBOTG_VBUS_USBOTG_VBUS") (pintype "bidirectional"))
      (node (ref "R67") (pin "P$1") (pinfunction "1_P$1") (pintype "passive"))
    )
    (net (code "240") (name "VBACKUP") (class "Default")
      (node (ref "J3&4") (pin "VBACKUP") (pinfunction "VBACKUP_VBACKUP") (pintype "bidirectional"))
    )
    (net (code "241") (name "VREF") (class "Default")
      (node (ref "U1") (pin "5") (pinfunction "VREF_5") (pintype "power_in"))
    )
    (net (code "242") (name "V_PRESSURE_ABS_AMP") (class "Default")
      (node (ref "ADC2") (pin "P$4") (pinfunction "AIN0_P$4") (pintype "bidirectional"))
      (node (ref "C24") (pin "P$1") (pinfunction "1_P$1") (pintype "passive"))
      (node (ref "U90") (pin "13") (pinfunction "-IN_13") (pintype "input"))
      (node (ref "U90") (pin "14") (pinfunction "OUT_14") (pintype "output"))
    )
    (net (code "243") (name "V_PRESSURE_DIFF_AMP") (class "Default")
      (node (ref "ADC1") (pin "P$4") (pinfunction "AIN0_P$4") (pintype "bidirectional"))
      (node (ref "C31") (pin "P$1") (pinfunction "1_P$1") (pintype "passive"))
      (node (ref "R69") (pin "P$1") (pinfunction "1_P$1") (pintype "passive"))
      (node (ref "U90") (pin "6") (pinfunction "-IN_6") (pintype "input"))
      (node (ref "U90") (pin "7") (pinfunction "OUT_7") (pintype "output"))
    )
    (net (code "244") (name "XXX_STM_SPARE_1") (class "Default")
      (node (ref "CON_SPARE") (pin "5") (pinfunction "5_5") (pintype "bidirectional"))
      (node (ref "MCU") (pin "25") (pinfunction "PC5-ADC15_25") (pintype "bidirectional"))
    )
    (net (code "245") (name "XXX_STM_SPARE_2") (class "Default")
      (node (ref "CON_SPARE") (pin "4") (pinfunction "4_4") (pintype "bidirectional"))
      (node (ref "MCU") (pin "11") (pinfunction "PC3-ADC13_11") (pintype "bidirectional"))
    )
    (net (code "246") (name "XXX_STM_SPARE_6") (class "Default")
      (node (ref "CON_SPARE") (pin "6") (pinfunction "6_6") (pintype "bidirectional"))
      (node (ref "MCU") (pin "26") (pinfunction "PB0-ADC8/TIM3CH3_26") (pintype "bidirectional"))
    )
    (net (code "247") (name "XXX_STM_SPARE_7") (class "Default")
      (node (ref "CON_SPARE") (pin "7") (pinfunction "7_7") (pintype "bidirectional"))
      (node (ref "MCU") (pin "27") (pinfunction "PB1-ADC9/TIM3CH4_27") (pintype "bidirectional"))
    )
    (net (code "248") (name "XXX_STM_SPARE_8") (class "Default")
      (node (ref "CON_SPARE") (pin "8") (pinfunction "8_8") (pintype "bidirectional"))
      (node (ref "MCU") (pin "28") (pinfunction "PB2/BOOT1_28") (pintype "bidirectional"))
    )
    (net (code "249") (name "X_ADDR_01") (class "Default")
      (node (ref "J3&4") (pin "EM_A1") (pinfunction "EM_A1_EM_A1") (pintype "bidirectional"))
    )
    (net (code "250") (name "X_ADDR_02") (class "Default")
      (node (ref "J3&4") (pin "EM_A2") (pinfunction "EM_A2_EM_A2") (pintype "bidirectional"))
    )
    (net (code "251") (name "X_ADDR_03") (class "Default")
      (node (ref "J3&4") (pin "EM_A3") (pinfunction "EM_A3_EM_A3") (pintype "bidirectional"))
    )
    (net (code "252") (name "X_ADDR_04") (class "Default")
      (node (ref "J3&4") (pin "EM_A4") (pinfunction "EM_A4_EM_A4") (pintype "bidirectional"))
    )
    (net (code "253") (name "X_ADDR_05") (class "Default")
      (node (ref "J3&4") (pin "EM_A5") (pinfunction "EM_A5_EM_A5") (pintype "bidirectional"))
    )
    (net (code "254") (name "X_ADDR_06") (class "Default")
      (node (ref "J3&4") (pin "EM_A6") (pinfunction "EM_A6_EM_A6") (pintype "bidirectional"))
    )
    (net (code "255") (name "X_ADDR_07") (class "Default")
      (node (ref "J3&4") (pin "EM_A7") (pinfunction "EM_A7_EM_A7") (pintype "bidirectional"))
    )
    (net (code "256") (name "X_ADDR_08") (class "Default")
      (node (ref "J3&4") (pin "EM_A8") (pinfunction "EM_A8_EM_A8") (pintype "bidirectional"))
    )
    (net (code "257") (name "X_ADDR_09") (class "Default")
      (node (ref "J3&4") (pin "EM_A9") (pinfunction "EM_A9_EM_A9") (pintype "bidirectional"))
    )
    (net (code "258") (name "X_ADDR_10") (class "Default")
      (node (ref "J3&4") (pin "EM_A10") (pinfunction "EM_A10_EM_A10") (pintype "bidirectional"))
    )
    (net (code "259") (name "X_CLK") (class "Default")
      (node (ref "J3&4") (pin "EM_CLK") (pinfunction "EM_CLK_EM_CLK") (pintype "bidirectional"))
    )
    (net (code "260") (name "X_DATA_0") (class "Default")
      (node (ref "J3&4") (pin "EM_D0") (pinfunction "EM_D0_EM_D0") (pintype "bidirectional"))
    )
    (net (code "261") (name "X_DATA_1") (class "Default")
      (node (ref "J3&4") (pin "EM_D1") (pinfunction "EM_D1_EM_D1") (pintype "bidirectional"))
    )
    (net (code "262") (name "X_DATA_2") (class "Default")
      (node (ref "J3&4") (pin "EM_D2") (pinfunction "EM_D2_EM_D2") (pintype "bidirectional"))
    )
    (net (code "263") (name "X_DATA_3") (class "Default")
      (node (ref "J3&4") (pin "EM_D3") (pinfunction "EM_D3_EM_D3") (pintype "bidirectional"))
    )
    (net (code "264") (name "X_DATA_4") (class "Default")
      (node (ref "J3&4") (pin "EM_D4") (pinfunction "EM_D4_EM_D4") (pintype "bidirectional"))
    )
    (net (code "265") (name "X_DATA_5") (class "Default")
      (node (ref "J3&4") (pin "EM_D5") (pinfunction "EM_D5_EM_D5") (pintype "bidirectional"))
    )
    (net (code "266") (name "X_DATA_6") (class "Default")
      (node (ref "J3&4") (pin "EM_D6") (pinfunction "EM_D6_EM_D6") (pintype "bidirectional"))
    )
    (net (code "267") (name "X_DATA_7") (class "Default")
      (node (ref "J3&4") (pin "EM_D7") (pinfunction "EM_D7_EM_D7") (pintype "bidirectional"))
    )
    (net (code "268") (name "X_DATA_8") (class "Default")
      (node (ref "J3&4") (pin "EM_D8") (pinfunction "EM_D8_EM_D8") (pintype "bidirectional"))
    )
    (net (code "269") (name "X_DATA_9") (class "Default")
      (node (ref "J3&4") (pin "EM_D9") (pinfunction "EM_D9_EM_D9") (pintype "bidirectional"))
    )
    (net (code "270") (name "X_DATA_10") (class "Default")
      (node (ref "J3&4") (pin "EM_D10") (pinfunction "EM_D10_EM_D10") (pintype "bidirectional"))
    )
    (net (code "271") (name "X_DATA_11") (class "Default")
      (node (ref "J3&4") (pin "EM_D11") (pinfunction "EM_D11_EM_D11") (pintype "bidirectional"))
    )
    (net (code "272") (name "X_DATA_12") (class "Default")
      (node (ref "J3&4") (pin "EM_D12") (pinfunction "EM_D12_EM_D12") (pintype "bidirectional"))
    )
    (net (code "273") (name "X_DATA_13") (class "Default")
      (node (ref "J3&4") (pin "EM_D13") (pinfunction "EM_D13_EM_D13") (pintype "bidirectional"))
    )
    (net (code "274") (name "X_DATA_14") (class "Default")
      (node (ref "J3&4") (pin "EM_D14") (pinfunction "EM_D14_EM_D14") (pintype "bidirectional"))
    )
    (net (code "275") (name "X_DATA_15") (class "Default")
      (node (ref "J3&4") (pin "EM_D15") (pinfunction "EM_D15_EM_D15") (pintype "bidirectional"))
    )
    (net (code "276") (name "X_GPIO64_ETH0_NRESET") (class "Default")
      (node (ref "J3&4") (pin "GPIO64_ETH0_NRESET") (pinfunction "GPIO64_ETH0_NRESET_GPIO64_ETH0_NRESET") (pintype "bidirectional"))
    )
    (net (code "277") (name "X_GPIO65_ETH1_IRQ1") (class "Default")
      (node (ref "J3&4") (pin "GPIO65_ETH1_IRQ1") (pinfunction "GPIO65_ETH1_IRQ1_GPIO65_ETH1_IRQ1") (pintype "bidirectional"))
    )
    (net (code "278") (name "X_NADV_ALE") (class "Default")
      (node (ref "J3&4") (pin "EM_NADV_ALE") (pinfunction "EM_NADV_ALE_EM_NADV_ALE") (pintype "bidirectional"))
    )
    (net (code "279") (name "X_NBE0") (class "Default")
      (node (ref "J3&4") (pin "EM_NBE0") (pinfunction "EM_NBE0_EM_NBE0") (pintype "bidirectional"))
    )
    (net (code "280") (name "X_NBE1") (class "Default")
      (node (ref "J3&4") (pin "EM_NBE1") (pinfunction "EM_NBE1_EM_NBE1") (pintype "bidirectional"))
    )
    (net (code "281") (name "X_NCS0") (class "Default")
      (node (ref "J3&4") (pin "EM_NCS0") (pinfunction "EM_NCS0_EM_NCS0") (pintype "bidirectional"))
    )
    (net (code "282") (name "X_NCS1") (class "Default")
      (node (ref "J3&4") (pin "EM_NCS1") (pinfunction "EM_NCS1_EM_NCS1") (pintype "bidirectional"))
    )
    (net (code "283") (name "X_NCS4") (class "Default")
      (node (ref "J3&4") (pin "EM_NCS4") (pinfunction "EM_NCS4_EM_NCS4") (pintype "bidirectional"))
    )
    (net (code "284") (name "X_NCS5_ETHO") (class "Default")
      (node (ref "J3&4") (pin "EM_NCS5_ETH0") (pinfunction "EM_NCS5_ETH0_EM_NCS5_ETH0") (pintype "bidirectional"))
    )
    (net (code "285") (name "X_NCS6") (class "Default")
      (node (ref "J3&4") (pin "EM_NCS6") (pinfunction "EM_NCS6_EM_NCS6") (pintype "bidirectional"))
    )
    (net (code "286") (name "X_NMWP") (class "Default")
      (node (ref "J3&4") (pin "EM_NWP") (pinfunction "EM_NWP_EM_NWP") (pintype "bidirectional"))
    )
    (net (code "287") (name "X_NOE") (class "Default")
      (node (ref "J3&4") (pin "EM_NOE") (pinfunction "EM_NOE_EM_NOE") (pintype "bidirectional"))
    )
    (net (code "288") (name "X_NPWE") (class "Default")
      (node (ref "J3&4") (pin "EM_NWE") (pinfunction "EM_NWE_EM_NWE") (pintype "bidirectional"))
    )
    (net (code "289") (name "X_RDY") (class "Default")
      (node (ref "J3&4") (pin "EM_WAIT0") (pinfunction "EM_WAIT0_EM_WAIT0") (pintype "bidirectional"))
    )
    (net (code "290") (name "unconnected-(ADC1-AIN2-PadP$6)") (class "Default")
      (node (ref "ADC1") (pin "P$6") (pinfunction "AIN2_P$6") (pintype "bidirectional"))
    )
    (net (code "291") (name "unconnected-(ADC1-AIN3-PadP$7)") (class "Default")
      (node (ref "ADC1") (pin "P$7") (pinfunction "AIN3_P$7") (pintype "bidirectional"))
    )
    (net (code "292") (name "unconnected-(CON_USB1-Pad4)") (class "Default")
      (node (ref "CON_USB1") (pin "4") (pinfunction "4_4") (pintype "input"))
    )
    (net (code "293") (name "unconnected-(IC1-SDO-Pad14)") (class "Default")
      (node (ref "IC1") (pin "14") (pinfunction "SDO_14") (pintype "bidirectional"))
    )
    (net (code "294") (name "unconnected-(IC3-ACBUS0-PadP$26)") (class "Default")
      (node (ref "IC3") (pin "P$26") (pinfunction "ACBUS0_P$26") (pintype "bidirectional"))
    )
    (net (code "295") (name "unconnected-(IC3-ACBUS1-PadP$27)") (class "Default")
      (node (ref "IC3") (pin "P$27") (pinfunction "ACBUS1_P$27") (pintype "bidirectional"))
    )
    (net (code "296") (name "unconnected-(IC3-ACBUS2-PadP$28)") (class "Default")
      (node (ref "IC3") (pin "P$28") (pinfunction "ACBUS2_P$28") (pintype "bidirectional"))
    )
    (net (code "297") (name "unconnected-(IC3-ACBUS3-PadP$29)") (class "Default")
      (node (ref "IC3") (pin "P$29") (pinfunction "ACBUS3_P$29") (pintype "bidirectional"))
    )
    (net (code "298") (name "unconnected-(IC3-ACBUS4-PadP$30)") (class "Default")
      (node (ref "IC3") (pin "P$30") (pinfunction "ACBUS4_P$30") (pintype "bidirectional"))
    )
    (net (code "299") (name "unconnected-(IC3-ACBUS5-PadP$32)") (class "Default")
      (node (ref "IC3") (pin "P$32") (pinfunction "ACBUS5_P$32") (pintype "bidirectional"))
    )
    (net (code "300") (name "unconnected-(IC3-ACBUS6-PadP$33)") (class "Default")
      (node (ref "IC3") (pin "P$33") (pinfunction "ACBUS6_P$33") (pintype "bidirectional"))
    )
    (net (code "301") (name "unconnected-(IC3-ACBUS7-PadP$34)") (class "Default")
      (node (ref "IC3") (pin "P$34") (pinfunction "ACBUS7_P$34") (pintype "bidirectional"))
    )
    (net (code "302") (name "unconnected-(IC3-ADBUS2-PadP$18)") (class "Default")
      (node (ref "IC3") (pin "P$18") (pinfunction "ADBUS2_P$18") (pintype "bidirectional"))
    )
    (net (code "303") (name "unconnected-(IC3-ADBUS3-PadP$19)") (class "Default")
      (node (ref "IC3") (pin "P$19") (pinfunction "ADBUS3_P$19") (pintype "bidirectional"))
    )
    (net (code "304") (name "unconnected-(IC3-ADBUS4-PadP$21)") (class "Default")
      (node (ref "IC3") (pin "P$21") (pinfunction "ADBUS4_P$21") (pintype "bidirectional"))
    )
    (net (code "305") (name "unconnected-(IC3-ADBUS5-PadP$22)") (class "Default")
      (node (ref "IC3") (pin "P$22") (pinfunction "ADBUS5_P$22") (pintype "bidirectional"))
    )
    (net (code "306") (name "unconnected-(IC3-ADBUS6-PadP$23)") (class "Default")
      (node (ref "IC3") (pin "P$23") (pinfunction "ADBUS6_P$23") (pintype "bidirectional"))
    )
    (net (code "307") (name "unconnected-(IC3-ADBUS7-PadP$24)") (class "Default")
      (node (ref "IC3") (pin "P$24") (pinfunction "ADBUS7_P$24") (pintype "bidirectional"))
    )
    (net (code "308") (name "unconnected-(IC3-BCBUS0-PadP$48)") (class "Default")
      (node (ref "IC3") (pin "P$48") (pinfunction "BCBUS0_P$48") (pintype "bidirectional"))
    )
    (net (code "309") (name "unconnected-(IC3-BCBUS1-PadP$52)") (class "Default")
      (node (ref "IC3") (pin "P$52") (pinfunction "BCBUS1_P$52") (pintype "bidirectional"))
    )
    (net (code "310") (name "unconnected-(IC3-BCBUS2-PadP$53)") (class "Default")
      (node (ref "IC3") (pin "P$53") (pinfunction "BCBUS2_P$53") (pintype "bidirectional"))
    )
    (net (code "311") (name "unconnected-(IC3-BCBUS5-PadP$57)") (class "Default")
      (node (ref "IC3") (pin "P$57") (pinfunction "BCBUS5_P$57") (pintype "bidirectional"))
    )
    (net (code "312") (name "unconnected-(IC3-BCBUS6-PadP$58)") (class "Default")
      (node (ref "IC3") (pin "P$58") (pinfunction "BCBUS6_P$58") (pintype "bidirectional"))
    )
    (net (code "313") (name "unconnected-(IC3-BCBUS7-PadP$59)") (class "Default")
      (node (ref "IC3") (pin "P$59") (pinfunction "BCBUS7_P$59") (pintype "bidirectional"))
    )
    (net (code "314") (name "unconnected-(IC3-BDBUS5-PadP$44)") (class "Default")
      (node (ref "IC3") (pin "P$44") (pinfunction "BDBUS5_P$44") (pintype "bidirectional"))
    )
    (net (code "315") (name "unconnected-(IC3-BDBUS7-PadP$46)") (class "Default")
      (node (ref "IC3") (pin "P$46") (pinfunction "BDBUS7_P$46") (pintype "bidirectional"))
    )
    (net (code "316") (name "unconnected-(IC3-PWREN#-PadP$60)") (class "Default")
      (node (ref "IC3") (pin "P$60") (pinfunction "PWREN#_P$60") (pintype "bidirectional"))
    )
    (net (code "317") (name "unconnected-(IC3-SUSPEND#-PadP$36)") (class "Default")
      (node (ref "IC3") (pin "P$36") (pinfunction "SUSPEND#_P$36") (pintype "bidirectional"))
    )
    (net (code "318") (name "unconnected-(IC4A-~{INVALID}-Pad10)") (class "Default")
      (node (ref "IC4") (pin "10") (pinfunction "~{INVALID}_10") (pintype "input"))
    )
    (net (code "319") (name "unconnected-(IC6A-~{INVALID}-Pad10)") (class "Default")
      (node (ref "IC6") (pin "10") (pinfunction "~{INVALID}_10") (pintype "input"))
    )
    (net (code "320") (name "unconnected-(J3&4-NC-PadNC@62)") (class "Default")
      (node (ref "J3&4") (pin "NC@62") (pinfunction "NC_NC@62") (pintype "bidirectional"))
    )
    (net (code "321") (name "unconnected-(J3&4-NC-PadNC@63)") (class "Default")
      (node (ref "J3&4") (pin "NC@63") (pinfunction "NC_NC@63") (pintype "bidirectional"))
    )
    (net (code "322") (name "unconnected-(PWS1-OC-Pad3)") (class "Default")
      (node (ref "PWS1") (pin "3") (pinfunction "OC_3") (pintype "bidirectional"))
    )
    (net (code "323") (name "unconnected-(PWS2-OC-Pad3)") (class "Default")
      (node (ref "PWS2") (pin "3") (pinfunction "OC_3") (pintype "bidirectional"))
    )
    (net (code "324") (name "unconnected-(Q7-TRI-Pad1)") (class "Default")
      (node (ref "Q7") (pin "1") (pinfunction "TRI_1") (pintype "output"))
    )
    (net (code "325") (name "unconnected-(REG_1V8-ADJ-Pad4)") (class "Default")
      (node (ref "REG_1V8") (pin "4") (pinfunction "ADJ_4") (pintype "passive"))
    )
    (net (code "326") (name "unconnected-(REG_3V3D-IHN-PadP$5)") (class "Default")
      (node (ref "REG_3V3D") (pin "P$5") (pinfunction "IHN_P$5") (pintype "bidirectional"))
    )
    (net (code "327") (name "unconnected-(REG_5VD-IHN-PadP$5)") (class "Default")
      (node (ref "REG_5VD") (pin "P$5") (pinfunction "IHN_P$5") (pintype "bidirectional"))
    )
  )
)
